# LED-plus20-SHIM.net
KiCad netlist of a schematic drawn in EAGLE
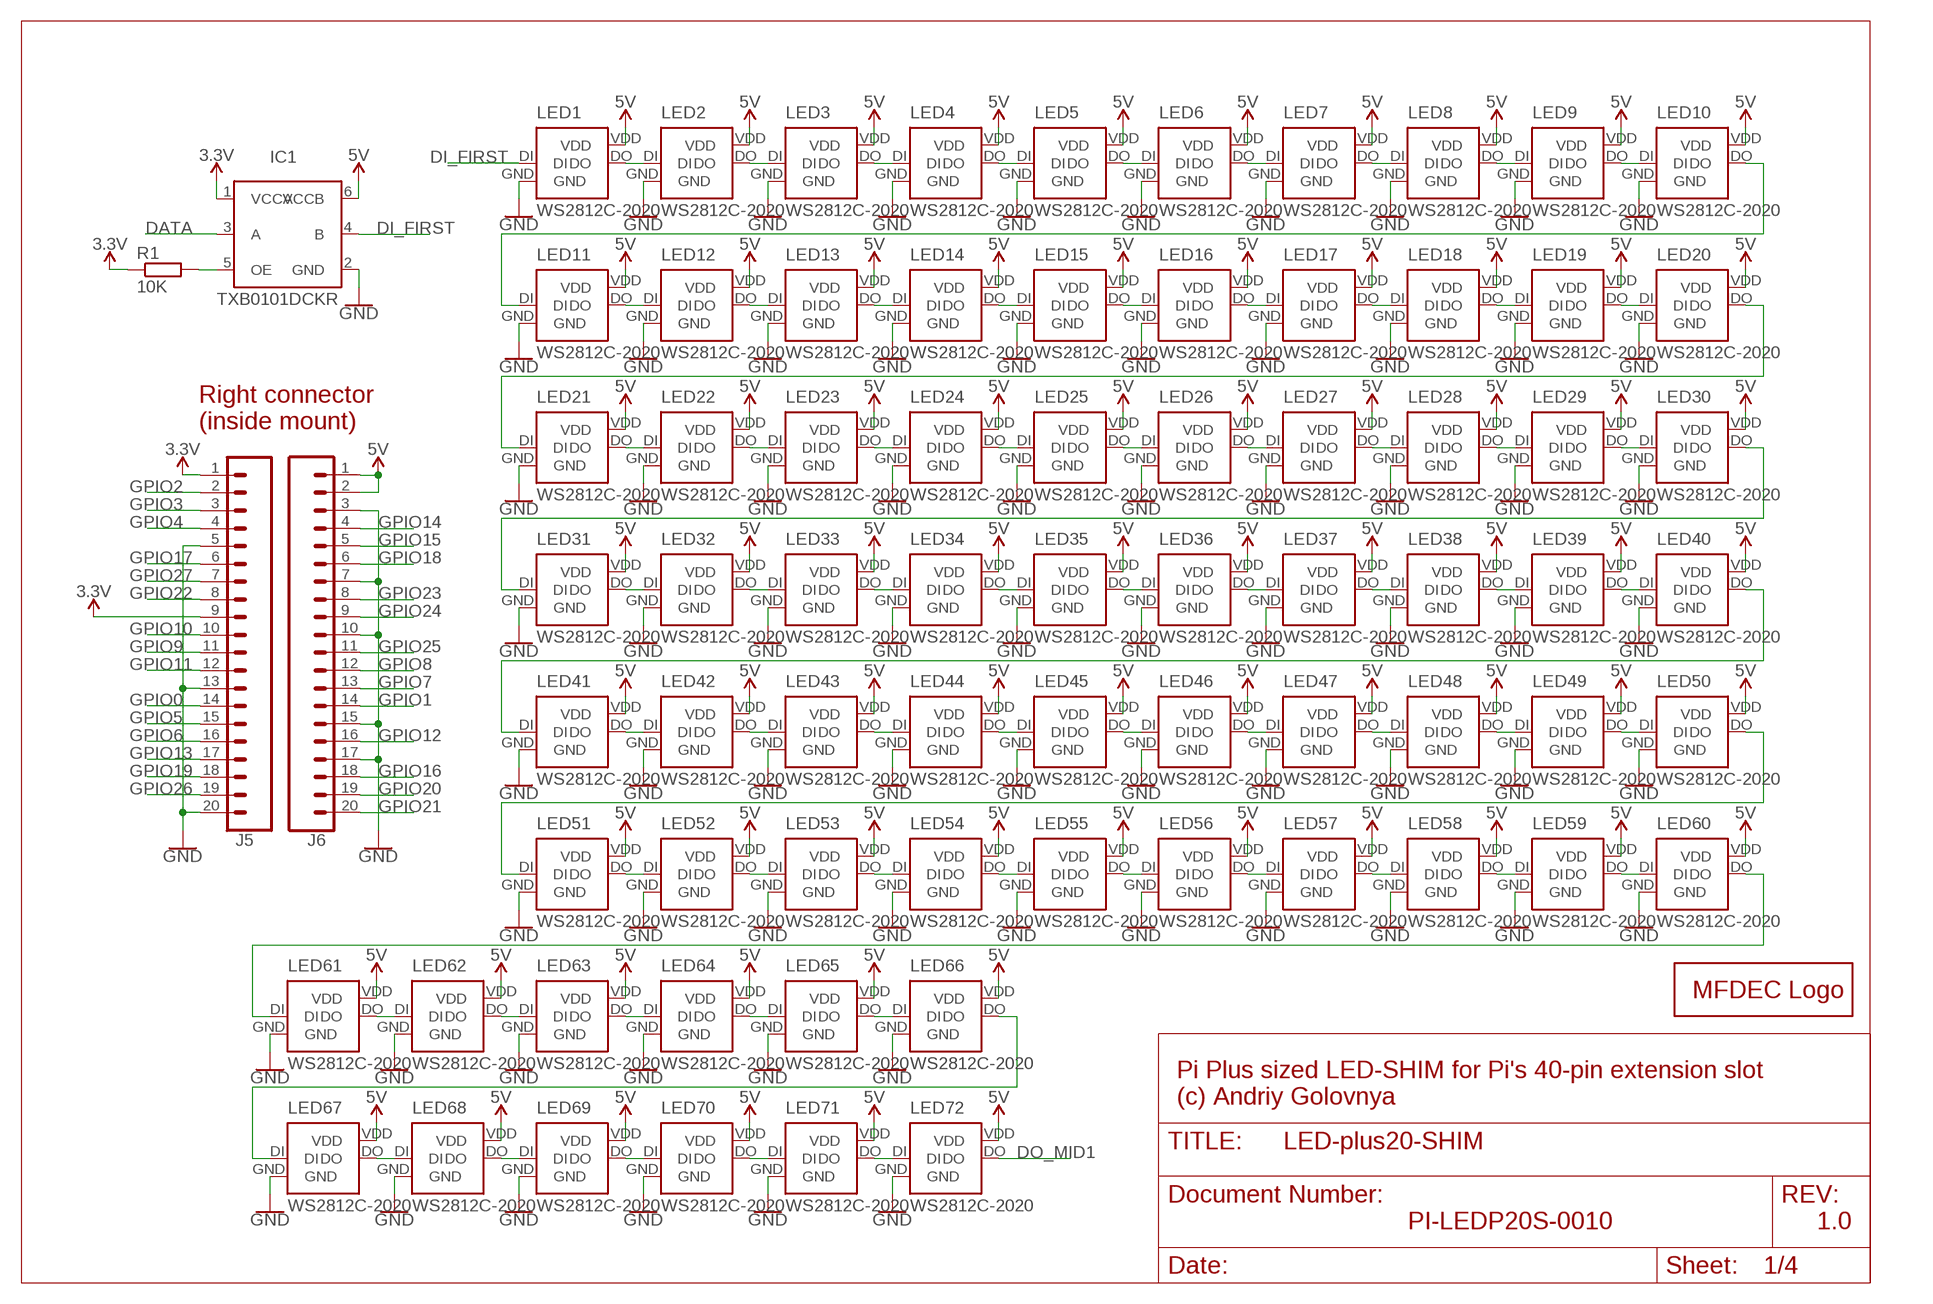
[diagram p0: schematic, sheet 1]
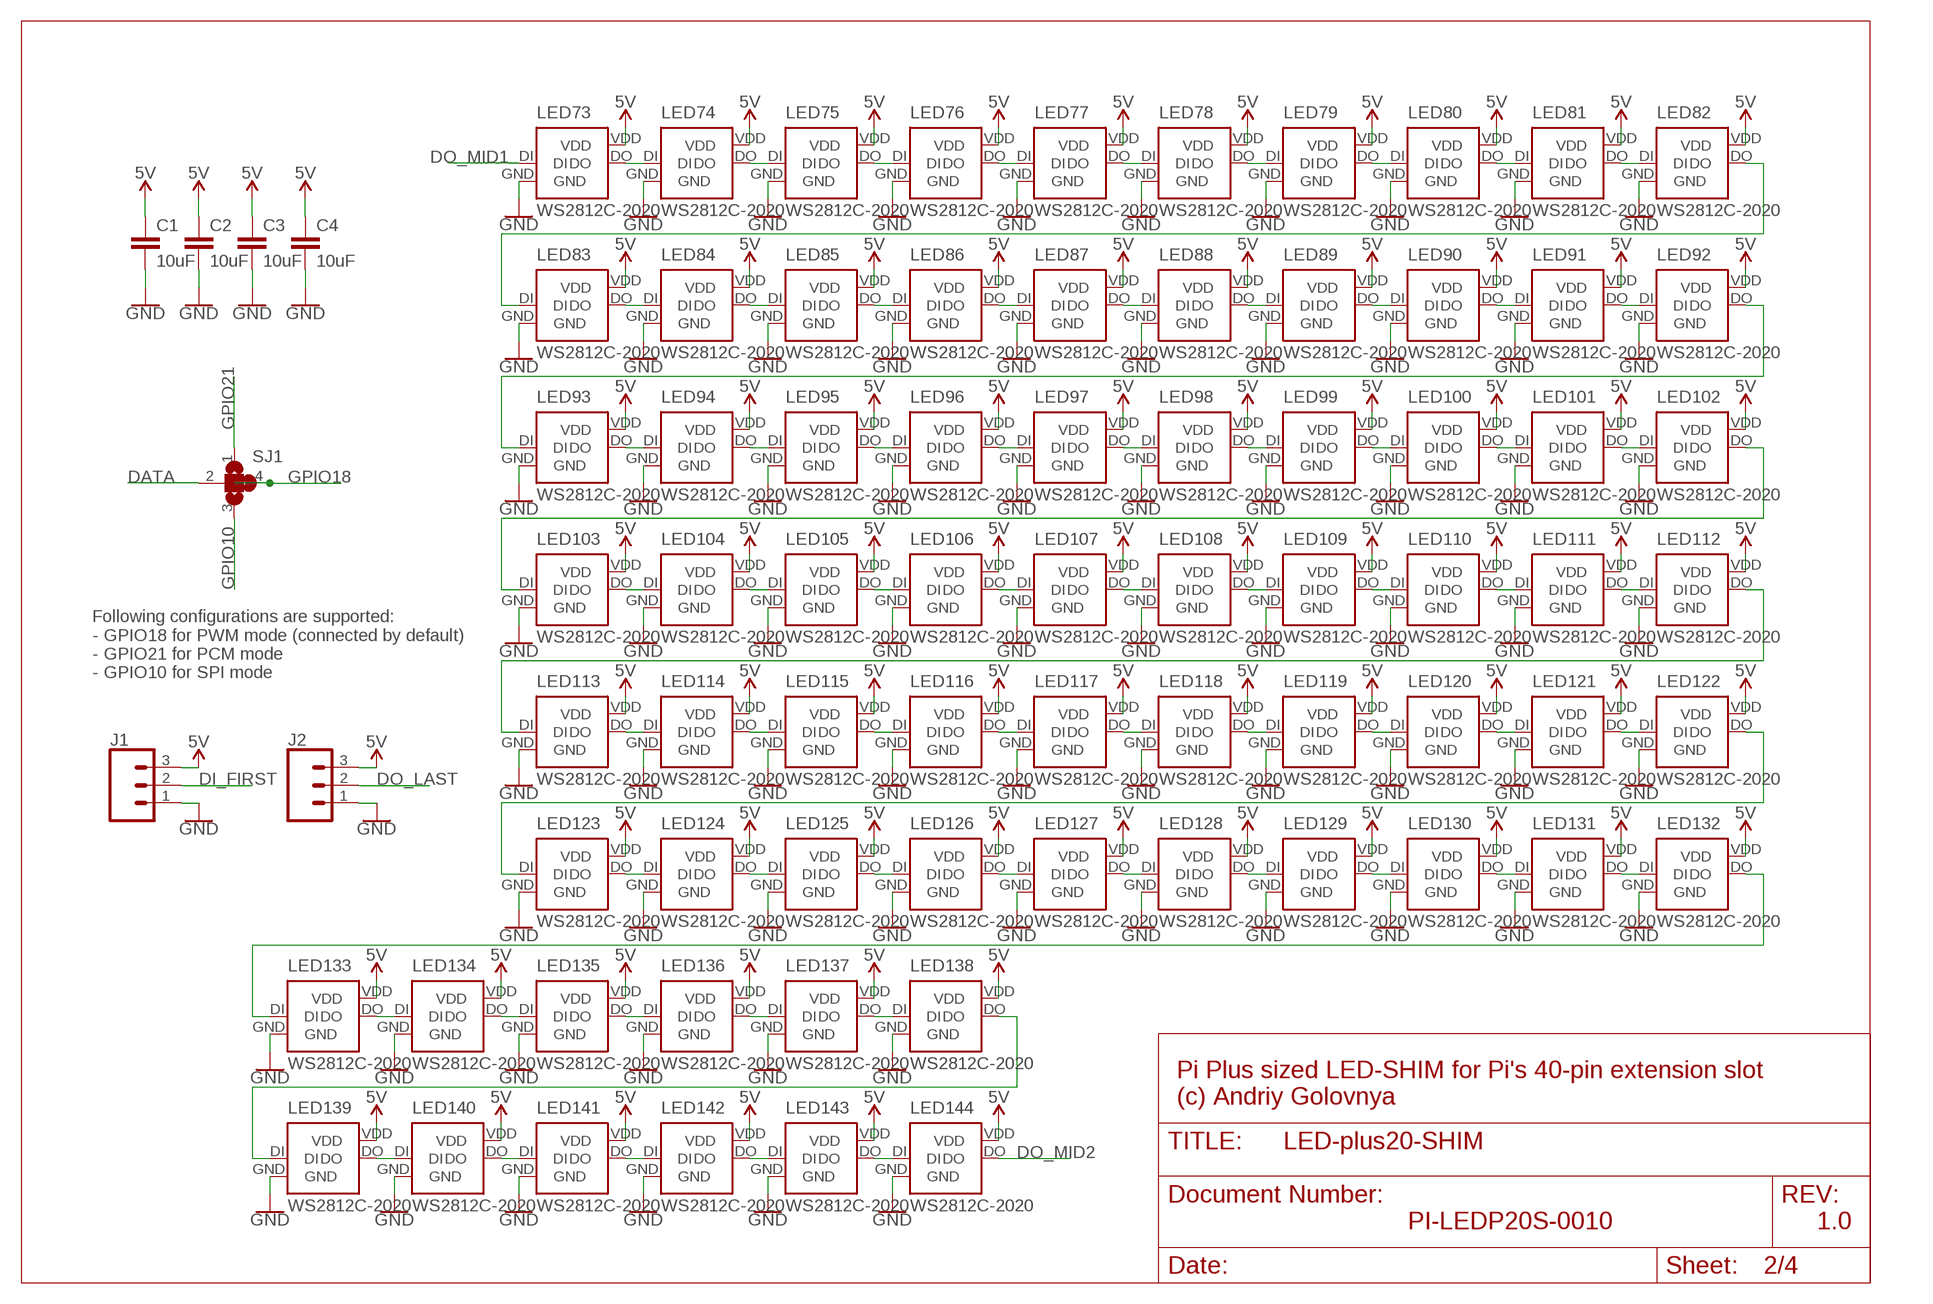
[diagram p1: schematic, sheet 2]
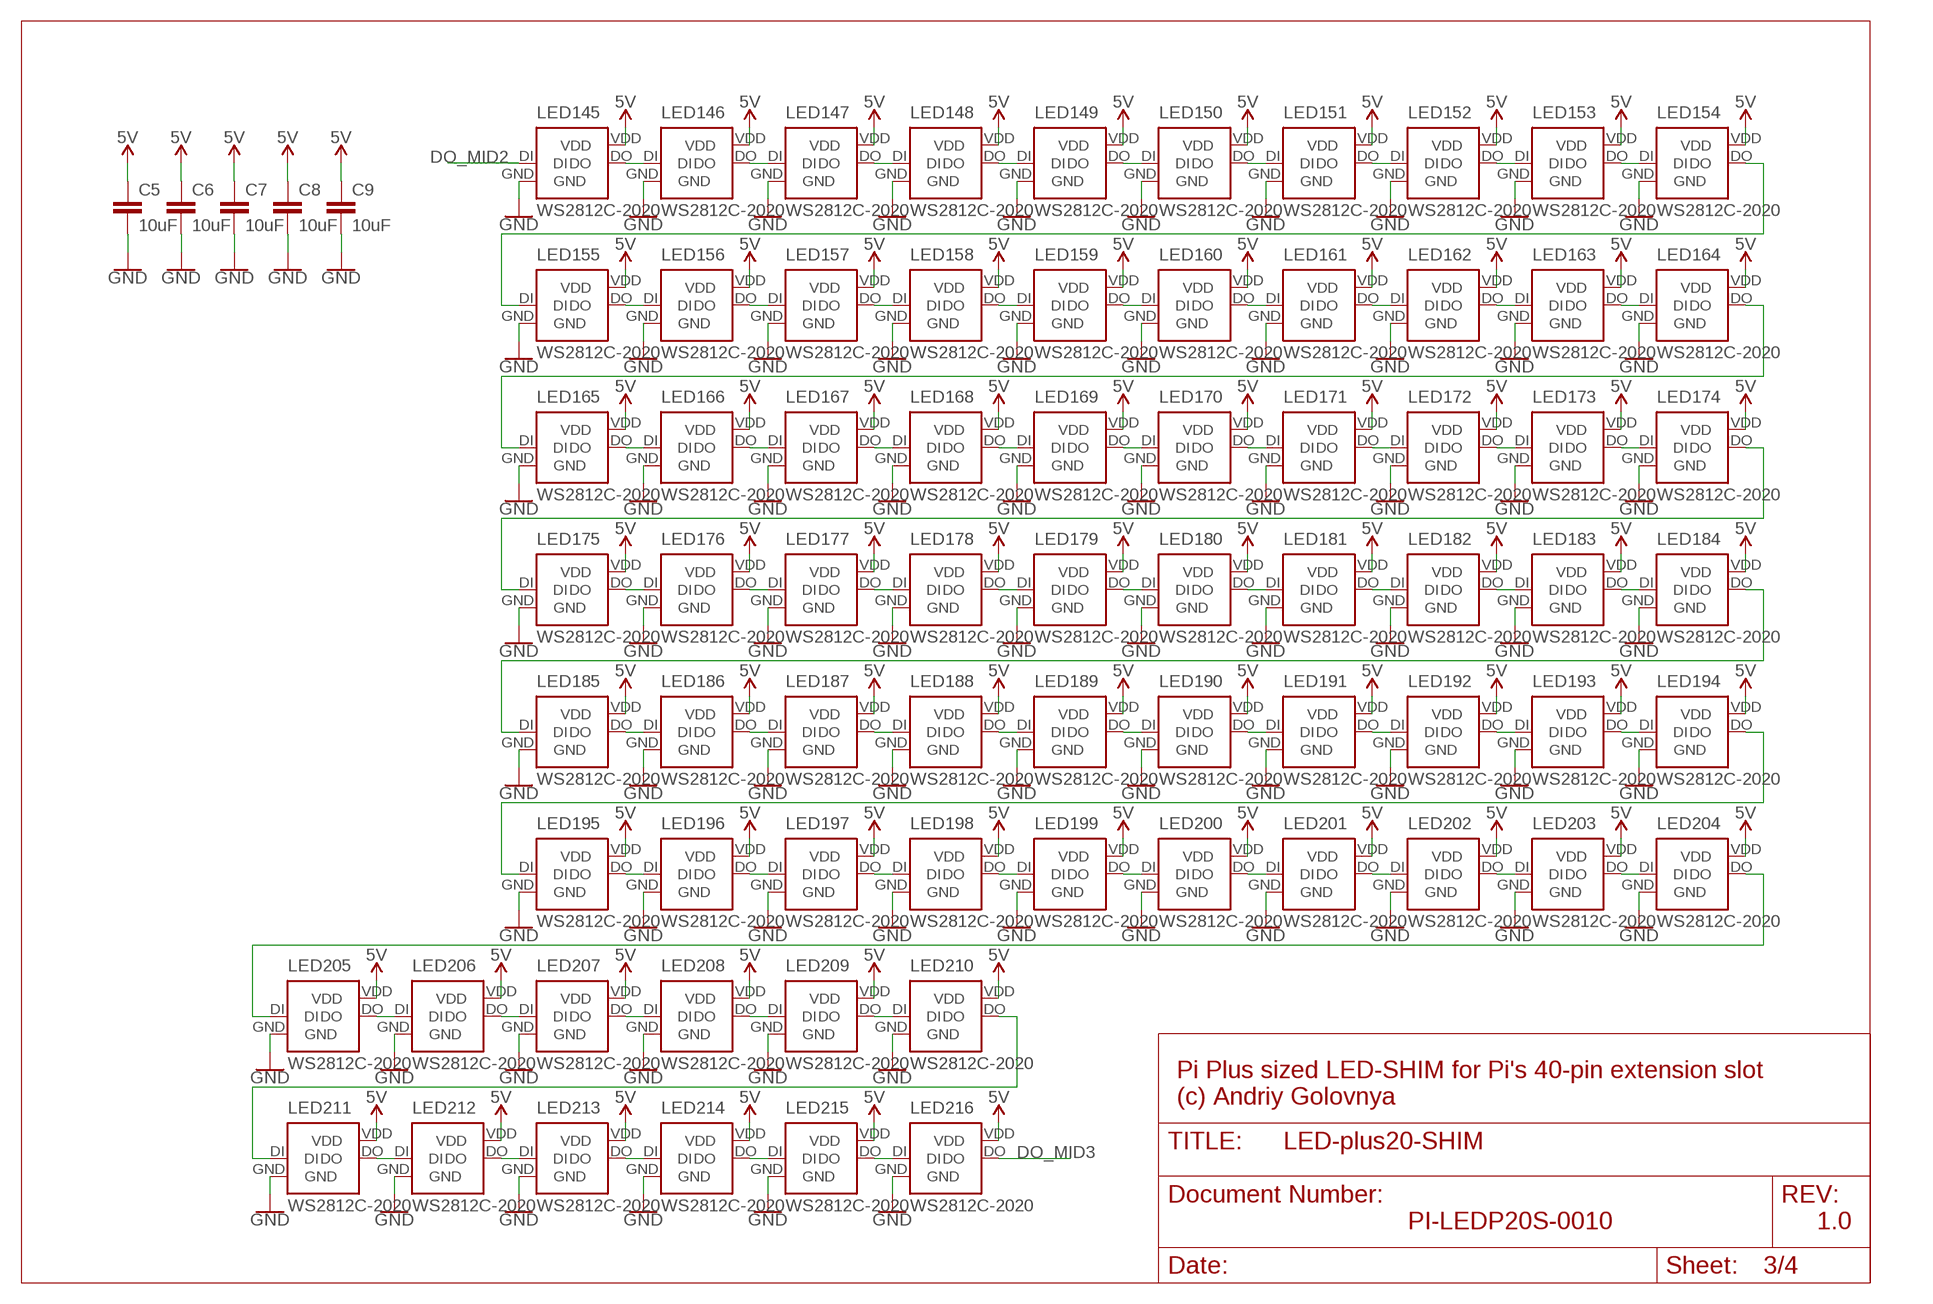
[diagram p2: schematic, sheet 3]
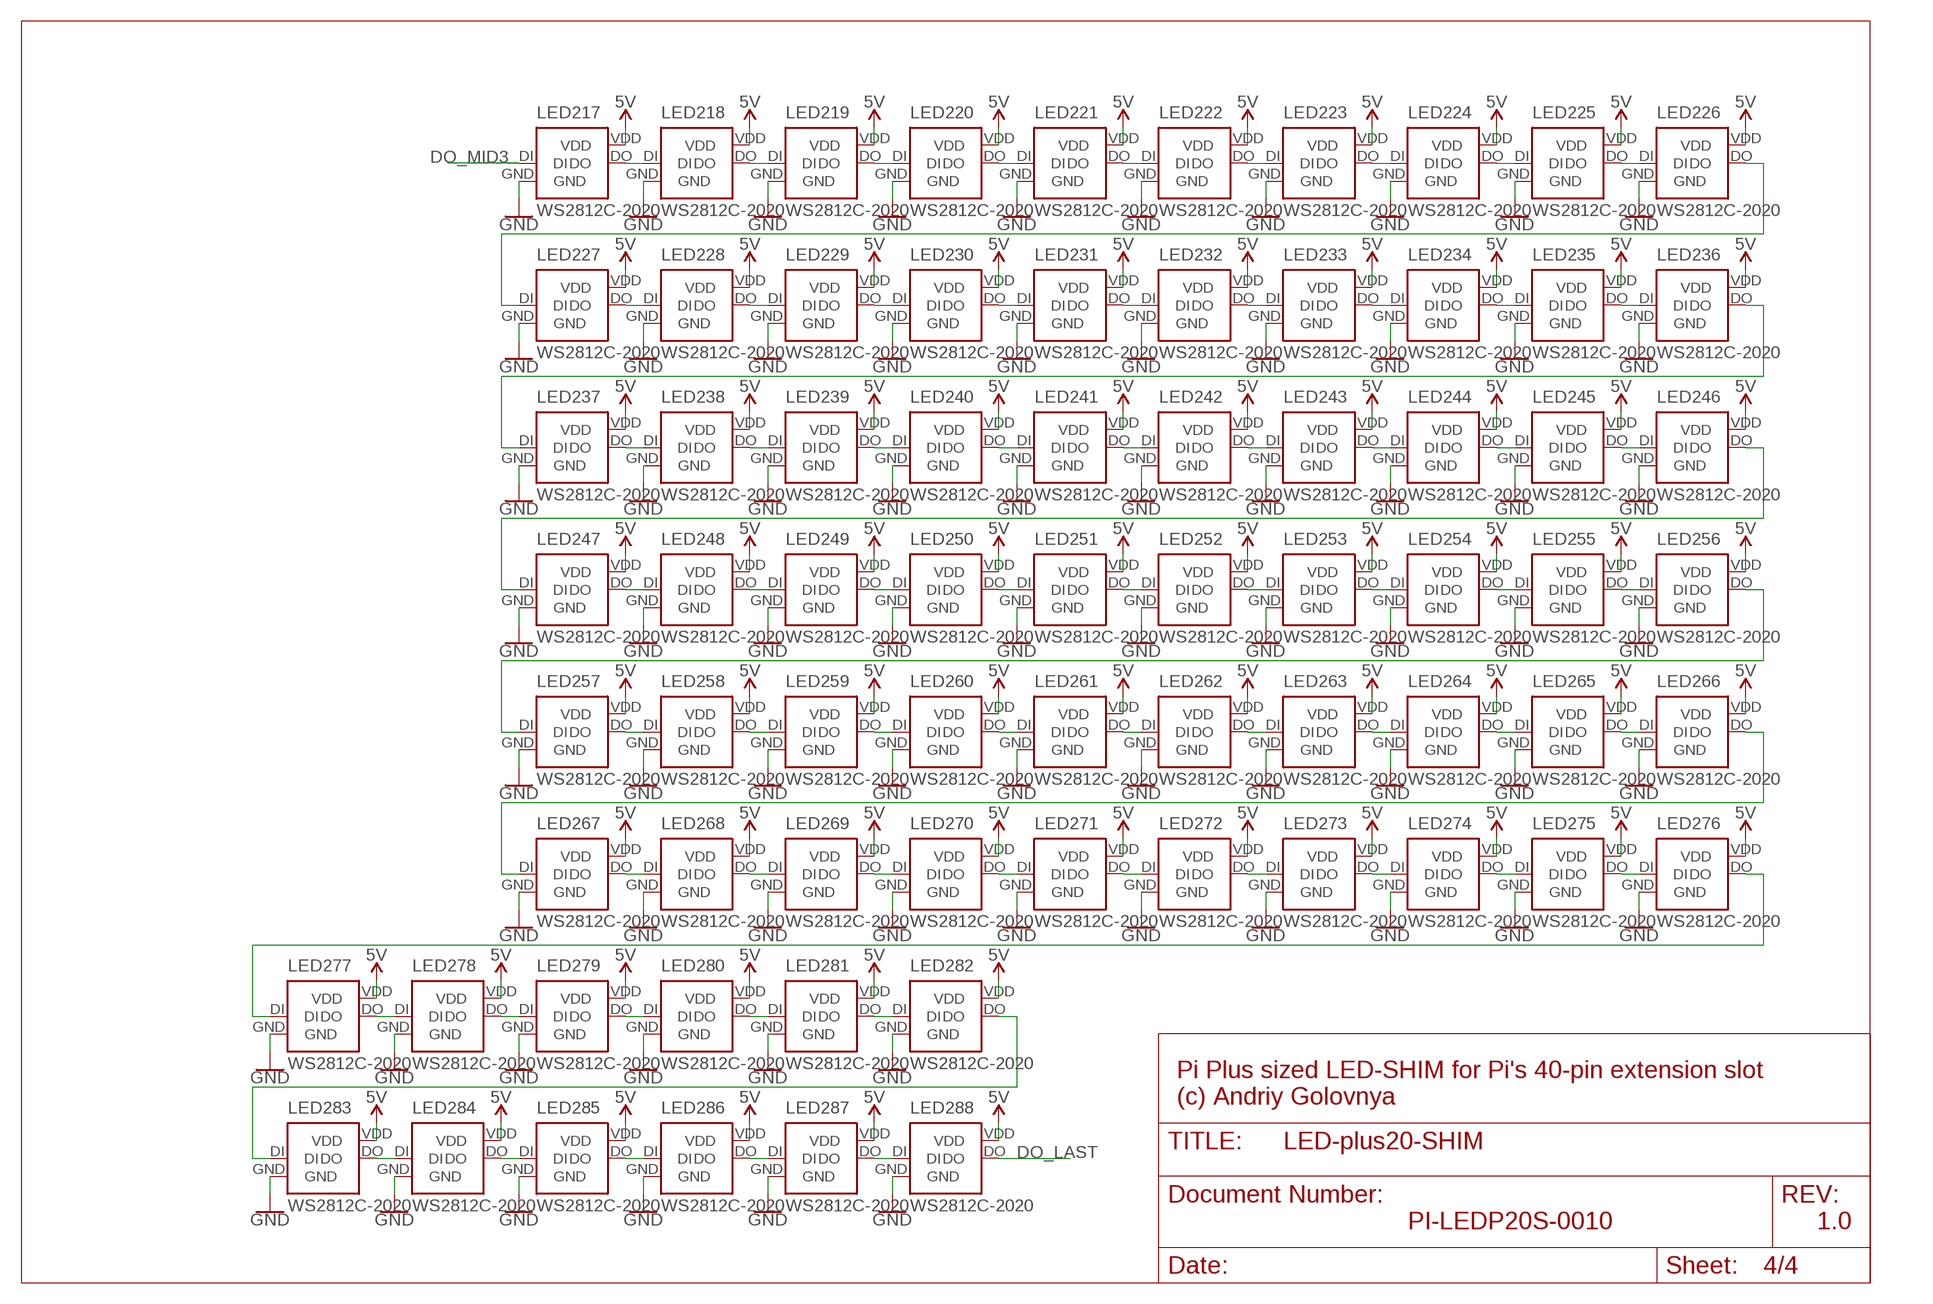
[diagram p3: schematic, sheet 4]

(export (version "E")
  (design (tool "Eeschema 10.0.6"))
  (components
    (comp (ref "C1")
      (value "10uF")
      (footprint "eagle-import:C0805")
      (libsource (lib "eagle-import") (part "C-EUC0805"))
    )
    (comp (ref "C2")
      (value "10uF")
      (footprint "eagle-import:C0805")
      (libsource (lib "eagle-import") (part "C-EUC0805"))
    )
    (comp (ref "C3")
      (value "10uF")
      (footprint "eagle-import:C0805")
      (libsource (lib "eagle-import") (part "C-EUC0805"))
    )
    (comp (ref "C4")
      (value "10uF")
      (footprint "eagle-import:C0805")
      (libsource (lib "eagle-import") (part "C-EUC0805"))
    )
    (comp (ref "J1")
      (value "CONN_03")
      (footprint "eagle-import:1X03")
      (libsource (lib "eagle-import") (part "CONN_03"))
    )
    (comp (ref "J2")
      (value "CONN_03")
      (footprint "eagle-import:1X03")
      (libsource (lib "eagle-import") (part "CONN_03"))
    )
    (comp (ref "LED73")
      (value "WS2812C-2020")
      (footprint "eagle-import:WS2812X-2020")
      (libsource (lib "eagle-import") (part "WS2812C-2020"))
    )
    (comp (ref "LED74")
      (value "WS2812C-2020")
      (footprint "eagle-import:WS2812X-2020")
      (libsource (lib "eagle-import") (part "WS2812C-2020"))
    )
    (comp (ref "LED75")
      (value "WS2812C-2020")
      (footprint "eagle-import:WS2812X-2020")
      (libsource (lib "eagle-import") (part "WS2812C-2020"))
    )
    (comp (ref "LED76")
      (value "WS2812C-2020")
      (footprint "eagle-import:WS2812X-2020")
      (libsource (lib "eagle-import") (part "WS2812C-2020"))
    )
    (comp (ref "LED77")
      (value "WS2812C-2020")
      (footprint "eagle-import:WS2812X-2020")
      (libsource (lib "eagle-import") (part "WS2812C-2020"))
    )
    (comp (ref "LED78")
      (value "WS2812C-2020")
      (footprint "eagle-import:WS2812X-2020")
      (libsource (lib "eagle-import") (part "WS2812C-2020"))
    )
    (comp (ref "LED79")
      (value "WS2812C-2020")
      (footprint "eagle-import:WS2812X-2020")
      (libsource (lib "eagle-import") (part "WS2812C-2020"))
    )
    (comp (ref "LED80")
      (value "WS2812C-2020")
      (footprint "eagle-import:WS2812X-2020")
      (libsource (lib "eagle-import") (part "WS2812C-2020"))
    )
    (comp (ref "LED81")
      (value "WS2812C-2020")
      (footprint "eagle-import:WS2812X-2020")
      (libsource (lib "eagle-import") (part "WS2812C-2020"))
    )
    (comp (ref "LED82")
      (value "WS2812C-2020")
      (footprint "eagle-import:WS2812X-2020")
      (libsource (lib "eagle-import") (part "WS2812C-2020"))
    )
    (comp (ref "LED83")
      (value "WS2812C-2020")
      (footprint "eagle-import:WS2812X-2020")
      (libsource (lib "eagle-import") (part "WS2812C-2020"))
    )
    (comp (ref "LED84")
      (value "WS2812C-2020")
      (footprint "eagle-import:WS2812X-2020")
      (libsource (lib "eagle-import") (part "WS2812C-2020"))
    )
    (comp (ref "LED85")
      (value "WS2812C-2020")
      (footprint "eagle-import:WS2812X-2020")
      (libsource (lib "eagle-import") (part "WS2812C-2020"))
    )
    (comp (ref "LED86")
      (value "WS2812C-2020")
      (footprint "eagle-import:WS2812X-2020")
      (libsource (lib "eagle-import") (part "WS2812C-2020"))
    )
    (comp (ref "LED87")
      (value "WS2812C-2020")
      (footprint "eagle-import:WS2812X-2020")
      (libsource (lib "eagle-import") (part "WS2812C-2020"))
    )
    (comp (ref "LED88")
      (value "WS2812C-2020")
      (footprint "eagle-import:WS2812X-2020")
      (libsource (lib "eagle-import") (part "WS2812C-2020"))
    )
    (comp (ref "LED89")
      (value "WS2812C-2020")
      (footprint "eagle-import:WS2812X-2020")
      (libsource (lib "eagle-import") (part "WS2812C-2020"))
    )
    (comp (ref "LED90")
      (value "WS2812C-2020")
      (footprint "eagle-import:WS2812X-2020")
      (libsource (lib "eagle-import") (part "WS2812C-2020"))
    )
    (comp (ref "LED91")
      (value "WS2812C-2020")
      (footprint "eagle-import:WS2812X-2020")
      (libsource (lib "eagle-import") (part "WS2812C-2020"))
    )
    (comp (ref "LED92")
      (value "WS2812C-2020")
      (footprint "eagle-import:WS2812X-2020")
      (libsource (lib "eagle-import") (part "WS2812C-2020"))
    )
    (comp (ref "LED93")
      (value "WS2812C-2020")
      (footprint "eagle-import:WS2812X-2020")
      (libsource (lib "eagle-import") (part "WS2812C-2020"))
    )
    (comp (ref "LED94")
      (value "WS2812C-2020")
      (footprint "eagle-import:WS2812X-2020")
      (libsource (lib "eagle-import") (part "WS2812C-2020"))
    )
    (comp (ref "LED95")
      (value "WS2812C-2020")
      (footprint "eagle-import:WS2812X-2020")
      (libsource (lib "eagle-import") (part "WS2812C-2020"))
    )
    (comp (ref "LED96")
      (value "WS2812C-2020")
      (footprint "eagle-import:WS2812X-2020")
      (libsource (lib "eagle-import") (part "WS2812C-2020"))
    )
    (comp (ref "LED97")
      (value "WS2812C-2020")
      (footprint "eagle-import:WS2812X-2020")
      (libsource (lib "eagle-import") (part "WS2812C-2020"))
    )
    (comp (ref "LED98")
      (value "WS2812C-2020")
      (footprint "eagle-import:WS2812X-2020")
      (libsource (lib "eagle-import") (part "WS2812C-2020"))
    )
    (comp (ref "LED99")
      (value "WS2812C-2020")
      (footprint "eagle-import:WS2812X-2020")
      (libsource (lib "eagle-import") (part "WS2812C-2020"))
    )
    (comp (ref "LED100")
      (value "WS2812C-2020")
      (footprint "eagle-import:WS2812X-2020")
      (libsource (lib "eagle-import") (part "WS2812C-2020"))
    )
    (comp (ref "LED101")
      (value "WS2812C-2020")
      (footprint "eagle-import:WS2812X-2020")
      (libsource (lib "eagle-import") (part "WS2812C-2020"))
    )
    (comp (ref "LED102")
      (value "WS2812C-2020")
      (footprint "eagle-import:WS2812X-2020")
      (libsource (lib "eagle-import") (part "WS2812C-2020"))
    )
    (comp (ref "LED103")
      (value "WS2812C-2020")
      (footprint "eagle-import:WS2812X-2020")
      (libsource (lib "eagle-import") (part "WS2812C-2020"))
    )
    (comp (ref "LED104")
      (value "WS2812C-2020")
      (footprint "eagle-import:WS2812X-2020")
      (libsource (lib "eagle-import") (part "WS2812C-2020"))
    )
    (comp (ref "LED105")
      (value "WS2812C-2020")
      (footprint "eagle-import:WS2812X-2020")
      (libsource (lib "eagle-import") (part "WS2812C-2020"))
    )
    (comp (ref "LED106")
      (value "WS2812C-2020")
      (footprint "eagle-import:WS2812X-2020")
      (libsource (lib "eagle-import") (part "WS2812C-2020"))
    )
    (comp (ref "LED107")
      (value "WS2812C-2020")
      (footprint "eagle-import:WS2812X-2020")
      (libsource (lib "eagle-import") (part "WS2812C-2020"))
    )
    (comp (ref "LED108")
      (value "WS2812C-2020")
      (footprint "eagle-import:WS2812X-2020")
      (libsource (lib "eagle-import") (part "WS2812C-2020"))
    )
    (comp (ref "LED109")
      (value "WS2812C-2020")
      (footprint "eagle-import:WS2812X-2020")
      (libsource (lib "eagle-import") (part "WS2812C-2020"))
    )
    (comp (ref "LED110")
      (value "WS2812C-2020")
      (footprint "eagle-import:WS2812X-2020")
      (libsource (lib "eagle-import") (part "WS2812C-2020"))
    )
    (comp (ref "LED111")
      (value "WS2812C-2020")
      (footprint "eagle-import:WS2812X-2020")
      (libsource (lib "eagle-import") (part "WS2812C-2020"))
    )
    (comp (ref "LED112")
      (value "WS2812C-2020")
      (footprint "eagle-import:WS2812X-2020")
      (libsource (lib "eagle-import") (part "WS2812C-2020"))
    )
    (comp (ref "LED113")
      (value "WS2812C-2020")
      (footprint "eagle-import:WS2812X-2020")
      (libsource (lib "eagle-import") (part "WS2812C-2020"))
    )
    (comp (ref "LED114")
      (value "WS2812C-2020")
      (footprint "eagle-import:WS2812X-2020")
      (libsource (lib "eagle-import") (part "WS2812C-2020"))
    )
    (comp (ref "LED115")
      (value "WS2812C-2020")
      (footprint "eagle-import:WS2812X-2020")
      (libsource (lib "eagle-import") (part "WS2812C-2020"))
    )
    (comp (ref "LED116")
      (value "WS2812C-2020")
      (footprint "eagle-import:WS2812X-2020")
      (libsource (lib "eagle-import") (part "WS2812C-2020"))
    )
    (comp (ref "LED117")
      (value "WS2812C-2020")
      (footprint "eagle-import:WS2812X-2020")
      (libsource (lib "eagle-import") (part "WS2812C-2020"))
    )
    (comp (ref "LED118")
      (value "WS2812C-2020")
      (footprint "eagle-import:WS2812X-2020")
      (libsource (lib "eagle-import") (part "WS2812C-2020"))
    )
    (comp (ref "LED119")
      (value "WS2812C-2020")
      (footprint "eagle-import:WS2812X-2020")
      (libsource (lib "eagle-import") (part "WS2812C-2020"))
    )
    (comp (ref "LED120")
      (value "WS2812C-2020")
      (footprint "eagle-import:WS2812X-2020")
      (libsource (lib "eagle-import") (part "WS2812C-2020"))
    )
    (comp (ref "LED121")
      (value "WS2812C-2020")
      (footprint "eagle-import:WS2812X-2020")
      (libsource (lib "eagle-import") (part "WS2812C-2020"))
    )
    (comp (ref "LED122")
      (value "WS2812C-2020")
      (footprint "eagle-import:WS2812X-2020")
      (libsource (lib "eagle-import") (part "WS2812C-2020"))
    )
    (comp (ref "LED123")
      (value "WS2812C-2020")
      (footprint "eagle-import:WS2812X-2020")
      (libsource (lib "eagle-import") (part "WS2812C-2020"))
    )
    (comp (ref "LED124")
      (value "WS2812C-2020")
      (footprint "eagle-import:WS2812X-2020")
      (libsource (lib "eagle-import") (part "WS2812C-2020"))
    )
    (comp (ref "LED125")
      (value "WS2812C-2020")
      (footprint "eagle-import:WS2812X-2020")
      (libsource (lib "eagle-import") (part "WS2812C-2020"))
    )
    (comp (ref "LED126")
      (value "WS2812C-2020")
      (footprint "eagle-import:WS2812X-2020")
      (libsource (lib "eagle-import") (part "WS2812C-2020"))
    )
    (comp (ref "LED127")
      (value "WS2812C-2020")
      (footprint "eagle-import:WS2812X-2020")
      (libsource (lib "eagle-import") (part "WS2812C-2020"))
    )
    (comp (ref "LED128")
      (value "WS2812C-2020")
      (footprint "eagle-import:WS2812X-2020")
      (libsource (lib "eagle-import") (part "WS2812C-2020"))
    )
    (comp (ref "LED129")
      (value "WS2812C-2020")
      (footprint "eagle-import:WS2812X-2020")
      (libsource (lib "eagle-import") (part "WS2812C-2020"))
    )
    (comp (ref "LED130")
      (value "WS2812C-2020")
      (footprint "eagle-import:WS2812X-2020")
      (libsource (lib "eagle-import") (part "WS2812C-2020"))
    )
    (comp (ref "LED131")
      (value "WS2812C-2020")
      (footprint "eagle-import:WS2812X-2020")
      (libsource (lib "eagle-import") (part "WS2812C-2020"))
    )
    (comp (ref "LED132")
      (value "WS2812C-2020")
      (footprint "eagle-import:WS2812X-2020")
      (libsource (lib "eagle-import") (part "WS2812C-2020"))
    )
    (comp (ref "LED133")
      (value "WS2812C-2020")
      (footprint "eagle-import:WS2812X-2020")
      (libsource (lib "eagle-import") (part "WS2812C-2020"))
    )
    (comp (ref "LED134")
      (value "WS2812C-2020")
      (footprint "eagle-import:WS2812X-2020")
      (libsource (lib "eagle-import") (part "WS2812C-2020"))
    )
    (comp (ref "LED135")
      (value "WS2812C-2020")
      (footprint "eagle-import:WS2812X-2020")
      (libsource (lib "eagle-import") (part "WS2812C-2020"))
    )
    (comp (ref "LED136")
      (value "WS2812C-2020")
      (footprint "eagle-import:WS2812X-2020")
      (libsource (lib "eagle-import") (part "WS2812C-2020"))
    )
    (comp (ref "LED137")
      (value "WS2812C-2020")
      (footprint "eagle-import:WS2812X-2020")
      (libsource (lib "eagle-import") (part "WS2812C-2020"))
    )
    (comp (ref "LED138")
      (value "WS2812C-2020")
      (footprint "eagle-import:WS2812X-2020")
      (libsource (lib "eagle-import") (part "WS2812C-2020"))
    )
    (comp (ref "LED139")
      (value "WS2812C-2020")
      (footprint "eagle-import:WS2812X-2020")
      (libsource (lib "eagle-import") (part "WS2812C-2020"))
    )
    (comp (ref "LED140")
      (value "WS2812C-2020")
      (footprint "eagle-import:WS2812X-2020")
      (libsource (lib "eagle-import") (part "WS2812C-2020"))
    )
    (comp (ref "LED141")
      (value "WS2812C-2020")
      (footprint "eagle-import:WS2812X-2020")
      (libsource (lib "eagle-import") (part "WS2812C-2020"))
    )
    (comp (ref "LED142")
      (value "WS2812C-2020")
      (footprint "eagle-import:WS2812X-2020")
      (libsource (lib "eagle-import") (part "WS2812C-2020"))
    )
    (comp (ref "LED143")
      (value "WS2812C-2020")
      (footprint "eagle-import:WS2812X-2020")
      (libsource (lib "eagle-import") (part "WS2812C-2020"))
    )
    (comp (ref "LED144")
      (value "WS2812C-2020")
      (footprint "eagle-import:WS2812X-2020")
      (libsource (lib "eagle-import") (part "WS2812C-2020"))
    )
    (comp (ref "SJ1")
      (value "SJ3")
      (footprint "eagle-import:SJ_3")
      (libsource (lib "eagle-import") (part "SJ3"))
    )
    (comp (ref "IC1")
      (value "TXB0101DCKR")
      (footprint "eagle-import:SOT65P210X110-6N")
      (libsource (lib "eagle-import") (part "TXB0101DCKR"))
    )
    (comp (ref "J5")
      (value "CONN_20LOCK")
      (footprint "eagle-import:1X20_LOCK")
      (libsource (lib "eagle-import") (part "CONN_20LOCK"))
    )
    (comp (ref "J6")
      (value "CONN_20LOCK")
      (footprint "eagle-import:1X20_LOCK")
      (libsource (lib "eagle-import") (part "CONN_20LOCK"))
    )
    (comp (ref "LED1")
      (value "WS2812C-2020")
      (footprint "eagle-import:WS2812X-2020")
      (libsource (lib "eagle-import") (part "WS2812C-2020"))
    )
    (comp (ref "LED2")
      (value "WS2812C-2020")
      (footprint "eagle-import:WS2812X-2020")
      (libsource (lib "eagle-import") (part "WS2812C-2020"))
    )
    (comp (ref "LED3")
      (value "WS2812C-2020")
      (footprint "eagle-import:WS2812X-2020")
      (libsource (lib "eagle-import") (part "WS2812C-2020"))
    )
    (comp (ref "LED4")
      (value "WS2812C-2020")
      (footprint "eagle-import:WS2812X-2020")
      (libsource (lib "eagle-import") (part "WS2812C-2020"))
    )
    (comp (ref "LED5")
      (value "WS2812C-2020")
      (footprint "eagle-import:WS2812X-2020")
      (libsource (lib "eagle-import") (part "WS2812C-2020"))
    )
    (comp (ref "LED6")
      (value "WS2812C-2020")
      (footprint "eagle-import:WS2812X-2020")
      (libsource (lib "eagle-import") (part "WS2812C-2020"))
    )
    (comp (ref "LED7")
      (value "WS2812C-2020")
      (footprint "eagle-import:WS2812X-2020")
      (libsource (lib "eagle-import") (part "WS2812C-2020"))
    )
    (comp (ref "LED8")
      (value "WS2812C-2020")
      (footprint "eagle-import:WS2812X-2020")
      (libsource (lib "eagle-import") (part "WS2812C-2020"))
    )
    (comp (ref "LED9")
      (value "WS2812C-2020")
      (footprint "eagle-import:WS2812X-2020")
      (libsource (lib "eagle-import") (part "WS2812C-2020"))
    )
    (comp (ref "LED10")
      (value "WS2812C-2020")
      (footprint "eagle-import:WS2812X-2020")
      (libsource (lib "eagle-import") (part "WS2812C-2020"))
    )
    (comp (ref "LED11")
      (value "WS2812C-2020")
      (footprint "eagle-import:WS2812X-2020")
      (libsource (lib "eagle-import") (part "WS2812C-2020"))
    )
    (comp (ref "LED12")
      (value "WS2812C-2020")
      (footprint "eagle-import:WS2812X-2020")
      (libsource (lib "eagle-import") (part "WS2812C-2020"))
    )
    (comp (ref "LED13")
      (value "WS2812C-2020")
      (footprint "eagle-import:WS2812X-2020")
      (libsource (lib "eagle-import") (part "WS2812C-2020"))
    )
    (comp (ref "LED14")
      (value "WS2812C-2020")
      (footprint "eagle-import:WS2812X-2020")
      (libsource (lib "eagle-import") (part "WS2812C-2020"))
    )
    (comp (ref "LED15")
      (value "WS2812C-2020")
      (footprint "eagle-import:WS2812X-2020")
      (libsource (lib "eagle-import") (part "WS2812C-2020"))
    )
    (comp (ref "LED16")
      (value "WS2812C-2020")
      (footprint "eagle-import:WS2812X-2020")
      (libsource (lib "eagle-import") (part "WS2812C-2020"))
    )
    (comp (ref "LED17")
      (value "WS2812C-2020")
      (footprint "eagle-import:WS2812X-2020")
      (libsource (lib "eagle-import") (part "WS2812C-2020"))
    )
    (comp (ref "LED18")
      (value "WS2812C-2020")
      (footprint "eagle-import:WS2812X-2020")
      (libsource (lib "eagle-import") (part "WS2812C-2020"))
    )
    (comp (ref "LED19")
      (value "WS2812C-2020")
      (footprint "eagle-import:WS2812X-2020")
      (libsource (lib "eagle-import") (part "WS2812C-2020"))
    )
    (comp (ref "LED20")
      (value "WS2812C-2020")
      (footprint "eagle-import:WS2812X-2020")
      (libsource (lib "eagle-import") (part "WS2812C-2020"))
    )
    (comp (ref "LED21")
      (value "WS2812C-2020")
      (footprint "eagle-import:WS2812X-2020")
      (libsource (lib "eagle-import") (part "WS2812C-2020"))
    )
    (comp (ref "LED22")
      (value "WS2812C-2020")
      (footprint "eagle-import:WS2812X-2020")
      (libsource (lib "eagle-import") (part "WS2812C-2020"))
    )
    (comp (ref "LED23")
      (value "WS2812C-2020")
      (footprint "eagle-import:WS2812X-2020")
      (libsource (lib "eagle-import") (part "WS2812C-2020"))
    )
    (comp (ref "LED24")
      (value "WS2812C-2020")
      (footprint "eagle-import:WS2812X-2020")
      (libsource (lib "eagle-import") (part "WS2812C-2020"))
    )
    (comp (ref "LED25")
      (value "WS2812C-2020")
      (footprint "eagle-import:WS2812X-2020")
      (libsource (lib "eagle-import") (part "WS2812C-2020"))
    )
    (comp (ref "LED26")
      (value "WS2812C-2020")
      (footprint "eagle-import:WS2812X-2020")
      (libsource (lib "eagle-import") (part "WS2812C-2020"))
    )
    (comp (ref "LED27")
      (value "WS2812C-2020")
      (footprint "eagle-import:WS2812X-2020")
      (libsource (lib "eagle-import") (part "WS2812C-2020"))
    )
    (comp (ref "LED28")
      (value "WS2812C-2020")
      (footprint "eagle-import:WS2812X-2020")
      (libsource (lib "eagle-import") (part "WS2812C-2020"))
    )
    (comp (ref "LED29")
      (value "WS2812C-2020")
      (footprint "eagle-import:WS2812X-2020")
      (libsource (lib "eagle-import") (part "WS2812C-2020"))
    )
    (comp (ref "LED30")
      (value "WS2812C-2020")
      (footprint "eagle-import:WS2812X-2020")
      (libsource (lib "eagle-import") (part "WS2812C-2020"))
    )
    (comp (ref "LED31")
      (value "WS2812C-2020")
      (footprint "eagle-import:WS2812X-2020")
      (libsource (lib "eagle-import") (part "WS2812C-2020"))
    )
    (comp (ref "LED32")
      (value "WS2812C-2020")
      (footprint "eagle-import:WS2812X-2020")
      (libsource (lib "eagle-import") (part "WS2812C-2020"))
    )
    (comp (ref "LED33")
      (value "WS2812C-2020")
      (footprint "eagle-import:WS2812X-2020")
      (libsource (lib "eagle-import") (part "WS2812C-2020"))
    )
    (comp (ref "LED34")
      (value "WS2812C-2020")
      (footprint "eagle-import:WS2812X-2020")
      (libsource (lib "eagle-import") (part "WS2812C-2020"))
    )
    (comp (ref "LED35")
      (value "WS2812C-2020")
      (footprint "eagle-import:WS2812X-2020")
      (libsource (lib "eagle-import") (part "WS2812C-2020"))
    )
    (comp (ref "LED36")
      (value "WS2812C-2020")
      (footprint "eagle-import:WS2812X-2020")
      (libsource (lib "eagle-import") (part "WS2812C-2020"))
    )
    (comp (ref "LED37")
      (value "WS2812C-2020")
      (footprint "eagle-import:WS2812X-2020")
      (libsource (lib "eagle-import") (part "WS2812C-2020"))
    )
    (comp (ref "LED38")
      (value "WS2812C-2020")
      (footprint "eagle-import:WS2812X-2020")
      (libsource (lib "eagle-import") (part "WS2812C-2020"))
    )
    (comp (ref "LED39")
      (value "WS2812C-2020")
      (footprint "eagle-import:WS2812X-2020")
      (libsource (lib "eagle-import") (part "WS2812C-2020"))
    )
    (comp (ref "LED40")
      (value "WS2812C-2020")
      (footprint "eagle-import:WS2812X-2020")
      (libsource (lib "eagle-import") (part "WS2812C-2020"))
    )
    (comp (ref "LED41")
      (value "WS2812C-2020")
      (footprint "eagle-import:WS2812X-2020")
      (libsource (lib "eagle-import") (part "WS2812C-2020"))
    )
    (comp (ref "LED42")
      (value "WS2812C-2020")
      (footprint "eagle-import:WS2812X-2020")
      (libsource (lib "eagle-import") (part "WS2812C-2020"))
    )
    (comp (ref "LED43")
      (value "WS2812C-2020")
      (footprint "eagle-import:WS2812X-2020")
      (libsource (lib "eagle-import") (part "WS2812C-2020"))
    )
    (comp (ref "LED44")
      (value "WS2812C-2020")
      (footprint "eagle-import:WS2812X-2020")
      (libsource (lib "eagle-import") (part "WS2812C-2020"))
    )
    (comp (ref "LED45")
      (value "WS2812C-2020")
      (footprint "eagle-import:WS2812X-2020")
      (libsource (lib "eagle-import") (part "WS2812C-2020"))
    )
    (comp (ref "LED46")
      (value "WS2812C-2020")
      (footprint "eagle-import:WS2812X-2020")
      (libsource (lib "eagle-import") (part "WS2812C-2020"))
    )
    (comp (ref "LED47")
      (value "WS2812C-2020")
      (footprint "eagle-import:WS2812X-2020")
      (libsource (lib "eagle-import") (part "WS2812C-2020"))
    )
    (comp (ref "LED48")
      (value "WS2812C-2020")
      (footprint "eagle-import:WS2812X-2020")
      (libsource (lib "eagle-import") (part "WS2812C-2020"))
    )
    (comp (ref "LED49")
      (value "WS2812C-2020")
      (footprint "eagle-import:WS2812X-2020")
      (libsource (lib "eagle-import") (part "WS2812C-2020"))
    )
    (comp (ref "LED50")
      (value "WS2812C-2020")
      (footprint "eagle-import:WS2812X-2020")
      (libsource (lib "eagle-import") (part "WS2812C-2020"))
    )
    (comp (ref "LED51")
      (value "WS2812C-2020")
      (footprint "eagle-import:WS2812X-2020")
      (libsource (lib "eagle-import") (part "WS2812C-2020"))
    )
    (comp (ref "LED52")
      (value "WS2812C-2020")
      (footprint "eagle-import:WS2812X-2020")
      (libsource (lib "eagle-import") (part "WS2812C-2020"))
    )
    (comp (ref "LED53")
      (value "WS2812C-2020")
      (footprint "eagle-import:WS2812X-2020")
      (libsource (lib "eagle-import") (part "WS2812C-2020"))
    )
    (comp (ref "LED54")
      (value "WS2812C-2020")
      (footprint "eagle-import:WS2812X-2020")
      (libsource (lib "eagle-import") (part "WS2812C-2020"))
    )
    (comp (ref "LED55")
      (value "WS2812C-2020")
      (footprint "eagle-import:WS2812X-2020")
      (libsource (lib "eagle-import") (part "WS2812C-2020"))
    )
    (comp (ref "LED56")
      (value "WS2812C-2020")
      (footprint "eagle-import:WS2812X-2020")
      (libsource (lib "eagle-import") (part "WS2812C-2020"))
    )
    (comp (ref "LED57")
      (value "WS2812C-2020")
      (footprint "eagle-import:WS2812X-2020")
      (libsource (lib "eagle-import") (part "WS2812C-2020"))
    )
    (comp (ref "LED58")
      (value "WS2812C-2020")
      (footprint "eagle-import:WS2812X-2020")
      (libsource (lib "eagle-import") (part "WS2812C-2020"))
    )
    (comp (ref "LED59")
      (value "WS2812C-2020")
      (footprint "eagle-import:WS2812X-2020")
      (libsource (lib "eagle-import") (part "WS2812C-2020"))
    )
    (comp (ref "LED60")
      (value "WS2812C-2020")
      (footprint "eagle-import:WS2812X-2020")
      (libsource (lib "eagle-import") (part "WS2812C-2020"))
    )
    (comp (ref "LED61")
      (value "WS2812C-2020")
      (footprint "eagle-import:WS2812X-2020")
      (libsource (lib "eagle-import") (part "WS2812C-2020"))
    )
    (comp (ref "LED62")
      (value "WS2812C-2020")
      (footprint "eagle-import:WS2812X-2020")
      (libsource (lib "eagle-import") (part "WS2812C-2020"))
    )
    (comp (ref "LED63")
      (value "WS2812C-2020")
      (footprint "eagle-import:WS2812X-2020")
      (libsource (lib "eagle-import") (part "WS2812C-2020"))
    )
    (comp (ref "LED64")
      (value "WS2812C-2020")
      (footprint "eagle-import:WS2812X-2020")
      (libsource (lib "eagle-import") (part "WS2812C-2020"))
    )
    (comp (ref "LED65")
      (value "WS2812C-2020")
      (footprint "eagle-import:WS2812X-2020")
      (libsource (lib "eagle-import") (part "WS2812C-2020"))
    )
    (comp (ref "LED66")
      (value "WS2812C-2020")
      (footprint "eagle-import:WS2812X-2020")
      (libsource (lib "eagle-import") (part "WS2812C-2020"))
    )
    (comp (ref "LED67")
      (value "WS2812C-2020")
      (footprint "eagle-import:WS2812X-2020")
      (libsource (lib "eagle-import") (part "WS2812C-2020"))
    )
    (comp (ref "LED68")
      (value "WS2812C-2020")
      (footprint "eagle-import:WS2812X-2020")
      (libsource (lib "eagle-import") (part "WS2812C-2020"))
    )
    (comp (ref "LED69")
      (value "WS2812C-2020")
      (footprint "eagle-import:WS2812X-2020")
      (libsource (lib "eagle-import") (part "WS2812C-2020"))
    )
    (comp (ref "LED70")
      (value "WS2812C-2020")
      (footprint "eagle-import:WS2812X-2020")
      (libsource (lib "eagle-import") (part "WS2812C-2020"))
    )
    (comp (ref "LED71")
      (value "WS2812C-2020")
      (footprint "eagle-import:WS2812X-2020")
      (libsource (lib "eagle-import") (part "WS2812C-2020"))
    )
    (comp (ref "LED72")
      (value "WS2812C-2020")
      (footprint "eagle-import:WS2812X-2020")
      (libsource (lib "eagle-import") (part "WS2812C-2020"))
    )
    (comp (ref "LOGO1")
      (value "MFDECLOGO_L_40MM")
      (footprint "eagle-import:MFDEC_L_40MM")
      (libsource (lib "eagle-import") (part "MFDECLOGO_L_40MM"))
    )
    (comp (ref "R1")
      (value "10K")
      (footprint "eagle-import:R0402")
      (libsource (lib "eagle-import") (part "R-EU_R0402"))
    )
    (comp (ref "C5")
      (value "10uF")
      (footprint "eagle-import:C0805")
      (libsource (lib "eagle-import") (part "C-EUC0805"))
    )
    (comp (ref "C6")
      (value "10uF")
      (footprint "eagle-import:C0805")
      (libsource (lib "eagle-import") (part "C-EUC0805"))
    )
    (comp (ref "C7")
      (value "10uF")
      (footprint "eagle-import:C0805")
      (libsource (lib "eagle-import") (part "C-EUC0805"))
    )
    (comp (ref "C8")
      (value "10uF")
      (footprint "eagle-import:C0805")
      (libsource (lib "eagle-import") (part "C-EUC0805"))
    )
    (comp (ref "C9")
      (value "10uF")
      (footprint "eagle-import:C0805")
      (libsource (lib "eagle-import") (part "C-EUC0805"))
    )
    (comp (ref "LED145")
      (value "WS2812C-2020")
      (footprint "eagle-import:WS2812X-2020")
      (libsource (lib "eagle-import") (part "WS2812C-2020"))
    )
    (comp (ref "LED146")
      (value "WS2812C-2020")
      (footprint "eagle-import:WS2812X-2020")
      (libsource (lib "eagle-import") (part "WS2812C-2020"))
    )
    (comp (ref "LED147")
      (value "WS2812C-2020")
      (footprint "eagle-import:WS2812X-2020")
      (libsource (lib "eagle-import") (part "WS2812C-2020"))
    )
    (comp (ref "LED148")
      (value "WS2812C-2020")
      (footprint "eagle-import:WS2812X-2020")
      (libsource (lib "eagle-import") (part "WS2812C-2020"))
    )
    (comp (ref "LED149")
      (value "WS2812C-2020")
      (footprint "eagle-import:WS2812X-2020")
      (libsource (lib "eagle-import") (part "WS2812C-2020"))
    )
    (comp (ref "LED150")
      (value "WS2812C-2020")
      (footprint "eagle-import:WS2812X-2020")
      (libsource (lib "eagle-import") (part "WS2812C-2020"))
    )
    (comp (ref "LED151")
      (value "WS2812C-2020")
      (footprint "eagle-import:WS2812X-2020")
      (libsource (lib "eagle-import") (part "WS2812C-2020"))
    )
    (comp (ref "LED152")
      (value "WS2812C-2020")
      (footprint "eagle-import:WS2812X-2020")
      (libsource (lib "eagle-import") (part "WS2812C-2020"))
    )
    (comp (ref "LED153")
      (value "WS2812C-2020")
      (footprint "eagle-import:WS2812X-2020")
      (libsource (lib "eagle-import") (part "WS2812C-2020"))
    )
    (comp (ref "LED154")
      (value "WS2812C-2020")
      (footprint "eagle-import:WS2812X-2020")
      (libsource (lib "eagle-import") (part "WS2812C-2020"))
    )
    (comp (ref "LED155")
      (value "WS2812C-2020")
      (footprint "eagle-import:WS2812X-2020")
      (libsource (lib "eagle-import") (part "WS2812C-2020"))
    )
    (comp (ref "LED156")
      (value "WS2812C-2020")
      (footprint "eagle-import:WS2812X-2020")
      (libsource (lib "eagle-import") (part "WS2812C-2020"))
    )
    (comp (ref "LED157")
      (value "WS2812C-2020")
      (footprint "eagle-import:WS2812X-2020")
      (libsource (lib "eagle-import") (part "WS2812C-2020"))
    )
    (comp (ref "LED158")
      (value "WS2812C-2020")
      (footprint "eagle-import:WS2812X-2020")
      (libsource (lib "eagle-import") (part "WS2812C-2020"))
    )
    (comp (ref "LED159")
      (value "WS2812C-2020")
      (footprint "eagle-import:WS2812X-2020")
      (libsource (lib "eagle-import") (part "WS2812C-2020"))
    )
    (comp (ref "LED160")
      (value "WS2812C-2020")
      (footprint "eagle-import:WS2812X-2020")
      (libsource (lib "eagle-import") (part "WS2812C-2020"))
    )
    (comp (ref "LED161")
      (value "WS2812C-2020")
      (footprint "eagle-import:WS2812X-2020")
      (libsource (lib "eagle-import") (part "WS2812C-2020"))
    )
    (comp (ref "LED162")
      (value "WS2812C-2020")
      (footprint "eagle-import:WS2812X-2020")
      (libsource (lib "eagle-import") (part "WS2812C-2020"))
    )
    (comp (ref "LED163")
      (value "WS2812C-2020")
      (footprint "eagle-import:WS2812X-2020")
      (libsource (lib "eagle-import") (part "WS2812C-2020"))
    )
    (comp (ref "LED164")
      (value "WS2812C-2020")
      (footprint "eagle-import:WS2812X-2020")
      (libsource (lib "eagle-import") (part "WS2812C-2020"))
    )
    (comp (ref "LED165")
      (value "WS2812C-2020")
      (footprint "eagle-import:WS2812X-2020")
      (libsource (lib "eagle-import") (part "WS2812C-2020"))
    )
    (comp (ref "LED166")
      (value "WS2812C-2020")
      (footprint "eagle-import:WS2812X-2020")
      (libsource (lib "eagle-import") (part "WS2812C-2020"))
    )
    (comp (ref "LED167")
      (value "WS2812C-2020")
      (footprint "eagle-import:WS2812X-2020")
      (libsource (lib "eagle-import") (part "WS2812C-2020"))
    )
    (comp (ref "LED168")
      (value "WS2812C-2020")
      (footprint "eagle-import:WS2812X-2020")
      (libsource (lib "eagle-import") (part "WS2812C-2020"))
    )
    (comp (ref "LED169")
      (value "WS2812C-2020")
      (footprint "eagle-import:WS2812X-2020")
      (libsource (lib "eagle-import") (part "WS2812C-2020"))
    )
    (comp (ref "LED170")
      (value "WS2812C-2020")
      (footprint "eagle-import:WS2812X-2020")
      (libsource (lib "eagle-import") (part "WS2812C-2020"))
    )
    (comp (ref "LED171")
      (value "WS2812C-2020")
      (footprint "eagle-import:WS2812X-2020")
      (libsource (lib "eagle-import") (part "WS2812C-2020"))
    )
    (comp (ref "LED172")
      (value "WS2812C-2020")
      (footprint "eagle-import:WS2812X-2020")
      (libsource (lib "eagle-import") (part "WS2812C-2020"))
    )
    (comp (ref "LED173")
      (value "WS2812C-2020")
      (footprint "eagle-import:WS2812X-2020")
      (libsource (lib "eagle-import") (part "WS2812C-2020"))
    )
    (comp (ref "LED174")
      (value "WS2812C-2020")
      (footprint "eagle-import:WS2812X-2020")
      (libsource (lib "eagle-import") (part "WS2812C-2020"))
    )
    (comp (ref "LED175")
      (value "WS2812C-2020")
      (footprint "eagle-import:WS2812X-2020")
      (libsource (lib "eagle-import") (part "WS2812C-2020"))
    )
    (comp (ref "LED176")
      (value "WS2812C-2020")
      (footprint "eagle-import:WS2812X-2020")
      (libsource (lib "eagle-import") (part "WS2812C-2020"))
    )
    (comp (ref "LED177")
      (value "WS2812C-2020")
      (footprint "eagle-import:WS2812X-2020")
      (libsource (lib "eagle-import") (part "WS2812C-2020"))
    )
    (comp (ref "LED178")
      (value "WS2812C-2020")
      (footprint "eagle-import:WS2812X-2020")
      (libsource (lib "eagle-import") (part "WS2812C-2020"))
    )
    (comp (ref "LED179")
      (value "WS2812C-2020")
      (footprint "eagle-import:WS2812X-2020")
      (libsource (lib "eagle-import") (part "WS2812C-2020"))
    )
    (comp (ref "LED180")
      (value "WS2812C-2020")
      (footprint "eagle-import:WS2812X-2020")
      (libsource (lib "eagle-import") (part "WS2812C-2020"))
    )
    (comp (ref "LED181")
      (value "WS2812C-2020")
      (footprint "eagle-import:WS2812X-2020")
      (libsource (lib "eagle-import") (part "WS2812C-2020"))
    )
    (comp (ref "LED182")
      (value "WS2812C-2020")
      (footprint "eagle-import:WS2812X-2020")
      (libsource (lib "eagle-import") (part "WS2812C-2020"))
    )
    (comp (ref "LED183")
      (value "WS2812C-2020")
      (footprint "eagle-import:WS2812X-2020")
      (libsource (lib "eagle-import") (part "WS2812C-2020"))
    )
    (comp (ref "LED184")
      (value "WS2812C-2020")
      (footprint "eagle-import:WS2812X-2020")
      (libsource (lib "eagle-import") (part "WS2812C-2020"))
    )
    (comp (ref "LED185")
      (value "WS2812C-2020")
      (footprint "eagle-import:WS2812X-2020")
      (libsource (lib "eagle-import") (part "WS2812C-2020"))
    )
    (comp (ref "LED186")
      (value "WS2812C-2020")
      (footprint "eagle-import:WS2812X-2020")
      (libsource (lib "eagle-import") (part "WS2812C-2020"))
    )
    (comp (ref "LED187")
      (value "WS2812C-2020")
      (footprint "eagle-import:WS2812X-2020")
      (libsource (lib "eagle-import") (part "WS2812C-2020"))
    )
    (comp (ref "LED188")
      (value "WS2812C-2020")
      (footprint "eagle-import:WS2812X-2020")
      (libsource (lib "eagle-import") (part "WS2812C-2020"))
    )
    (comp (ref "LED189")
      (value "WS2812C-2020")
      (footprint "eagle-import:WS2812X-2020")
      (libsource (lib "eagle-import") (part "WS2812C-2020"))
    )
    (comp (ref "LED190")
      (value "WS2812C-2020")
      (footprint "eagle-import:WS2812X-2020")
      (libsource (lib "eagle-import") (part "WS2812C-2020"))
    )
    (comp (ref "LED191")
      (value "WS2812C-2020")
      (footprint "eagle-import:WS2812X-2020")
      (libsource (lib "eagle-import") (part "WS2812C-2020"))
    )
    (comp (ref "LED192")
      (value "WS2812C-2020")
      (footprint "eagle-import:WS2812X-2020")
      (libsource (lib "eagle-import") (part "WS2812C-2020"))
    )
    (comp (ref "LED193")
      (value "WS2812C-2020")
      (footprint "eagle-import:WS2812X-2020")
      (libsource (lib "eagle-import") (part "WS2812C-2020"))
    )
    (comp (ref "LED194")
      (value "WS2812C-2020")
      (footprint "eagle-import:WS2812X-2020")
      (libsource (lib "eagle-import") (part "WS2812C-2020"))
    )
    (comp (ref "LED195")
      (value "WS2812C-2020")
      (footprint "eagle-import:WS2812X-2020")
      (libsource (lib "eagle-import") (part "WS2812C-2020"))
    )
    (comp (ref "LED196")
      (value "WS2812C-2020")
      (footprint "eagle-import:WS2812X-2020")
      (libsource (lib "eagle-import") (part "WS2812C-2020"))
    )
    (comp (ref "LED197")
      (value "WS2812C-2020")
      (footprint "eagle-import:WS2812X-2020")
      (libsource (lib "eagle-import") (part "WS2812C-2020"))
    )
    (comp (ref "LED198")
      (value "WS2812C-2020")
      (footprint "eagle-import:WS2812X-2020")
      (libsource (lib "eagle-import") (part "WS2812C-2020"))
    )
    (comp (ref "LED199")
      (value "WS2812C-2020")
      (footprint "eagle-import:WS2812X-2020")
      (libsource (lib "eagle-import") (part "WS2812C-2020"))
    )
    (comp (ref "LED200")
      (value "WS2812C-2020")
      (footprint "eagle-import:WS2812X-2020")
      (libsource (lib "eagle-import") (part "WS2812C-2020"))
    )
    (comp (ref "LED201")
      (value "WS2812C-2020")
      (footprint "eagle-import:WS2812X-2020")
      (libsource (lib "eagle-import") (part "WS2812C-2020"))
    )
    (comp (ref "LED202")
      (value "WS2812C-2020")
      (footprint "eagle-import:WS2812X-2020")
      (libsource (lib "eagle-import") (part "WS2812C-2020"))
    )
    (comp (ref "LED203")
      (value "WS2812C-2020")
      (footprint "eagle-import:WS2812X-2020")
      (libsource (lib "eagle-import") (part "WS2812C-2020"))
    )
    (comp (ref "LED204")
      (value "WS2812C-2020")
      (footprint "eagle-import:WS2812X-2020")
      (libsource (lib "eagle-import") (part "WS2812C-2020"))
    )
    (comp (ref "LED205")
      (value "WS2812C-2020")
      (footprint "eagle-import:WS2812X-2020")
      (libsource (lib "eagle-import") (part "WS2812C-2020"))
    )
    (comp (ref "LED206")
      (value "WS2812C-2020")
      (footprint "eagle-import:WS2812X-2020")
      (libsource (lib "eagle-import") (part "WS2812C-2020"))
    )
    (comp (ref "LED207")
      (value "WS2812C-2020")
      (footprint "eagle-import:WS2812X-2020")
      (libsource (lib "eagle-import") (part "WS2812C-2020"))
    )
    (comp (ref "LED208")
      (value "WS2812C-2020")
      (footprint "eagle-import:WS2812X-2020")
      (libsource (lib "eagle-import") (part "WS2812C-2020"))
    )
    (comp (ref "LED209")
      (value "WS2812C-2020")
      (footprint "eagle-import:WS2812X-2020")
      (libsource (lib "eagle-import") (part "WS2812C-2020"))
    )
    (comp (ref "LED210")
      (value "WS2812C-2020")
      (footprint "eagle-import:WS2812X-2020")
      (libsource (lib "eagle-import") (part "WS2812C-2020"))
    )
    (comp (ref "LED211")
      (value "WS2812C-2020")
      (footprint "eagle-import:WS2812X-2020")
      (libsource (lib "eagle-import") (part "WS2812C-2020"))
    )
    (comp (ref "LED212")
      (value "WS2812C-2020")
      (footprint "eagle-import:WS2812X-2020")
      (libsource (lib "eagle-import") (part "WS2812C-2020"))
    )
    (comp (ref "LED213")
      (value "WS2812C-2020")
      (footprint "eagle-import:WS2812X-2020")
      (libsource (lib "eagle-import") (part "WS2812C-2020"))
    )
    (comp (ref "LED214")
      (value "WS2812C-2020")
      (footprint "eagle-import:WS2812X-2020")
      (libsource (lib "eagle-import") (part "WS2812C-2020"))
    )
    (comp (ref "LED215")
      (value "WS2812C-2020")
      (footprint "eagle-import:WS2812X-2020")
      (libsource (lib "eagle-import") (part "WS2812C-2020"))
    )
    (comp (ref "LED216")
      (value "WS2812C-2020")
      (footprint "eagle-import:WS2812X-2020")
      (libsource (lib "eagle-import") (part "WS2812C-2020"))
    )
    (comp (ref "LED217")
      (value "WS2812C-2020")
      (footprint "eagle-import:WS2812X-2020")
      (libsource (lib "eagle-import") (part "WS2812C-2020"))
    )
    (comp (ref "LED218")
      (value "WS2812C-2020")
      (footprint "eagle-import:WS2812X-2020")
      (libsource (lib "eagle-import") (part "WS2812C-2020"))
    )
    (comp (ref "LED219")
      (value "WS2812C-2020")
      (footprint "eagle-import:WS2812X-2020")
      (libsource (lib "eagle-import") (part "WS2812C-2020"))
    )
    (comp (ref "LED220")
      (value "WS2812C-2020")
      (footprint "eagle-import:WS2812X-2020")
      (libsource (lib "eagle-import") (part "WS2812C-2020"))
    )
    (comp (ref "LED221")
      (value "WS2812C-2020")
      (footprint "eagle-import:WS2812X-2020")
      (libsource (lib "eagle-import") (part "WS2812C-2020"))
    )
    (comp (ref "LED222")
      (value "WS2812C-2020")
      (footprint "eagle-import:WS2812X-2020")
      (libsource (lib "eagle-import") (part "WS2812C-2020"))
    )
    (comp (ref "LED223")
      (value "WS2812C-2020")
      (footprint "eagle-import:WS2812X-2020")
      (libsource (lib "eagle-import") (part "WS2812C-2020"))
    )
    (comp (ref "LED224")
      (value "WS2812C-2020")
      (footprint "eagle-import:WS2812X-2020")
      (libsource (lib "eagle-import") (part "WS2812C-2020"))
    )
    (comp (ref "LED225")
      (value "WS2812C-2020")
      (footprint "eagle-import:WS2812X-2020")
      (libsource (lib "eagle-import") (part "WS2812C-2020"))
    )
    (comp (ref "LED226")
      (value "WS2812C-2020")
      (footprint "eagle-import:WS2812X-2020")
      (libsource (lib "eagle-import") (part "WS2812C-2020"))
    )
    (comp (ref "LED227")
      (value "WS2812C-2020")
      (footprint "eagle-import:WS2812X-2020")
      (libsource (lib "eagle-import") (part "WS2812C-2020"))
    )
    (comp (ref "LED228")
      (value "WS2812C-2020")
      (footprint "eagle-import:WS2812X-2020")
      (libsource (lib "eagle-import") (part "WS2812C-2020"))
    )
    (comp (ref "LED229")
      (value "WS2812C-2020")
      (footprint "eagle-import:WS2812X-2020")
      (libsource (lib "eagle-import") (part "WS2812C-2020"))
    )
    (comp (ref "LED230")
      (value "WS2812C-2020")
      (footprint "eagle-import:WS2812X-2020")
      (libsource (lib "eagle-import") (part "WS2812C-2020"))
    )
    (comp (ref "LED231")
      (value "WS2812C-2020")
      (footprint "eagle-import:WS2812X-2020")
      (libsource (lib "eagle-import") (part "WS2812C-2020"))
    )
    (comp (ref "LED232")
      (value "WS2812C-2020")
      (footprint "eagle-import:WS2812X-2020")
      (libsource (lib "eagle-import") (part "WS2812C-2020"))
    )
    (comp (ref "LED233")
      (value "WS2812C-2020")
      (footprint "eagle-import:WS2812X-2020")
      (libsource (lib "eagle-import") (part "WS2812C-2020"))
    )
    (comp (ref "LED234")
      (value "WS2812C-2020")
      (footprint "eagle-import:WS2812X-2020")
      (libsource (lib "eagle-import") (part "WS2812C-2020"))
    )
    (comp (ref "LED235")
      (value "WS2812C-2020")
      (footprint "eagle-import:WS2812X-2020")
      (libsource (lib "eagle-import") (part "WS2812C-2020"))
    )
    (comp (ref "LED236")
      (value "WS2812C-2020")
      (footprint "eagle-import:WS2812X-2020")
      (libsource (lib "eagle-import") (part "WS2812C-2020"))
    )
    (comp (ref "LED237")
      (value "WS2812C-2020")
      (footprint "eagle-import:WS2812X-2020")
      (libsource (lib "eagle-import") (part "WS2812C-2020"))
    )
    (comp (ref "LED238")
      (value "WS2812C-2020")
      (footprint "eagle-import:WS2812X-2020")
      (libsource (lib "eagle-import") (part "WS2812C-2020"))
    )
    (comp (ref "LED239")
      (value "WS2812C-2020")
      (footprint "eagle-import:WS2812X-2020")
      (libsource (lib "eagle-import") (part "WS2812C-2020"))
    )
    (comp (ref "LED240")
      (value "WS2812C-2020")
      (footprint "eagle-import:WS2812X-2020")
      (libsource (lib "eagle-import") (part "WS2812C-2020"))
    )
    (comp (ref "LED241")
      (value "WS2812C-2020")
      (footprint "eagle-import:WS2812X-2020")
      (libsource (lib "eagle-import") (part "WS2812C-2020"))
    )
    (comp (ref "LED242")
      (value "WS2812C-2020")
      (footprint "eagle-import:WS2812X-2020")
      (libsource (lib "eagle-import") (part "WS2812C-2020"))
    )
    (comp (ref "LED243")
      (value "WS2812C-2020")
      (footprint "eagle-import:WS2812X-2020")
      (libsource (lib "eagle-import") (part "WS2812C-2020"))
    )
    (comp (ref "LED244")
      (value "WS2812C-2020")
      (footprint "eagle-import:WS2812X-2020")
      (libsource (lib "eagle-import") (part "WS2812C-2020"))
    )
    (comp (ref "LED245")
      (value "WS2812C-2020")
      (footprint "eagle-import:WS2812X-2020")
      (libsource (lib "eagle-import") (part "WS2812C-2020"))
    )
    (comp (ref "LED246")
      (value "WS2812C-2020")
      (footprint "eagle-import:WS2812X-2020")
      (libsource (lib "eagle-import") (part "WS2812C-2020"))
    )
    (comp (ref "LED247")
      (value "WS2812C-2020")
      (footprint "eagle-import:WS2812X-2020")
      (libsource (lib "eagle-import") (part "WS2812C-2020"))
    )
    (comp (ref "LED248")
      (value "WS2812C-2020")
      (footprint "eagle-import:WS2812X-2020")
      (libsource (lib "eagle-import") (part "WS2812C-2020"))
    )
    (comp (ref "LED249")
      (value "WS2812C-2020")
      (footprint "eagle-import:WS2812X-2020")
      (libsource (lib "eagle-import") (part "WS2812C-2020"))
    )
    (comp (ref "LED250")
      (value "WS2812C-2020")
      (footprint "eagle-import:WS2812X-2020")
      (libsource (lib "eagle-import") (part "WS2812C-2020"))
    )
    (comp (ref "LED251")
      (value "WS2812C-2020")
      (footprint "eagle-import:WS2812X-2020")
      (libsource (lib "eagle-import") (part "WS2812C-2020"))
    )
    (comp (ref "LED252")
      (value "WS2812C-2020")
      (footprint "eagle-import:WS2812X-2020")
      (libsource (lib "eagle-import") (part "WS2812C-2020"))
    )
    (comp (ref "LED253")
      (value "WS2812C-2020")
      (footprint "eagle-import:WS2812X-2020")
      (libsource (lib "eagle-import") (part "WS2812C-2020"))
    )
    (comp (ref "LED254")
      (value "WS2812C-2020")
      (footprint "eagle-import:WS2812X-2020")
      (libsource (lib "eagle-import") (part "WS2812C-2020"))
    )
    (comp (ref "LED255")
      (value "WS2812C-2020")
      (footprint "eagle-import:WS2812X-2020")
      (libsource (lib "eagle-import") (part "WS2812C-2020"))
    )
    (comp (ref "LED256")
      (value "WS2812C-2020")
      (footprint "eagle-import:WS2812X-2020")
      (libsource (lib "eagle-import") (part "WS2812C-2020"))
    )
    (comp (ref "LED257")
      (value "WS2812C-2020")
      (footprint "eagle-import:WS2812X-2020")
      (libsource (lib "eagle-import") (part "WS2812C-2020"))
    )
    (comp (ref "LED258")
      (value "WS2812C-2020")
      (footprint "eagle-import:WS2812X-2020")
      (libsource (lib "eagle-import") (part "WS2812C-2020"))
    )
    (comp (ref "LED259")
      (value "WS2812C-2020")
      (footprint "eagle-import:WS2812X-2020")
      (libsource (lib "eagle-import") (part "WS2812C-2020"))
    )
    (comp (ref "LED260")
      (value "WS2812C-2020")
      (footprint "eagle-import:WS2812X-2020")
      (libsource (lib "eagle-import") (part "WS2812C-2020"))
    )
    (comp (ref "LED261")
      (value "WS2812C-2020")
      (footprint "eagle-import:WS2812X-2020")
      (libsource (lib "eagle-import") (part "WS2812C-2020"))
    )
    (comp (ref "LED262")
      (value "WS2812C-2020")
      (footprint "eagle-import:WS2812X-2020")
      (libsource (lib "eagle-import") (part "WS2812C-2020"))
    )
    (comp (ref "LED263")
      (value "WS2812C-2020")
      (footprint "eagle-import:WS2812X-2020")
      (libsource (lib "eagle-import") (part "WS2812C-2020"))
    )
    (comp (ref "LED264")
      (value "WS2812C-2020")
      (footprint "eagle-import:WS2812X-2020")
      (libsource (lib "eagle-import") (part "WS2812C-2020"))
    )
    (comp (ref "LED265")
      (value "WS2812C-2020")
      (footprint "eagle-import:WS2812X-2020")
      (libsource (lib "eagle-import") (part "WS2812C-2020"))
    )
    (comp (ref "LED266")
      (value "WS2812C-2020")
      (footprint "eagle-import:WS2812X-2020")
      (libsource (lib "eagle-import") (part "WS2812C-2020"))
    )
    (comp (ref "LED267")
      (value "WS2812C-2020")
      (footprint "eagle-import:WS2812X-2020")
      (libsource (lib "eagle-import") (part "WS2812C-2020"))
    )
    (comp (ref "LED268")
      (value "WS2812C-2020")
      (footprint "eagle-import:WS2812X-2020")
      (libsource (lib "eagle-import") (part "WS2812C-2020"))
    )
    (comp (ref "LED269")
      (value "WS2812C-2020")
      (footprint "eagle-import:WS2812X-2020")
      (libsource (lib "eagle-import") (part "WS2812C-2020"))
    )
    (comp (ref "LED270")
      (value "WS2812C-2020")
      (footprint "eagle-import:WS2812X-2020")
      (libsource (lib "eagle-import") (part "WS2812C-2020"))
    )
    (comp (ref "LED271")
      (value "WS2812C-2020")
      (footprint "eagle-import:WS2812X-2020")
      (libsource (lib "eagle-import") (part "WS2812C-2020"))
    )
    (comp (ref "LED272")
      (value "WS2812C-2020")
      (footprint "eagle-import:WS2812X-2020")
      (libsource (lib "eagle-import") (part "WS2812C-2020"))
    )
    (comp (ref "LED273")
      (value "WS2812C-2020")
      (footprint "eagle-import:WS2812X-2020")
      (libsource (lib "eagle-import") (part "WS2812C-2020"))
    )
    (comp (ref "LED274")
      (value "WS2812C-2020")
      (footprint "eagle-import:WS2812X-2020")
      (libsource (lib "eagle-import") (part "WS2812C-2020"))
    )
    (comp (ref "LED275")
      (value "WS2812C-2020")
      (footprint "eagle-import:WS2812X-2020")
      (libsource (lib "eagle-import") (part "WS2812C-2020"))
    )
    (comp (ref "LED276")
      (value "WS2812C-2020")
      (footprint "eagle-import:WS2812X-2020")
      (libsource (lib "eagle-import") (part "WS2812C-2020"))
    )
    (comp (ref "LED277")
      (value "WS2812C-2020")
      (footprint "eagle-import:WS2812X-2020")
      (libsource (lib "eagle-import") (part "WS2812C-2020"))
    )
    (comp (ref "LED278")
      (value "WS2812C-2020")
      (footprint "eagle-import:WS2812X-2020")
      (libsource (lib "eagle-import") (part "WS2812C-2020"))
    )
    (comp (ref "LED279")
      (value "WS2812C-2020")
      (footprint "eagle-import:WS2812X-2020")
      (libsource (lib "eagle-import") (part "WS2812C-2020"))
    )
    (comp (ref "LED280")
      (value "WS2812C-2020")
      (footprint "eagle-import:WS2812X-2020")
      (libsource (lib "eagle-import") (part "WS2812C-2020"))
    )
    (comp (ref "LED281")
      (value "WS2812C-2020")
      (footprint "eagle-import:WS2812X-2020")
      (libsource (lib "eagle-import") (part "WS2812C-2020"))
    )
    (comp (ref "LED282")
      (value "WS2812C-2020")
      (footprint "eagle-import:WS2812X-2020")
      (libsource (lib "eagle-import") (part "WS2812C-2020"))
    )
    (comp (ref "LED283")
      (value "WS2812C-2020")
      (footprint "eagle-import:WS2812X-2020")
      (libsource (lib "eagle-import") (part "WS2812C-2020"))
    )
    (comp (ref "LED284")
      (value "WS2812C-2020")
      (footprint "eagle-import:WS2812X-2020")
      (libsource (lib "eagle-import") (part "WS2812C-2020"))
    )
    (comp (ref "LED285")
      (value "WS2812C-2020")
      (footprint "eagle-import:WS2812X-2020")
      (libsource (lib "eagle-import") (part "WS2812C-2020"))
    )
    (comp (ref "LED286")
      (value "WS2812C-2020")
      (footprint "eagle-import:WS2812X-2020")
      (libsource (lib "eagle-import") (part "WS2812C-2020"))
    )
    (comp (ref "LED287")
      (value "WS2812C-2020")
      (footprint "eagle-import:WS2812X-2020")
      (libsource (lib "eagle-import") (part "WS2812C-2020"))
    )
    (comp (ref "LED288")
      (value "WS2812C-2020")
      (footprint "eagle-import:WS2812X-2020")
      (libsource (lib "eagle-import") (part "WS2812C-2020"))
    )
  )
  (nets
    (net (code "1") (name "3.3V") (class "Default")
      (node (ref "IC1") (pin "1") (pinfunction "VCCA_1") (pintype "power_in"))
      (node (ref "J5") (pin "1") (pinfunction "1_1") (pintype "passive"))
      (node (ref "J5") (pin "9") (pinfunction "9_9") (pintype "passive"))
      (node (ref "R1") (pin "1") (pinfunction "1_1") (pintype "passive"))
    )
    (net (code "2") (name "5V") (class "Default")
      (node (ref "C1") (pin "1") (pinfunction "1_1") (pintype "passive"))
      (node (ref "C2") (pin "1") (pinfunction "1_1") (pintype "passive"))
      (node (ref "C3") (pin "1") (pinfunction "1_1") (pintype "passive"))
      (node (ref "C4") (pin "1") (pinfunction "1_1") (pintype "passive"))
      (node (ref "C5") (pin "1") (pinfunction "1_1") (pintype "passive"))
      (node (ref "C6") (pin "1") (pinfunction "1_1") (pintype "passive"))
      (node (ref "C7") (pin "1") (pinfunction "1_1") (pintype "passive"))
      (node (ref "C8") (pin "1") (pinfunction "1_1") (pintype "passive"))
      (node (ref "C9") (pin "1") (pinfunction "1_1") (pintype "passive"))
      (node (ref "IC1") (pin "6") (pinfunction "VCCB_6") (pintype "power_in"))
      (node (ref "J1") (pin "3") (pinfunction "3_3") (pintype "passive"))
      (node (ref "J2") (pin "3") (pinfunction "3_3") (pintype "passive"))
      (node (ref "J6") (pin "1") (pinfunction "1_1") (pintype "passive"))
      (node (ref "J6") (pin "2") (pinfunction "2_2") (pintype "passive"))
      (node (ref "LED1") (pin "VDD") (pinfunction "VDD_VDD") (pintype "power_in"))
      (node (ref "LED10") (pin "VDD") (pinfunction "VDD_VDD") (pintype "power_in"))
      (node (ref "LED100") (pin "VDD") (pinfunction "VDD_VDD") (pintype "power_in"))
      (node (ref "LED101") (pin "VDD") (pinfunction "VDD_VDD") (pintype "power_in"))
      (node (ref "LED102") (pin "VDD") (pinfunction "VDD_VDD") (pintype "power_in"))
      (node (ref "LED103") (pin "VDD") (pinfunction "VDD_VDD") (pintype "power_in"))
      (node (ref "LED104") (pin "VDD") (pinfunction "VDD_VDD") (pintype "power_in"))
      (node (ref "LED105") (pin "VDD") (pinfunction "VDD_VDD") (pintype "power_in"))
      (node (ref "LED106") (pin "VDD") (pinfunction "VDD_VDD") (pintype "power_in"))
      (node (ref "LED107") (pin "VDD") (pinfunction "VDD_VDD") (pintype "power_in"))
      (node (ref "LED108") (pin "VDD") (pinfunction "VDD_VDD") (pintype "power_in"))
      (node (ref "LED109") (pin "VDD") (pinfunction "VDD_VDD") (pintype "power_in"))
      (node (ref "LED11") (pin "VDD") (pinfunction "VDD_VDD") (pintype "power_in"))
      (node (ref "LED110") (pin "VDD") (pinfunction "VDD_VDD") (pintype "power_in"))
      (node (ref "LED111") (pin "VDD") (pinfunction "VDD_VDD") (pintype "power_in"))
      (node (ref "LED112") (pin "VDD") (pinfunction "VDD_VDD") (pintype "power_in"))
      (node (ref "LED113") (pin "VDD") (pinfunction "VDD_VDD") (pintype "power_in"))
      (node (ref "LED114") (pin "VDD") (pinfunction "VDD_VDD") (pintype "power_in"))
      (node (ref "LED115") (pin "VDD") (pinfunction "VDD_VDD") (pintype "power_in"))
      (node (ref "LED116") (pin "VDD") (pinfunction "VDD_VDD") (pintype "power_in"))
      (node (ref "LED117") (pin "VDD") (pinfunction "VDD_VDD") (pintype "power_in"))
      (node (ref "LED118") (pin "VDD") (pinfunction "VDD_VDD") (pintype "power_in"))
      (node (ref "LED119") (pin "VDD") (pinfunction "VDD_VDD") (pintype "power_in"))
      (node (ref "LED12") (pin "VDD") (pinfunction "VDD_VDD") (pintype "power_in"))
      (node (ref "LED120") (pin "VDD") (pinfunction "VDD_VDD") (pintype "power_in"))
      (node (ref "LED121") (pin "VDD") (pinfunction "VDD_VDD") (pintype "power_in"))
      (node (ref "LED122") (pin "VDD") (pinfunction "VDD_VDD") (pintype "power_in"))
      (node (ref "LED123") (pin "VDD") (pinfunction "VDD_VDD") (pintype "power_in"))
      (node (ref "LED124") (pin "VDD") (pinfunction "VDD_VDD") (pintype "power_in"))
      (node (ref "LED125") (pin "VDD") (pinfunction "VDD_VDD") (pintype "power_in"))
      (node (ref "LED126") (pin "VDD") (pinfunction "VDD_VDD") (pintype "power_in"))
      (node (ref "LED127") (pin "VDD") (pinfunction "VDD_VDD") (pintype "power_in"))
      (node (ref "LED128") (pin "VDD") (pinfunction "VDD_VDD") (pintype "power_in"))
      (node (ref "LED129") (pin "VDD") (pinfunction "VDD_VDD") (pintype "power_in"))
      (node (ref "LED13") (pin "VDD") (pinfunction "VDD_VDD") (pintype "power_in"))
      (node (ref "LED130") (pin "VDD") (pinfunction "VDD_VDD") (pintype "power_in"))
      (node (ref "LED131") (pin "VDD") (pinfunction "VDD_VDD") (pintype "power_in"))
      (node (ref "LED132") (pin "VDD") (pinfunction "VDD_VDD") (pintype "power_in"))
      (node (ref "LED133") (pin "VDD") (pinfunction "VDD_VDD") (pintype "power_in"))
      (node (ref "LED134") (pin "VDD") (pinfunction "VDD_VDD") (pintype "power_in"))
      (node (ref "LED135") (pin "VDD") (pinfunction "VDD_VDD") (pintype "power_in"))
      (node (ref "LED136") (pin "VDD") (pinfunction "VDD_VDD") (pintype "power_in"))
      (node (ref "LED137") (pin "VDD") (pinfunction "VDD_VDD") (pintype "power_in"))
      (node (ref "LED138") (pin "VDD") (pinfunction "VDD_VDD") (pintype "power_in"))
      (node (ref "LED139") (pin "VDD") (pinfunction "VDD_VDD") (pintype "power_in"))
      (node (ref "LED14") (pin "VDD") (pinfunction "VDD_VDD") (pintype "power_in"))
      (node (ref "LED140") (pin "VDD") (pinfunction "VDD_VDD") (pintype "power_in"))
      (node (ref "LED141") (pin "VDD") (pinfunction "VDD_VDD") (pintype "power_in"))
      (node (ref "LED142") (pin "VDD") (pinfunction "VDD_VDD") (pintype "power_in"))
      (node (ref "LED143") (pin "VDD") (pinfunction "VDD_VDD") (pintype "power_in"))
      (node (ref "LED144") (pin "VDD") (pinfunction "VDD_VDD") (pintype "power_in"))
      (node (ref "LED145") (pin "VDD") (pinfunction "VDD_VDD") (pintype "power_in"))
      (node (ref "LED146") (pin "VDD") (pinfunction "VDD_VDD") (pintype "power_in"))
      (node (ref "LED147") (pin "VDD") (pinfunction "VDD_VDD") (pintype "power_in"))
      (node (ref "LED148") (pin "VDD") (pinfunction "VDD_VDD") (pintype "power_in"))
      (node (ref "LED149") (pin "VDD") (pinfunction "VDD_VDD") (pintype "power_in"))
      (node (ref "LED15") (pin "VDD") (pinfunction "VDD_VDD") (pintype "power_in"))
      (node (ref "LED150") (pin "VDD") (pinfunction "VDD_VDD") (pintype "power_in"))
      (node (ref "LED151") (pin "VDD") (pinfunction "VDD_VDD") (pintype "power_in"))
      (node (ref "LED152") (pin "VDD") (pinfunction "VDD_VDD") (pintype "power_in"))
      (node (ref "LED153") (pin "VDD") (pinfunction "VDD_VDD") (pintype "power_in"))
      (node (ref "LED154") (pin "VDD") (pinfunction "VDD_VDD") (pintype "power_in"))
      (node (ref "LED155") (pin "VDD") (pinfunction "VDD_VDD") (pintype "power_in"))
      (node (ref "LED156") (pin "VDD") (pinfunction "VDD_VDD") (pintype "power_in"))
      (node (ref "LED157") (pin "VDD") (pinfunction "VDD_VDD") (pintype "power_in"))
      (node (ref "LED158") (pin "VDD") (pinfunction "VDD_VDD") (pintype "power_in"))
      (node (ref "LED159") (pin "VDD") (pinfunction "VDD_VDD") (pintype "power_in"))
      (node (ref "LED16") (pin "VDD") (pinfunction "VDD_VDD") (pintype "power_in"))
      (node (ref "LED160") (pin "VDD") (pinfunction "VDD_VDD") (pintype "power_in"))
      (node (ref "LED161") (pin "VDD") (pinfunction "VDD_VDD") (pintype "power_in"))
      (node (ref "LED162") (pin "VDD") (pinfunction "VDD_VDD") (pintype "power_in"))
      (node (ref "LED163") (pin "VDD") (pinfunction "VDD_VDD") (pintype "power_in"))
      (node (ref "LED164") (pin "VDD") (pinfunction "VDD_VDD") (pintype "power_in"))
      (node (ref "LED165") (pin "VDD") (pinfunction "VDD_VDD") (pintype "power_in"))
      (node (ref "LED166") (pin "VDD") (pinfunction "VDD_VDD") (pintype "power_in"))
      (node (ref "LED167") (pin "VDD") (pinfunction "VDD_VDD") (pintype "power_in"))
      (node (ref "LED168") (pin "VDD") (pinfunction "VDD_VDD") (pintype "power_in"))
      (node (ref "LED169") (pin "VDD") (pinfunction "VDD_VDD") (pintype "power_in"))
      (node (ref "LED17") (pin "VDD") (pinfunction "VDD_VDD") (pintype "power_in"))
      (node (ref "LED170") (pin "VDD") (pinfunction "VDD_VDD") (pintype "power_in"))
      (node (ref "LED171") (pin "VDD") (pinfunction "VDD_VDD") (pintype "power_in"))
      (node (ref "LED172") (pin "VDD") (pinfunction "VDD_VDD") (pintype "power_in"))
      (node (ref "LED173") (pin "VDD") (pinfunction "VDD_VDD") (pintype "power_in"))
      (node (ref "LED174") (pin "VDD") (pinfunction "VDD_VDD") (pintype "power_in"))
      (node (ref "LED175") (pin "VDD") (pinfunction "VDD_VDD") (pintype "power_in"))
      (node (ref "LED176") (pin "VDD") (pinfunction "VDD_VDD") (pintype "power_in"))
      (node (ref "LED177") (pin "VDD") (pinfunction "VDD_VDD") (pintype "power_in"))
      (node (ref "LED178") (pin "VDD") (pinfunction "VDD_VDD") (pintype "power_in"))
      (node (ref "LED179") (pin "VDD") (pinfunction "VDD_VDD") (pintype "power_in"))
      (node (ref "LED18") (pin "VDD") (pinfunction "VDD_VDD") (pintype "power_in"))
      (node (ref "LED180") (pin "VDD") (pinfunction "VDD_VDD") (pintype "power_in"))
      (node (ref "LED181") (pin "VDD") (pinfunction "VDD_VDD") (pintype "power_in"))
      (node (ref "LED182") (pin "VDD") (pinfunction "VDD_VDD") (pintype "power_in"))
      (node (ref "LED183") (pin "VDD") (pinfunction "VDD_VDD") (pintype "power_in"))
      (node (ref "LED184") (pin "VDD") (pinfunction "VDD_VDD") (pintype "power_in"))
      (node (ref "LED185") (pin "VDD") (pinfunction "VDD_VDD") (pintype "power_in"))
      (node (ref "LED186") (pin "VDD") (pinfunction "VDD_VDD") (pintype "power_in"))
      (node (ref "LED187") (pin "VDD") (pinfunction "VDD_VDD") (pintype "power_in"))
      (node (ref "LED188") (pin "VDD") (pinfunction "VDD_VDD") (pintype "power_in"))
      (node (ref "LED189") (pin "VDD") (pinfunction "VDD_VDD") (pintype "power_in"))
      (node (ref "LED19") (pin "VDD") (pinfunction "VDD_VDD") (pintype "power_in"))
      (node (ref "LED190") (pin "VDD") (pinfunction "VDD_VDD") (pintype "power_in"))
      (node (ref "LED191") (pin "VDD") (pinfunction "VDD_VDD") (pintype "power_in"))
      (node (ref "LED192") (pin "VDD") (pinfunction "VDD_VDD") (pintype "power_in"))
      (node (ref "LED193") (pin "VDD") (pinfunction "VDD_VDD") (pintype "power_in"))
      (node (ref "LED194") (pin "VDD") (pinfunction "VDD_VDD") (pintype "power_in"))
      (node (ref "LED195") (pin "VDD") (pinfunction "VDD_VDD") (pintype "power_in"))
      (node (ref "LED196") (pin "VDD") (pinfunction "VDD_VDD") (pintype "power_in"))
      (node (ref "LED197") (pin "VDD") (pinfunction "VDD_VDD") (pintype "power_in"))
      (node (ref "LED198") (pin "VDD") (pinfunction "VDD_VDD") (pintype "power_in"))
      (node (ref "LED199") (pin "VDD") (pinfunction "VDD_VDD") (pintype "power_in"))
      (node (ref "LED2") (pin "VDD") (pinfunction "VDD_VDD") (pintype "power_in"))
      (node (ref "LED20") (pin "VDD") (pinfunction "VDD_VDD") (pintype "power_in"))
      (node (ref "LED200") (pin "VDD") (pinfunction "VDD_VDD") (pintype "power_in"))
      (node (ref "LED201") (pin "VDD") (pinfunction "VDD_VDD") (pintype "power_in"))
      (node (ref "LED202") (pin "VDD") (pinfunction "VDD_VDD") (pintype "power_in"))
      (node (ref "LED203") (pin "VDD") (pinfunction "VDD_VDD") (pintype "power_in"))
      (node (ref "LED204") (pin "VDD") (pinfunction "VDD_VDD") (pintype "power_in"))
      (node (ref "LED205") (pin "VDD") (pinfunction "VDD_VDD") (pintype "power_in"))
      (node (ref "LED206") (pin "VDD") (pinfunction "VDD_VDD") (pintype "power_in"))
      (node (ref "LED207") (pin "VDD") (pinfunction "VDD_VDD") (pintype "power_in"))
      (node (ref "LED208") (pin "VDD") (pinfunction "VDD_VDD") (pintype "power_in"))
      (node (ref "LED209") (pin "VDD") (pinfunction "VDD_VDD") (pintype "power_in"))
      (node (ref "LED21") (pin "VDD") (pinfunction "VDD_VDD") (pintype "power_in"))
      (node (ref "LED210") (pin "VDD") (pinfunction "VDD_VDD") (pintype "power_in"))
      (node (ref "LED211") (pin "VDD") (pinfunction "VDD_VDD") (pintype "power_in"))
      (node (ref "LED212") (pin "VDD") (pinfunction "VDD_VDD") (pintype "power_in"))
      (node (ref "LED213") (pin "VDD") (pinfunction "VDD_VDD") (pintype "power_in"))
      (node (ref "LED214") (pin "VDD") (pinfunction "VDD_VDD") (pintype "power_in"))
      (node (ref "LED215") (pin "VDD") (pinfunction "VDD_VDD") (pintype "power_in"))
      (node (ref "LED216") (pin "VDD") (pinfunction "VDD_VDD") (pintype "power_in"))
      (node (ref "LED217") (pin "VDD") (pinfunction "VDD_VDD") (pintype "power_in"))
      (node (ref "LED218") (pin "VDD") (pinfunction "VDD_VDD") (pintype "power_in"))
      (node (ref "LED219") (pin "VDD") (pinfunction "VDD_VDD") (pintype "power_in"))
      (node (ref "LED22") (pin "VDD") (pinfunction "VDD_VDD") (pintype "power_in"))
      (node (ref "LED220") (pin "VDD") (pinfunction "VDD_VDD") (pintype "power_in"))
      (node (ref "LED221") (pin "VDD") (pinfunction "VDD_VDD") (pintype "power_in"))
      (node (ref "LED222") (pin "VDD") (pinfunction "VDD_VDD") (pintype "power_in"))
      (node (ref "LED223") (pin "VDD") (pinfunction "VDD_VDD") (pintype "power_in"))
      (node (ref "LED224") (pin "VDD") (pinfunction "VDD_VDD") (pintype "power_in"))
      (node (ref "LED225") (pin "VDD") (pinfunction "VDD_VDD") (pintype "power_in"))
      (node (ref "LED226") (pin "VDD") (pinfunction "VDD_VDD") (pintype "power_in"))
      (node (ref "LED227") (pin "VDD") (pinfunction "VDD_VDD") (pintype "power_in"))
      (node (ref "LED228") (pin "VDD") (pinfunction "VDD_VDD") (pintype "power_in"))
      (node (ref "LED229") (pin "VDD") (pinfunction "VDD_VDD") (pintype "power_in"))
      (node (ref "LED23") (pin "VDD") (pinfunction "VDD_VDD") (pintype "power_in"))
      (node (ref "LED230") (pin "VDD") (pinfunction "VDD_VDD") (pintype "power_in"))
      (node (ref "LED231") (pin "VDD") (pinfunction "VDD_VDD") (pintype "power_in"))
      (node (ref "LED232") (pin "VDD") (pinfunction "VDD_VDD") (pintype "power_in"))
      (node (ref "LED233") (pin "VDD") (pinfunction "VDD_VDD") (pintype "power_in"))
      (node (ref "LED234") (pin "VDD") (pinfunction "VDD_VDD") (pintype "power_in"))
      (node (ref "LED235") (pin "VDD") (pinfunction "VDD_VDD") (pintype "power_in"))
      (node (ref "LED236") (pin "VDD") (pinfunction "VDD_VDD") (pintype "power_in"))
      (node (ref "LED237") (pin "VDD") (pinfunction "VDD_VDD") (pintype "power_in"))
      (node (ref "LED238") (pin "VDD") (pinfunction "VDD_VDD") (pintype "power_in"))
      (node (ref "LED239") (pin "VDD") (pinfunction "VDD_VDD") (pintype "power_in"))
      (node (ref "LED24") (pin "VDD") (pinfunction "VDD_VDD") (pintype "power_in"))
      (node (ref "LED240") (pin "VDD") (pinfunction "VDD_VDD") (pintype "power_in"))
      (node (ref "LED241") (pin "VDD") (pinfunction "VDD_VDD") (pintype "power_in"))
      (node (ref "LED242") (pin "VDD") (pinfunction "VDD_VDD") (pintype "power_in"))
      (node (ref "LED243") (pin "VDD") (pinfunction "VDD_VDD") (pintype "power_in"))
      (node (ref "LED244") (pin "VDD") (pinfunction "VDD_VDD") (pintype "power_in"))
      (node (ref "LED245") (pin "VDD") (pinfunction "VDD_VDD") (pintype "power_in"))
      (node (ref "LED246") (pin "VDD") (pinfunction "VDD_VDD") (pintype "power_in"))
      (node (ref "LED247") (pin "VDD") (pinfunction "VDD_VDD") (pintype "power_in"))
      (node (ref "LED248") (pin "VDD") (pinfunction "VDD_VDD") (pintype "power_in"))
      (node (ref "LED249") (pin "VDD") (pinfunction "VDD_VDD") (pintype "power_in"))
      (node (ref "LED25") (pin "VDD") (pinfunction "VDD_VDD") (pintype "power_in"))
      (node (ref "LED250") (pin "VDD") (pinfunction "VDD_VDD") (pintype "power_in"))
      (node (ref "LED251") (pin "VDD") (pinfunction "VDD_VDD") (pintype "power_in"))
      (node (ref "LED252") (pin "VDD") (pinfunction "VDD_VDD") (pintype "power_in"))
      (node (ref "LED253") (pin "VDD") (pinfunction "VDD_VDD") (pintype "power_in"))
      (node (ref "LED254") (pin "VDD") (pinfunction "VDD_VDD") (pintype "power_in"))
      (node (ref "LED255") (pin "VDD") (pinfunction "VDD_VDD") (pintype "power_in"))
      (node (ref "LED256") (pin "VDD") (pinfunction "VDD_VDD") (pintype "power_in"))
      (node (ref "LED257") (pin "VDD") (pinfunction "VDD_VDD") (pintype "power_in"))
      (node (ref "LED258") (pin "VDD") (pinfunction "VDD_VDD") (pintype "power_in"))
      (node (ref "LED259") (pin "VDD") (pinfunction "VDD_VDD") (pintype "power_in"))
      (node (ref "LED26") (pin "VDD") (pinfunction "VDD_VDD") (pintype "power_in"))
      (node (ref "LED260") (pin "VDD") (pinfunction "VDD_VDD") (pintype "power_in"))
      (node (ref "LED261") (pin "VDD") (pinfunction "VDD_VDD") (pintype "power_in"))
      (node (ref "LED262") (pin "VDD") (pinfunction "VDD_VDD") (pintype "power_in"))
      (node (ref "LED263") (pin "VDD") (pinfunction "VDD_VDD") (pintype "power_in"))
      (node (ref "LED264") (pin "VDD") (pinfunction "VDD_VDD") (pintype "power_in"))
      (node (ref "LED265") (pin "VDD") (pinfunction "VDD_VDD") (pintype "power_in"))
      (node (ref "LED266") (pin "VDD") (pinfunction "VDD_VDD") (pintype "power_in"))
      (node (ref "LED267") (pin "VDD") (pinfunction "VDD_VDD") (pintype "power_in"))
      (node (ref "LED268") (pin "VDD") (pinfunction "VDD_VDD") (pintype "power_in"))
      (node (ref "LED269") (pin "VDD") (pinfunction "VDD_VDD") (pintype "power_in"))
      (node (ref "LED27") (pin "VDD") (pinfunction "VDD_VDD") (pintype "power_in"))
      (node (ref "LED270") (pin "VDD") (pinfunction "VDD_VDD") (pintype "power_in"))
      (node (ref "LED271") (pin "VDD") (pinfunction "VDD_VDD") (pintype "power_in"))
      (node (ref "LED272") (pin "VDD") (pinfunction "VDD_VDD") (pintype "power_in"))
      (node (ref "LED273") (pin "VDD") (pinfunction "VDD_VDD") (pintype "power_in"))
      (node (ref "LED274") (pin "VDD") (pinfunction "VDD_VDD") (pintype "power_in"))
      (node (ref "LED275") (pin "VDD") (pinfunction "VDD_VDD") (pintype "power_in"))
      (node (ref "LED276") (pin "VDD") (pinfunction "VDD_VDD") (pintype "power_in"))
      (node (ref "LED277") (pin "VDD") (pinfunction "VDD_VDD") (pintype "power_in"))
      (node (ref "LED278") (pin "VDD") (pinfunction "VDD_VDD") (pintype "power_in"))
      (node (ref "LED279") (pin "VDD") (pinfunction "VDD_VDD") (pintype "power_in"))
      (node (ref "LED28") (pin "VDD") (pinfunction "VDD_VDD") (pintype "power_in"))
      (node (ref "LED280") (pin "VDD") (pinfunction "VDD_VDD") (pintype "power_in"))
      (node (ref "LED281") (pin "VDD") (pinfunction "VDD_VDD") (pintype "power_in"))
      (node (ref "LED282") (pin "VDD") (pinfunction "VDD_VDD") (pintype "power_in"))
      (node (ref "LED283") (pin "VDD") (pinfunction "VDD_VDD") (pintype "power_in"))
      (node (ref "LED284") (pin "VDD") (pinfunction "VDD_VDD") (pintype "power_in"))
      (node (ref "LED285") (pin "VDD") (pinfunction "VDD_VDD") (pintype "power_in"))
      (node (ref "LED286") (pin "VDD") (pinfunction "VDD_VDD") (pintype "power_in"))
      (node (ref "LED287") (pin "VDD") (pinfunction "VDD_VDD") (pintype "power_in"))
      (node (ref "LED288") (pin "VDD") (pinfunction "VDD_VDD") (pintype "power_in"))
      (node (ref "LED29") (pin "VDD") (pinfunction "VDD_VDD") (pintype "power_in"))
      (node (ref "LED3") (pin "VDD") (pinfunction "VDD_VDD") (pintype "power_in"))
      (node (ref "LED30") (pin "VDD") (pinfunction "VDD_VDD") (pintype "power_in"))
      (node (ref "LED31") (pin "VDD") (pinfunction "VDD_VDD") (pintype "power_in"))
      (node (ref "LED32") (pin "VDD") (pinfunction "VDD_VDD") (pintype "power_in"))
      (node (ref "LED33") (pin "VDD") (pinfunction "VDD_VDD") (pintype "power_in"))
      (node (ref "LED34") (pin "VDD") (pinfunction "VDD_VDD") (pintype "power_in"))
      (node (ref "LED35") (pin "VDD") (pinfunction "VDD_VDD") (pintype "power_in"))
      (node (ref "LED36") (pin "VDD") (pinfunction "VDD_VDD") (pintype "power_in"))
      (node (ref "LED37") (pin "VDD") (pinfunction "VDD_VDD") (pintype "power_in"))
      (node (ref "LED38") (pin "VDD") (pinfunction "VDD_VDD") (pintype "power_in"))
      (node (ref "LED39") (pin "VDD") (pinfunction "VDD_VDD") (pintype "power_in"))
      (node (ref "LED4") (pin "VDD") (pinfunction "VDD_VDD") (pintype "power_in"))
      (node (ref "LED40") (pin "VDD") (pinfunction "VDD_VDD") (pintype "power_in"))
      (node (ref "LED41") (pin "VDD") (pinfunction "VDD_VDD") (pintype "power_in"))
      (node (ref "LED42") (pin "VDD") (pinfunction "VDD_VDD") (pintype "power_in"))
      (node (ref "LED43") (pin "VDD") (pinfunction "VDD_VDD") (pintype "power_in"))
      (node (ref "LED44") (pin "VDD") (pinfunction "VDD_VDD") (pintype "power_in"))
      (node (ref "LED45") (pin "VDD") (pinfunction "VDD_VDD") (pintype "power_in"))
      (node (ref "LED46") (pin "VDD") (pinfunction "VDD_VDD") (pintype "power_in"))
      (node (ref "LED47") (pin "VDD") (pinfunction "VDD_VDD") (pintype "power_in"))
      (node (ref "LED48") (pin "VDD") (pinfunction "VDD_VDD") (pintype "power_in"))
      (node (ref "LED49") (pin "VDD") (pinfunction "VDD_VDD") (pintype "power_in"))
      (node (ref "LED5") (pin "VDD") (pinfunction "VDD_VDD") (pintype "power_in"))
      (node (ref "LED50") (pin "VDD") (pinfunction "VDD_VDD") (pintype "power_in"))
      (node (ref "LED51") (pin "VDD") (pinfunction "VDD_VDD") (pintype "power_in"))
      (node (ref "LED52") (pin "VDD") (pinfunction "VDD_VDD") (pintype "power_in"))
      (node (ref "LED53") (pin "VDD") (pinfunction "VDD_VDD") (pintype "power_in"))
      (node (ref "LED54") (pin "VDD") (pinfunction "VDD_VDD") (pintype "power_in"))
      (node (ref "LED55") (pin "VDD") (pinfunction "VDD_VDD") (pintype "power_in"))
      (node (ref "LED56") (pin "VDD") (pinfunction "VDD_VDD") (pintype "power_in"))
      (node (ref "LED57") (pin "VDD") (pinfunction "VDD_VDD") (pintype "power_in"))
      (node (ref "LED58") (pin "VDD") (pinfunction "VDD_VDD") (pintype "power_in"))
      (node (ref "LED59") (pin "VDD") (pinfunction "VDD_VDD") (pintype "power_in"))
      (node (ref "LED6") (pin "VDD") (pinfunction "VDD_VDD") (pintype "power_in"))
      (node (ref "LED60") (pin "VDD") (pinfunction "VDD_VDD") (pintype "power_in"))
      (node (ref "LED61") (pin "VDD") (pinfunction "VDD_VDD") (pintype "power_in"))
      (node (ref "LED62") (pin "VDD") (pinfunction "VDD_VDD") (pintype "power_in"))
      (node (ref "LED63") (pin "VDD") (pinfunction "VDD_VDD") (pintype "power_in"))
      (node (ref "LED64") (pin "VDD") (pinfunction "VDD_VDD") (pintype "power_in"))
      (node (ref "LED65") (pin "VDD") (pinfunction "VDD_VDD") (pintype "power_in"))
      (node (ref "LED66") (pin "VDD") (pinfunction "VDD_VDD") (pintype "power_in"))
      (node (ref "LED67") (pin "VDD") (pinfunction "VDD_VDD") (pintype "power_in"))
      (node (ref "LED68") (pin "VDD") (pinfunction "VDD_VDD") (pintype "power_in"))
      (node (ref "LED69") (pin "VDD") (pinfunction "VDD_VDD") (pintype "power_in"))
      (node (ref "LED7") (pin "VDD") (pinfunction "VDD_VDD") (pintype "power_in"))
      (node (ref "LED70") (pin "VDD") (pinfunction "VDD_VDD") (pintype "power_in"))
      (node (ref "LED71") (pin "VDD") (pinfunction "VDD_VDD") (pintype "power_in"))
      (node (ref "LED72") (pin "VDD") (pinfunction "VDD_VDD") (pintype "power_in"))
      (node (ref "LED73") (pin "VDD") (pinfunction "VDD_VDD") (pintype "power_in"))
      (node (ref "LED74") (pin "VDD") (pinfunction "VDD_VDD") (pintype "power_in"))
      (node (ref "LED75") (pin "VDD") (pinfunction "VDD_VDD") (pintype "power_in"))
      (node (ref "LED76") (pin "VDD") (pinfunction "VDD_VDD") (pintype "power_in"))
      (node (ref "LED77") (pin "VDD") (pinfunction "VDD_VDD") (pintype "power_in"))
      (node (ref "LED78") (pin "VDD") (pinfunction "VDD_VDD") (pintype "power_in"))
      (node (ref "LED79") (pin "VDD") (pinfunction "VDD_VDD") (pintype "power_in"))
      (node (ref "LED8") (pin "VDD") (pinfunction "VDD_VDD") (pintype "power_in"))
      (node (ref "LED80") (pin "VDD") (pinfunction "VDD_VDD") (pintype "power_in"))
      (node (ref "LED81") (pin "VDD") (pinfunction "VDD_VDD") (pintype "power_in"))
      (node (ref "LED82") (pin "VDD") (pinfunction "VDD_VDD") (pintype "power_in"))
      (node (ref "LED83") (pin "VDD") (pinfunction "VDD_VDD") (pintype "power_in"))
      (node (ref "LED84") (pin "VDD") (pinfunction "VDD_VDD") (pintype "power_in"))
      (node (ref "LED85") (pin "VDD") (pinfunction "VDD_VDD") (pintype "power_in"))
      (node (ref "LED86") (pin "VDD") (pinfunction "VDD_VDD") (pintype "power_in"))
      (node (ref "LED87") (pin "VDD") (pinfunction "VDD_VDD") (pintype "power_in"))
      (node (ref "LED88") (pin "VDD") (pinfunction "VDD_VDD") (pintype "power_in"))
      (node (ref "LED89") (pin "VDD") (pinfunction "VDD_VDD") (pintype "power_in"))
      (node (ref "LED9") (pin "VDD") (pinfunction "VDD_VDD") (pintype "power_in"))
      (node (ref "LED90") (pin "VDD") (pinfunction "VDD_VDD") (pintype "power_in"))
      (node (ref "LED91") (pin "VDD") (pinfunction "VDD_VDD") (pintype "power_in"))
      (node (ref "LED92") (pin "VDD") (pinfunction "VDD_VDD") (pintype "power_in"))
      (node (ref "LED93") (pin "VDD") (pinfunction "VDD_VDD") (pintype "power_in"))
      (node (ref "LED94") (pin "VDD") (pinfunction "VDD_VDD") (pintype "power_in"))
      (node (ref "LED95") (pin "VDD") (pinfunction "VDD_VDD") (pintype "power_in"))
      (node (ref "LED96") (pin "VDD") (pinfunction "VDD_VDD") (pintype "power_in"))
      (node (ref "LED97") (pin "VDD") (pinfunction "VDD_VDD") (pintype "power_in"))
      (node (ref "LED98") (pin "VDD") (pinfunction "VDD_VDD") (pintype "power_in"))
      (node (ref "LED99") (pin "VDD") (pinfunction "VDD_VDD") (pintype "power_in"))
    )
    (net (code "3") (name "DATA") (class "Default")
      (node (ref "IC1") (pin "3") (pinfunction "A_3") (pintype "bidirectional"))
      (node (ref "SJ1") (pin "2") (pinfunction "2_2") (pintype "passive"))
    )
    (net (code "4") (name "DI_FIRST") (class "Default")
      (node (ref "IC1") (pin "4") (pinfunction "B_4") (pintype "bidirectional"))
      (node (ref "J1") (pin "2") (pinfunction "2_2") (pintype "passive"))
      (node (ref "LED1") (pin "DI") (pinfunction "DI_DI") (pintype "input"))
    )
    (net (code "5") (name "DO_LAST") (class "Default")
      (node (ref "J2") (pin "2") (pinfunction "2_2") (pintype "passive"))
      (node (ref "LED288") (pin "DO") (pinfunction "DO_DO") (pintype "output"))
    )
    (net (code "6") (name "DO_MID1") (class "Default")
      (node (ref "LED72") (pin "DO") (pinfunction "DO_DO") (pintype "output"))
      (node (ref "LED73") (pin "DI") (pinfunction "DI_DI") (pintype "input"))
    )
    (net (code "7") (name "DO_MID2") (class "Default")
      (node (ref "LED144") (pin "DO") (pinfunction "DO_DO") (pintype "output"))
      (node (ref "LED145") (pin "DI") (pinfunction "DI_DI") (pintype "input"))
    )
    (net (code "8") (name "DO_MID3") (class "Default")
      (node (ref "LED216") (pin "DO") (pinfunction "DO_DO") (pintype "output"))
      (node (ref "LED217") (pin "DI") (pinfunction "DI_DI") (pintype "input"))
    )
    (net (code "9") (name "GND") (class "Default")
      (node (ref "C1") (pin "2") (pinfunction "2_2") (pintype "passive"))
      (node (ref "C2") (pin "2") (pinfunction "2_2") (pintype "passive"))
      (node (ref "C3") (pin "2") (pinfunction "2_2") (pintype "passive"))
      (node (ref "C4") (pin "2") (pinfunction "2_2") (pintype "passive"))
      (node (ref "C5") (pin "2") (pinfunction "2_2") (pintype "passive"))
      (node (ref "C6") (pin "2") (pinfunction "2_2") (pintype "passive"))
      (node (ref "C7") (pin "2") (pinfunction "2_2") (pintype "passive"))
      (node (ref "C8") (pin "2") (pinfunction "2_2") (pintype "passive"))
      (node (ref "C9") (pin "2") (pinfunction "2_2") (pintype "passive"))
      (node (ref "IC1") (pin "2") (pinfunction "GND_2") (pintype "power_in"))
      (node (ref "J1") (pin "1") (pinfunction "1_1") (pintype "passive"))
      (node (ref "J2") (pin "1") (pinfunction "1_1") (pintype "passive"))
      (node (ref "J5") (pin "13") (pinfunction "13_13") (pintype "passive"))
      (node (ref "J5") (pin "20") (pinfunction "20_20") (pintype "passive"))
      (node (ref "J5") (pin "5") (pinfunction "5_5") (pintype "passive"))
      (node (ref "J6") (pin "10") (pinfunction "10_10") (pintype "passive"))
      (node (ref "J6") (pin "15") (pinfunction "15_15") (pintype "passive"))
      (node (ref "J6") (pin "17") (pinfunction "17_17") (pintype "passive"))
      (node (ref "J6") (pin "3") (pinfunction "3_3") (pintype "passive"))
      (node (ref "J6") (pin "7") (pinfunction "7_7") (pintype "passive"))
      (node (ref "LED1") (pin "GND") (pinfunction "GND_GND") (pintype "power_in"))
      (node (ref "LED10") (pin "GND") (pinfunction "GND_GND") (pintype "power_in"))
      (node (ref "LED100") (pin "GND") (pinfunction "GND_GND") (pintype "power_in"))
      (node (ref "LED101") (pin "GND") (pinfunction "GND_GND") (pintype "power_in"))
      (node (ref "LED102") (pin "GND") (pinfunction "GND_GND") (pintype "power_in"))
      (node (ref "LED103") (pin "GND") (pinfunction "GND_GND") (pintype "power_in"))
      (node (ref "LED104") (pin "GND") (pinfunction "GND_GND") (pintype "power_in"))
      (node (ref "LED105") (pin "GND") (pinfunction "GND_GND") (pintype "power_in"))
      (node (ref "LED106") (pin "GND") (pinfunction "GND_GND") (pintype "power_in"))
      (node (ref "LED107") (pin "GND") (pinfunction "GND_GND") (pintype "power_in"))
      (node (ref "LED108") (pin "GND") (pinfunction "GND_GND") (pintype "power_in"))
      (node (ref "LED109") (pin "GND") (pinfunction "GND_GND") (pintype "power_in"))
      (node (ref "LED11") (pin "GND") (pinfunction "GND_GND") (pintype "power_in"))
      (node (ref "LED110") (pin "GND") (pinfunction "GND_GND") (pintype "power_in"))
      (node (ref "LED111") (pin "GND") (pinfunction "GND_GND") (pintype "power_in"))
      (node (ref "LED112") (pin "GND") (pinfunction "GND_GND") (pintype "power_in"))
      (node (ref "LED113") (pin "GND") (pinfunction "GND_GND") (pintype "power_in"))
      (node (ref "LED114") (pin "GND") (pinfunction "GND_GND") (pintype "power_in"))
      (node (ref "LED115") (pin "GND") (pinfunction "GND_GND") (pintype "power_in"))
      (node (ref "LED116") (pin "GND") (pinfunction "GND_GND") (pintype "power_in"))
      (node (ref "LED117") (pin "GND") (pinfunction "GND_GND") (pintype "power_in"))
      (node (ref "LED118") (pin "GND") (pinfunction "GND_GND") (pintype "power_in"))
      (node (ref "LED119") (pin "GND") (pinfunction "GND_GND") (pintype "power_in"))
      (node (ref "LED12") (pin "GND") (pinfunction "GND_GND") (pintype "power_in"))
      (node (ref "LED120") (pin "GND") (pinfunction "GND_GND") (pintype "power_in"))
      (node (ref "LED121") (pin "GND") (pinfunction "GND_GND") (pintype "power_in"))
      (node (ref "LED122") (pin "GND") (pinfunction "GND_GND") (pintype "power_in"))
      (node (ref "LED123") (pin "GND") (pinfunction "GND_GND") (pintype "power_in"))
      (node (ref "LED124") (pin "GND") (pinfunction "GND_GND") (pintype "power_in"))
      (node (ref "LED125") (pin "GND") (pinfunction "GND_GND") (pintype "power_in"))
      (node (ref "LED126") (pin "GND") (pinfunction "GND_GND") (pintype "power_in"))
      (node (ref "LED127") (pin "GND") (pinfunction "GND_GND") (pintype "power_in"))
      (node (ref "LED128") (pin "GND") (pinfunction "GND_GND") (pintype "power_in"))
      (node (ref "LED129") (pin "GND") (pinfunction "GND_GND") (pintype "power_in"))
      (node (ref "LED13") (pin "GND") (pinfunction "GND_GND") (pintype "power_in"))
      (node (ref "LED130") (pin "GND") (pinfunction "GND_GND") (pintype "power_in"))
      (node (ref "LED131") (pin "GND") (pinfunction "GND_GND") (pintype "power_in"))
      (node (ref "LED132") (pin "GND") (pinfunction "GND_GND") (pintype "power_in"))
      (node (ref "LED133") (pin "GND") (pinfunction "GND_GND") (pintype "power_in"))
      (node (ref "LED134") (pin "GND") (pinfunction "GND_GND") (pintype "power_in"))
      (node (ref "LED135") (pin "GND") (pinfunction "GND_GND") (pintype "power_in"))
      (node (ref "LED136") (pin "GND") (pinfunction "GND_GND") (pintype "power_in"))
      (node (ref "LED137") (pin "GND") (pinfunction "GND_GND") (pintype "power_in"))
      (node (ref "LED138") (pin "GND") (pinfunction "GND_GND") (pintype "power_in"))
      (node (ref "LED139") (pin "GND") (pinfunction "GND_GND") (pintype "power_in"))
      (node (ref "LED14") (pin "GND") (pinfunction "GND_GND") (pintype "power_in"))
      (node (ref "LED140") (pin "GND") (pinfunction "GND_GND") (pintype "power_in"))
      (node (ref "LED141") (pin "GND") (pinfunction "GND_GND") (pintype "power_in"))
      (node (ref "LED142") (pin "GND") (pinfunction "GND_GND") (pintype "power_in"))
      (node (ref "LED143") (pin "GND") (pinfunction "GND_GND") (pintype "power_in"))
      (node (ref "LED144") (pin "GND") (pinfunction "GND_GND") (pintype "power_in"))
      (node (ref "LED145") (pin "GND") (pinfunction "GND_GND") (pintype "power_in"))
      (node (ref "LED146") (pin "GND") (pinfunction "GND_GND") (pintype "power_in"))
      (node (ref "LED147") (pin "GND") (pinfunction "GND_GND") (pintype "power_in"))
      (node (ref "LED148") (pin "GND") (pinfunction "GND_GND") (pintype "power_in"))
      (node (ref "LED149") (pin "GND") (pinfunction "GND_GND") (pintype "power_in"))
      (node (ref "LED15") (pin "GND") (pinfunction "GND_GND") (pintype "power_in"))
      (node (ref "LED150") (pin "GND") (pinfunction "GND_GND") (pintype "power_in"))
      (node (ref "LED151") (pin "GND") (pinfunction "GND_GND") (pintype "power_in"))
      (node (ref "LED152") (pin "GND") (pinfunction "GND_GND") (pintype "power_in"))
      (node (ref "LED153") (pin "GND") (pinfunction "GND_GND") (pintype "power_in"))
      (node (ref "LED154") (pin "GND") (pinfunction "GND_GND") (pintype "power_in"))
      (node (ref "LED155") (pin "GND") (pinfunction "GND_GND") (pintype "power_in"))
      (node (ref "LED156") (pin "GND") (pinfunction "GND_GND") (pintype "power_in"))
      (node (ref "LED157") (pin "GND") (pinfunction "GND_GND") (pintype "power_in"))
      (node (ref "LED158") (pin "GND") (pinfunction "GND_GND") (pintype "power_in"))
      (node (ref "LED159") (pin "GND") (pinfunction "GND_GND") (pintype "power_in"))
      (node (ref "LED16") (pin "GND") (pinfunction "GND_GND") (pintype "power_in"))
      (node (ref "LED160") (pin "GND") (pinfunction "GND_GND") (pintype "power_in"))
      (node (ref "LED161") (pin "GND") (pinfunction "GND_GND") (pintype "power_in"))
      (node (ref "LED162") (pin "GND") (pinfunction "GND_GND") (pintype "power_in"))
      (node (ref "LED163") (pin "GND") (pinfunction "GND_GND") (pintype "power_in"))
      (node (ref "LED164") (pin "GND") (pinfunction "GND_GND") (pintype "power_in"))
      (node (ref "LED165") (pin "GND") (pinfunction "GND_GND") (pintype "power_in"))
      (node (ref "LED166") (pin "GND") (pinfunction "GND_GND") (pintype "power_in"))
      (node (ref "LED167") (pin "GND") (pinfunction "GND_GND") (pintype "power_in"))
      (node (ref "LED168") (pin "GND") (pinfunction "GND_GND") (pintype "power_in"))
      (node (ref "LED169") (pin "GND") (pinfunction "GND_GND") (pintype "power_in"))
      (node (ref "LED17") (pin "GND") (pinfunction "GND_GND") (pintype "power_in"))
      (node (ref "LED170") (pin "GND") (pinfunction "GND_GND") (pintype "power_in"))
      (node (ref "LED171") (pin "GND") (pinfunction "GND_GND") (pintype "power_in"))
      (node (ref "LED172") (pin "GND") (pinfunction "GND_GND") (pintype "power_in"))
      (node (ref "LED173") (pin "GND") (pinfunction "GND_GND") (pintype "power_in"))
      (node (ref "LED174") (pin "GND") (pinfunction "GND_GND") (pintype "power_in"))
      (node (ref "LED175") (pin "GND") (pinfunction "GND_GND") (pintype "power_in"))
      (node (ref "LED176") (pin "GND") (pinfunction "GND_GND") (pintype "power_in"))
      (node (ref "LED177") (pin "GND") (pinfunction "GND_GND") (pintype "power_in"))
      (node (ref "LED178") (pin "GND") (pinfunction "GND_GND") (pintype "power_in"))
      (node (ref "LED179") (pin "GND") (pinfunction "GND_GND") (pintype "power_in"))
      (node (ref "LED18") (pin "GND") (pinfunction "GND_GND") (pintype "power_in"))
      (node (ref "LED180") (pin "GND") (pinfunction "GND_GND") (pintype "power_in"))
      (node (ref "LED181") (pin "GND") (pinfunction "GND_GND") (pintype "power_in"))
      (node (ref "LED182") (pin "GND") (pinfunction "GND_GND") (pintype "power_in"))
      (node (ref "LED183") (pin "GND") (pinfunction "GND_GND") (pintype "power_in"))
      (node (ref "LED184") (pin "GND") (pinfunction "GND_GND") (pintype "power_in"))
      (node (ref "LED185") (pin "GND") (pinfunction "GND_GND") (pintype "power_in"))
      (node (ref "LED186") (pin "GND") (pinfunction "GND_GND") (pintype "power_in"))
      (node (ref "LED187") (pin "GND") (pinfunction "GND_GND") (pintype "power_in"))
      (node (ref "LED188") (pin "GND") (pinfunction "GND_GND") (pintype "power_in"))
      (node (ref "LED189") (pin "GND") (pinfunction "GND_GND") (pintype "power_in"))
      (node (ref "LED19") (pin "GND") (pinfunction "GND_GND") (pintype "power_in"))
      (node (ref "LED190") (pin "GND") (pinfunction "GND_GND") (pintype "power_in"))
      (node (ref "LED191") (pin "GND") (pinfunction "GND_GND") (pintype "power_in"))
      (node (ref "LED192") (pin "GND") (pinfunction "GND_GND") (pintype "power_in"))
      (node (ref "LED193") (pin "GND") (pinfunction "GND_GND") (pintype "power_in"))
      (node (ref "LED194") (pin "GND") (pinfunction "GND_GND") (pintype "power_in"))
      (node (ref "LED195") (pin "GND") (pinfunction "GND_GND") (pintype "power_in"))
      (node (ref "LED196") (pin "GND") (pinfunction "GND_GND") (pintype "power_in"))
      (node (ref "LED197") (pin "GND") (pinfunction "GND_GND") (pintype "power_in"))
      (node (ref "LED198") (pin "GND") (pinfunction "GND_GND") (pintype "power_in"))
      (node (ref "LED199") (pin "GND") (pinfunction "GND_GND") (pintype "power_in"))
      (node (ref "LED2") (pin "GND") (pinfunction "GND_GND") (pintype "power_in"))
      (node (ref "LED20") (pin "GND") (pinfunction "GND_GND") (pintype "power_in"))
      (node (ref "LED200") (pin "GND") (pinfunction "GND_GND") (pintype "power_in"))
      (node (ref "LED201") (pin "GND") (pinfunction "GND_GND") (pintype "power_in"))
      (node (ref "LED202") (pin "GND") (pinfunction "GND_GND") (pintype "power_in"))
      (node (ref "LED203") (pin "GND") (pinfunction "GND_GND") (pintype "power_in"))
      (node (ref "LED204") (pin "GND") (pinfunction "GND_GND") (pintype "power_in"))
      (node (ref "LED205") (pin "GND") (pinfunction "GND_GND") (pintype "power_in"))
      (node (ref "LED206") (pin "GND") (pinfunction "GND_GND") (pintype "power_in"))
      (node (ref "LED207") (pin "GND") (pinfunction "GND_GND") (pintype "power_in"))
      (node (ref "LED208") (pin "GND") (pinfunction "GND_GND") (pintype "power_in"))
      (node (ref "LED209") (pin "GND") (pinfunction "GND_GND") (pintype "power_in"))
      (node (ref "LED21") (pin "GND") (pinfunction "GND_GND") (pintype "power_in"))
      (node (ref "LED210") (pin "GND") (pinfunction "GND_GND") (pintype "power_in"))
      (node (ref "LED211") (pin "GND") (pinfunction "GND_GND") (pintype "power_in"))
      (node (ref "LED212") (pin "GND") (pinfunction "GND_GND") (pintype "power_in"))
      (node (ref "LED213") (pin "GND") (pinfunction "GND_GND") (pintype "power_in"))
      (node (ref "LED214") (pin "GND") (pinfunction "GND_GND") (pintype "power_in"))
      (node (ref "LED215") (pin "GND") (pinfunction "GND_GND") (pintype "power_in"))
      (node (ref "LED216") (pin "GND") (pinfunction "GND_GND") (pintype "power_in"))
      (node (ref "LED217") (pin "GND") (pinfunction "GND_GND") (pintype "power_in"))
      (node (ref "LED218") (pin "GND") (pinfunction "GND_GND") (pintype "power_in"))
      (node (ref "LED219") (pin "GND") (pinfunction "GND_GND") (pintype "power_in"))
      (node (ref "LED22") (pin "GND") (pinfunction "GND_GND") (pintype "power_in"))
      (node (ref "LED220") (pin "GND") (pinfunction "GND_GND") (pintype "power_in"))
      (node (ref "LED221") (pin "GND") (pinfunction "GND_GND") (pintype "power_in"))
      (node (ref "LED222") (pin "GND") (pinfunction "GND_GND") (pintype "power_in"))
      (node (ref "LED223") (pin "GND") (pinfunction "GND_GND") (pintype "power_in"))
      (node (ref "LED224") (pin "GND") (pinfunction "GND_GND") (pintype "power_in"))
      (node (ref "LED225") (pin "GND") (pinfunction "GND_GND") (pintype "power_in"))
      (node (ref "LED226") (pin "GND") (pinfunction "GND_GND") (pintype "power_in"))
      (node (ref "LED227") (pin "GND") (pinfunction "GND_GND") (pintype "power_in"))
      (node (ref "LED228") (pin "GND") (pinfunction "GND_GND") (pintype "power_in"))
      (node (ref "LED229") (pin "GND") (pinfunction "GND_GND") (pintype "power_in"))
      (node (ref "LED23") (pin "GND") (pinfunction "GND_GND") (pintype "power_in"))
      (node (ref "LED230") (pin "GND") (pinfunction "GND_GND") (pintype "power_in"))
      (node (ref "LED231") (pin "GND") (pinfunction "GND_GND") (pintype "power_in"))
      (node (ref "LED232") (pin "GND") (pinfunction "GND_GND") (pintype "power_in"))
      (node (ref "LED233") (pin "GND") (pinfunction "GND_GND") (pintype "power_in"))
      (node (ref "LED234") (pin "GND") (pinfunction "GND_GND") (pintype "power_in"))
      (node (ref "LED235") (pin "GND") (pinfunction "GND_GND") (pintype "power_in"))
      (node (ref "LED236") (pin "GND") (pinfunction "GND_GND") (pintype "power_in"))
      (node (ref "LED237") (pin "GND") (pinfunction "GND_GND") (pintype "power_in"))
      (node (ref "LED238") (pin "GND") (pinfunction "GND_GND") (pintype "power_in"))
      (node (ref "LED239") (pin "GND") (pinfunction "GND_GND") (pintype "power_in"))
      (node (ref "LED24") (pin "GND") (pinfunction "GND_GND") (pintype "power_in"))
      (node (ref "LED240") (pin "GND") (pinfunction "GND_GND") (pintype "power_in"))
      (node (ref "LED241") (pin "GND") (pinfunction "GND_GND") (pintype "power_in"))
      (node (ref "LED242") (pin "GND") (pinfunction "GND_GND") (pintype "power_in"))
      (node (ref "LED243") (pin "GND") (pinfunction "GND_GND") (pintype "power_in"))
      (node (ref "LED244") (pin "GND") (pinfunction "GND_GND") (pintype "power_in"))
      (node (ref "LED245") (pin "GND") (pinfunction "GND_GND") (pintype "power_in"))
      (node (ref "LED246") (pin "GND") (pinfunction "GND_GND") (pintype "power_in"))
      (node (ref "LED247") (pin "GND") (pinfunction "GND_GND") (pintype "power_in"))
      (node (ref "LED248") (pin "GND") (pinfunction "GND_GND") (pintype "power_in"))
      (node (ref "LED249") (pin "GND") (pinfunction "GND_GND") (pintype "power_in"))
      (node (ref "LED25") (pin "GND") (pinfunction "GND_GND") (pintype "power_in"))
      (node (ref "LED250") (pin "GND") (pinfunction "GND_GND") (pintype "power_in"))
      (node (ref "LED251") (pin "GND") (pinfunction "GND_GND") (pintype "power_in"))
      (node (ref "LED252") (pin "GND") (pinfunction "GND_GND") (pintype "power_in"))
      (node (ref "LED253") (pin "GND") (pinfunction "GND_GND") (pintype "power_in"))
      (node (ref "LED254") (pin "GND") (pinfunction "GND_GND") (pintype "power_in"))
      (node (ref "LED255") (pin "GND") (pinfunction "GND_GND") (pintype "power_in"))
      (node (ref "LED256") (pin "GND") (pinfunction "GND_GND") (pintype "power_in"))
      (node (ref "LED257") (pin "GND") (pinfunction "GND_GND") (pintype "power_in"))
      (node (ref "LED258") (pin "GND") (pinfunction "GND_GND") (pintype "power_in"))
      (node (ref "LED259") (pin "GND") (pinfunction "GND_GND") (pintype "power_in"))
      (node (ref "LED26") (pin "GND") (pinfunction "GND_GND") (pintype "power_in"))
      (node (ref "LED260") (pin "GND") (pinfunction "GND_GND") (pintype "power_in"))
      (node (ref "LED261") (pin "GND") (pinfunction "GND_GND") (pintype "power_in"))
      (node (ref "LED262") (pin "GND") (pinfunction "GND_GND") (pintype "power_in"))
      (node (ref "LED263") (pin "GND") (pinfunction "GND_GND") (pintype "power_in"))
      (node (ref "LED264") (pin "GND") (pinfunction "GND_GND") (pintype "power_in"))
      (node (ref "LED265") (pin "GND") (pinfunction "GND_GND") (pintype "power_in"))
      (node (ref "LED266") (pin "GND") (pinfunction "GND_GND") (pintype "power_in"))
      (node (ref "LED267") (pin "GND") (pinfunction "GND_GND") (pintype "power_in"))
      (node (ref "LED268") (pin "GND") (pinfunction "GND_GND") (pintype "power_in"))
      (node (ref "LED269") (pin "GND") (pinfunction "GND_GND") (pintype "power_in"))
      (node (ref "LED27") (pin "GND") (pinfunction "GND_GND") (pintype "power_in"))
      (node (ref "LED270") (pin "GND") (pinfunction "GND_GND") (pintype "power_in"))
      (node (ref "LED271") (pin "GND") (pinfunction "GND_GND") (pintype "power_in"))
      (node (ref "LED272") (pin "GND") (pinfunction "GND_GND") (pintype "power_in"))
      (node (ref "LED273") (pin "GND") (pinfunction "GND_GND") (pintype "power_in"))
      (node (ref "LED274") (pin "GND") (pinfunction "GND_GND") (pintype "power_in"))
      (node (ref "LED275") (pin "GND") (pinfunction "GND_GND") (pintype "power_in"))
      (node (ref "LED276") (pin "GND") (pinfunction "GND_GND") (pintype "power_in"))
      (node (ref "LED277") (pin "GND") (pinfunction "GND_GND") (pintype "power_in"))
      (node (ref "LED278") (pin "GND") (pinfunction "GND_GND") (pintype "power_in"))
      (node (ref "LED279") (pin "GND") (pinfunction "GND_GND") (pintype "power_in"))
      (node (ref "LED28") (pin "GND") (pinfunction "GND_GND") (pintype "power_in"))
      (node (ref "LED280") (pin "GND") (pinfunction "GND_GND") (pintype "power_in"))
      (node (ref "LED281") (pin "GND") (pinfunction "GND_GND") (pintype "power_in"))
      (node (ref "LED282") (pin "GND") (pinfunction "GND_GND") (pintype "power_in"))
      (node (ref "LED283") (pin "GND") (pinfunction "GND_GND") (pintype "power_in"))
      (node (ref "LED284") (pin "GND") (pinfunction "GND_GND") (pintype "power_in"))
      (node (ref "LED285") (pin "GND") (pinfunction "GND_GND") (pintype "power_in"))
      (node (ref "LED286") (pin "GND") (pinfunction "GND_GND") (pintype "power_in"))
      (node (ref "LED287") (pin "GND") (pinfunction "GND_GND") (pintype "power_in"))
      (node (ref "LED288") (pin "GND") (pinfunction "GND_GND") (pintype "power_in"))
      (node (ref "LED29") (pin "GND") (pinfunction "GND_GND") (pintype "power_in"))
      (node (ref "LED3") (pin "GND") (pinfunction "GND_GND") (pintype "power_in"))
      (node (ref "LED30") (pin "GND") (pinfunction "GND_GND") (pintype "power_in"))
      (node (ref "LED31") (pin "GND") (pinfunction "GND_GND") (pintype "power_in"))
      (node (ref "LED32") (pin "GND") (pinfunction "GND_GND") (pintype "power_in"))
      (node (ref "LED33") (pin "GND") (pinfunction "GND_GND") (pintype "power_in"))
      (node (ref "LED34") (pin "GND") (pinfunction "GND_GND") (pintype "power_in"))
      (node (ref "LED35") (pin "GND") (pinfunction "GND_GND") (pintype "power_in"))
      (node (ref "LED36") (pin "GND") (pinfunction "GND_GND") (pintype "power_in"))
      (node (ref "LED37") (pin "GND") (pinfunction "GND_GND") (pintype "power_in"))
      (node (ref "LED38") (pin "GND") (pinfunction "GND_GND") (pintype "power_in"))
      (node (ref "LED39") (pin "GND") (pinfunction "GND_GND") (pintype "power_in"))
      (node (ref "LED4") (pin "GND") (pinfunction "GND_GND") (pintype "power_in"))
      (node (ref "LED40") (pin "GND") (pinfunction "GND_GND") (pintype "power_in"))
      (node (ref "LED41") (pin "GND") (pinfunction "GND_GND") (pintype "power_in"))
      (node (ref "LED42") (pin "GND") (pinfunction "GND_GND") (pintype "power_in"))
      (node (ref "LED43") (pin "GND") (pinfunction "GND_GND") (pintype "power_in"))
      (node (ref "LED44") (pin "GND") (pinfunction "GND_GND") (pintype "power_in"))
      (node (ref "LED45") (pin "GND") (pinfunction "GND_GND") (pintype "power_in"))
      (node (ref "LED46") (pin "GND") (pinfunction "GND_GND") (pintype "power_in"))
      (node (ref "LED47") (pin "GND") (pinfunction "GND_GND") (pintype "power_in"))
      (node (ref "LED48") (pin "GND") (pinfunction "GND_GND") (pintype "power_in"))
      (node (ref "LED49") (pin "GND") (pinfunction "GND_GND") (pintype "power_in"))
      (node (ref "LED5") (pin "GND") (pinfunction "GND_GND") (pintype "power_in"))
      (node (ref "LED50") (pin "GND") (pinfunction "GND_GND") (pintype "power_in"))
      (node (ref "LED51") (pin "GND") (pinfunction "GND_GND") (pintype "power_in"))
      (node (ref "LED52") (pin "GND") (pinfunction "GND_GND") (pintype "power_in"))
      (node (ref "LED53") (pin "GND") (pinfunction "GND_GND") (pintype "power_in"))
      (node (ref "LED54") (pin "GND") (pinfunction "GND_GND") (pintype "power_in"))
      (node (ref "LED55") (pin "GND") (pinfunction "GND_GND") (pintype "power_in"))
      (node (ref "LED56") (pin "GND") (pinfunction "GND_GND") (pintype "power_in"))
      (node (ref "LED57") (pin "GND") (pinfunction "GND_GND") (pintype "power_in"))
      (node (ref "LED58") (pin "GND") (pinfunction "GND_GND") (pintype "power_in"))
      (node (ref "LED59") (pin "GND") (pinfunction "GND_GND") (pintype "power_in"))
      (node (ref "LED6") (pin "GND") (pinfunction "GND_GND") (pintype "power_in"))
      (node (ref "LED60") (pin "GND") (pinfunction "GND_GND") (pintype "power_in"))
      (node (ref "LED61") (pin "GND") (pinfunction "GND_GND") (pintype "power_in"))
      (node (ref "LED62") (pin "GND") (pinfunction "GND_GND") (pintype "power_in"))
      (node (ref "LED63") (pin "GND") (pinfunction "GND_GND") (pintype "power_in"))
      (node (ref "LED64") (pin "GND") (pinfunction "GND_GND") (pintype "power_in"))
      (node (ref "LED65") (pin "GND") (pinfunction "GND_GND") (pintype "power_in"))
      (node (ref "LED66") (pin "GND") (pinfunction "GND_GND") (pintype "power_in"))
      (node (ref "LED67") (pin "GND") (pinfunction "GND_GND") (pintype "power_in"))
      (node (ref "LED68") (pin "GND") (pinfunction "GND_GND") (pintype "power_in"))
      (node (ref "LED69") (pin "GND") (pinfunction "GND_GND") (pintype "power_in"))
      (node (ref "LED7") (pin "GND") (pinfunction "GND_GND") (pintype "power_in"))
      (node (ref "LED70") (pin "GND") (pinfunction "GND_GND") (pintype "power_in"))
      (node (ref "LED71") (pin "GND") (pinfunction "GND_GND") (pintype "power_in"))
      (node (ref "LED72") (pin "GND") (pinfunction "GND_GND") (pintype "power_in"))
      (node (ref "LED73") (pin "GND") (pinfunction "GND_GND") (pintype "power_in"))
      (node (ref "LED74") (pin "GND") (pinfunction "GND_GND") (pintype "power_in"))
      (node (ref "LED75") (pin "GND") (pinfunction "GND_GND") (pintype "power_in"))
      (node (ref "LED76") (pin "GND") (pinfunction "GND_GND") (pintype "power_in"))
      (node (ref "LED77") (pin "GND") (pinfunction "GND_GND") (pintype "power_in"))
      (node (ref "LED78") (pin "GND") (pinfunction "GND_GND") (pintype "power_in"))
      (node (ref "LED79") (pin "GND") (pinfunction "GND_GND") (pintype "power_in"))
      (node (ref "LED8") (pin "GND") (pinfunction "GND_GND") (pintype "power_in"))
      (node (ref "LED80") (pin "GND") (pinfunction "GND_GND") (pintype "power_in"))
      (node (ref "LED81") (pin "GND") (pinfunction "GND_GND") (pintype "power_in"))
      (node (ref "LED82") (pin "GND") (pinfunction "GND_GND") (pintype "power_in"))
      (node (ref "LED83") (pin "GND") (pinfunction "GND_GND") (pintype "power_in"))
      (node (ref "LED84") (pin "GND") (pinfunction "GND_GND") (pintype "power_in"))
      (node (ref "LED85") (pin "GND") (pinfunction "GND_GND") (pintype "power_in"))
      (node (ref "LED86") (pin "GND") (pinfunction "GND_GND") (pintype "power_in"))
      (node (ref "LED87") (pin "GND") (pinfunction "GND_GND") (pintype "power_in"))
      (node (ref "LED88") (pin "GND") (pinfunction "GND_GND") (pintype "power_in"))
      (node (ref "LED89") (pin "GND") (pinfunction "GND_GND") (pintype "power_in"))
      (node (ref "LED9") (pin "GND") (pinfunction "GND_GND") (pintype "power_in"))
      (node (ref "LED90") (pin "GND") (pinfunction "GND_GND") (pintype "power_in"))
      (node (ref "LED91") (pin "GND") (pinfunction "GND_GND") (pintype "power_in"))
      (node (ref "LED92") (pin "GND") (pinfunction "GND_GND") (pintype "power_in"))
      (node (ref "LED93") (pin "GND") (pinfunction "GND_GND") (pintype "power_in"))
      (node (ref "LED94") (pin "GND") (pinfunction "GND_GND") (pintype "power_in"))
      (node (ref "LED95") (pin "GND") (pinfunction "GND_GND") (pintype "power_in"))
      (node (ref "LED96") (pin "GND") (pinfunction "GND_GND") (pintype "power_in"))
      (node (ref "LED97") (pin "GND") (pinfunction "GND_GND") (pintype "power_in"))
      (node (ref "LED98") (pin "GND") (pinfunction "GND_GND") (pintype "power_in"))
      (node (ref "LED99") (pin "GND") (pinfunction "GND_GND") (pintype "power_in"))
    )
    (net (code "10") (name "GPIO0") (class "Default")
      (node (ref "J5") (pin "14") (pinfunction "14_14") (pintype "passive"))
    )
    (net (code "11") (name "GPIO1") (class "Default")
      (node (ref "J6") (pin "14") (pinfunction "14_14") (pintype "passive"))
    )
    (net (code "12") (name "GPIO2") (class "Default")
      (node (ref "J5") (pin "2") (pinfunction "2_2") (pintype "passive"))
    )
    (net (code "13") (name "GPIO3") (class "Default")
      (node (ref "J5") (pin "3") (pinfunction "3_3") (pintype "passive"))
    )
    (net (code "14") (name "GPIO4") (class "Default")
      (node (ref "J5") (pin "4") (pinfunction "4_4") (pintype "passive"))
    )
    (net (code "15") (name "GPIO5") (class "Default")
      (node (ref "J5") (pin "15") (pinfunction "15_15") (pintype "passive"))
    )
    (net (code "16") (name "GPIO6") (class "Default")
      (node (ref "J5") (pin "16") (pinfunction "16_16") (pintype "passive"))
    )
    (net (code "17") (name "GPIO7") (class "Default")
      (node (ref "J6") (pin "13") (pinfunction "13_13") (pintype "passive"))
    )
    (net (code "18") (name "GPIO8") (class "Default")
      (node (ref "J6") (pin "12") (pinfunction "12_12") (pintype "passive"))
    )
    (net (code "19") (name "GPIO9") (class "Default")
      (node (ref "J5") (pin "11") (pinfunction "11_11") (pintype "passive"))
    )
    (net (code "20") (name "GPIO10") (class "Default")
      (node (ref "J5") (pin "10") (pinfunction "10_10") (pintype "passive"))
      (node (ref "SJ1") (pin "3") (pinfunction "3_3") (pintype "passive"))
    )
    (net (code "21") (name "GPIO11") (class "Default")
      (node (ref "J5") (pin "12") (pinfunction "12_12") (pintype "passive"))
    )
    (net (code "22") (name "GPIO12") (class "Default")
      (node (ref "J6") (pin "16") (pinfunction "16_16") (pintype "passive"))
    )
    (net (code "23") (name "GPIO13") (class "Default")
      (node (ref "J5") (pin "17") (pinfunction "17_17") (pintype "passive"))
    )
    (net (code "24") (name "GPIO14") (class "Default")
      (node (ref "J6") (pin "4") (pinfunction "4_4") (pintype "passive"))
    )
    (net (code "25") (name "GPIO15") (class "Default")
      (node (ref "J6") (pin "5") (pinfunction "5_5") (pintype "passive"))
    )
    (net (code "26") (name "GPIO16") (class "Default")
      (node (ref "J6") (pin "18") (pinfunction "18_18") (pintype "passive"))
    )
    (net (code "27") (name "GPIO17") (class "Default")
      (node (ref "J5") (pin "6") (pinfunction "6_6") (pintype "passive"))
    )
    (net (code "28") (name "GPIO18") (class "Default")
      (node (ref "J6") (pin "6") (pinfunction "6_6") (pintype "passive"))
      (node (ref "SJ1") (pin "4") (pinfunction "4_4") (pintype "passive"))
    )
    (net (code "29") (name "GPIO19") (class "Default")
      (node (ref "J5") (pin "18") (pinfunction "18_18") (pintype "passive"))
    )
    (net (code "30") (name "GPIO20") (class "Default")
      (node (ref "J6") (pin "19") (pinfunction "19_19") (pintype "passive"))
    )
    (net (code "31") (name "GPIO21") (class "Default")
      (node (ref "J6") (pin "20") (pinfunction "20_20") (pintype "passive"))
      (node (ref "SJ1") (pin "1") (pinfunction "1_1") (pintype "passive"))
    )
    (net (code "32") (name "GPIO22") (class "Default")
      (node (ref "J5") (pin "8") (pinfunction "8_8") (pintype "passive"))
    )
    (net (code "33") (name "GPIO23") (class "Default")
      (node (ref "J6") (pin "8") (pinfunction "8_8") (pintype "passive"))
    )
    (net (code "34") (name "GPIO24") (class "Default")
      (node (ref "J6") (pin "9") (pinfunction "9_9") (pintype "passive"))
    )
    (net (code "35") (name "GPIO25") (class "Default")
      (node (ref "J6") (pin "11") (pinfunction "11_11") (pintype "passive"))
    )
    (net (code "36") (name "GPIO26") (class "Default")
      (node (ref "J5") (pin "19") (pinfunction "19_19") (pintype "passive"))
    )
    (net (code "37") (name "GPIO27") (class "Default")
      (node (ref "J5") (pin "7") (pinfunction "7_7") (pintype "passive"))
    )
    (net (code "38") (name "Net-(IC1-OE)") (class "Default")
      (node (ref "IC1") (pin "5") (pinfunction "OE_5") (pintype "input"))
      (node (ref "R1") (pin "2") (pinfunction "2_2") (pintype "passive"))
    )
    (net (code "39") (name "Net-(LED1-PadDO)") (class "Default")
      (node (ref "LED1") (pin "DO") (pinfunction "DO_DO") (pintype "output"))
      (node (ref "LED2") (pin "DI") (pinfunction "DI_DI") (pintype "input"))
    )
    (net (code "40") (name "Net-(LED2-PadDO)") (class "Default")
      (node (ref "LED2") (pin "DO") (pinfunction "DO_DO") (pintype "output"))
      (node (ref "LED3") (pin "DI") (pinfunction "DI_DI") (pintype "input"))
    )
    (net (code "41") (name "Net-(LED3-PadDO)") (class "Default")
      (node (ref "LED3") (pin "DO") (pinfunction "DO_DO") (pintype "output"))
      (node (ref "LED4") (pin "DI") (pinfunction "DI_DI") (pintype "input"))
    )
    (net (code "42") (name "Net-(LED4-PadDO)") (class "Default")
      (node (ref "LED4") (pin "DO") (pinfunction "DO_DO") (pintype "output"))
      (node (ref "LED5") (pin "DI") (pinfunction "DI_DI") (pintype "input"))
    )
    (net (code "43") (name "Net-(LED5-PadDO)") (class "Default")
      (node (ref "LED5") (pin "DO") (pinfunction "DO_DO") (pintype "output"))
      (node (ref "LED6") (pin "DI") (pinfunction "DI_DI") (pintype "input"))
    )
    (net (code "44") (name "Net-(LED6-PadDO)") (class "Default")
      (node (ref "LED6") (pin "DO") (pinfunction "DO_DO") (pintype "output"))
      (node (ref "LED7") (pin "DI") (pinfunction "DI_DI") (pintype "input"))
    )
    (net (code "45") (name "Net-(LED7-PadDO)") (class "Default")
      (node (ref "LED7") (pin "DO") (pinfunction "DO_DO") (pintype "output"))
      (node (ref "LED8") (pin "DI") (pinfunction "DI_DI") (pintype "input"))
    )
    (net (code "46") (name "Net-(LED8-PadDO)") (class "Default")
      (node (ref "LED8") (pin "DO") (pinfunction "DO_DO") (pintype "output"))
      (node (ref "LED9") (pin "DI") (pinfunction "DI_DI") (pintype "input"))
    )
    (net (code "47") (name "Net-(LED10-PadDI)") (class "Default")
      (node (ref "LED10") (pin "DI") (pinfunction "DI_DI") (pintype "input"))
      (node (ref "LED9") (pin "DO") (pinfunction "DO_DO") (pintype "output"))
    )
    (net (code "48") (name "Net-(LED10-PadDO)") (class "Default")
      (node (ref "LED10") (pin "DO") (pinfunction "DO_DO") (pintype "output"))
      (node (ref "LED11") (pin "DI") (pinfunction "DI_DI") (pintype "input"))
    )
    (net (code "49") (name "Net-(LED11-PadDO)") (class "Default")
      (node (ref "LED11") (pin "DO") (pinfunction "DO_DO") (pintype "output"))
      (node (ref "LED12") (pin "DI") (pinfunction "DI_DI") (pintype "input"))
    )
    (net (code "50") (name "Net-(LED12-PadDO)") (class "Default")
      (node (ref "LED12") (pin "DO") (pinfunction "DO_DO") (pintype "output"))
      (node (ref "LED13") (pin "DI") (pinfunction "DI_DI") (pintype "input"))
    )
    (net (code "51") (name "Net-(LED13-PadDO)") (class "Default")
      (node (ref "LED13") (pin "DO") (pinfunction "DO_DO") (pintype "output"))
      (node (ref "LED14") (pin "DI") (pinfunction "DI_DI") (pintype "input"))
    )
    (net (code "52") (name "Net-(LED14-PadDO)") (class "Default")
      (node (ref "LED14") (pin "DO") (pinfunction "DO_DO") (pintype "output"))
      (node (ref "LED15") (pin "DI") (pinfunction "DI_DI") (pintype "input"))
    )
    (net (code "53") (name "Net-(LED15-PadDO)") (class "Default")
      (node (ref "LED15") (pin "DO") (pinfunction "DO_DO") (pintype "output"))
      (node (ref "LED16") (pin "DI") (pinfunction "DI_DI") (pintype "input"))
    )
    (net (code "54") (name "Net-(LED16-PadDO)") (class "Default")
      (node (ref "LED16") (pin "DO") (pinfunction "DO_DO") (pintype "output"))
      (node (ref "LED17") (pin "DI") (pinfunction "DI_DI") (pintype "input"))
    )
    (net (code "55") (name "Net-(LED17-PadDO)") (class "Default")
      (node (ref "LED17") (pin "DO") (pinfunction "DO_DO") (pintype "output"))
      (node (ref "LED18") (pin "DI") (pinfunction "DI_DI") (pintype "input"))
    )
    (net (code "56") (name "Net-(LED18-PadDO)") (class "Default")
      (node (ref "LED18") (pin "DO") (pinfunction "DO_DO") (pintype "output"))
      (node (ref "LED19") (pin "DI") (pinfunction "DI_DI") (pintype "input"))
    )
    (net (code "57") (name "Net-(LED19-PadDO)") (class "Default")
      (node (ref "LED19") (pin "DO") (pinfunction "DO_DO") (pintype "output"))
      (node (ref "LED20") (pin "DI") (pinfunction "DI_DI") (pintype "input"))
    )
    (net (code "58") (name "Net-(LED20-PadDO)") (class "Default")
      (node (ref "LED20") (pin "DO") (pinfunction "DO_DO") (pintype "output"))
      (node (ref "LED21") (pin "DI") (pinfunction "DI_DI") (pintype "input"))
    )
    (net (code "59") (name "Net-(LED21-PadDO)") (class "Default")
      (node (ref "LED21") (pin "DO") (pinfunction "DO_DO") (pintype "output"))
      (node (ref "LED22") (pin "DI") (pinfunction "DI_DI") (pintype "input"))
    )
    (net (code "60") (name "Net-(LED22-PadDO)") (class "Default")
      (node (ref "LED22") (pin "DO") (pinfunction "DO_DO") (pintype "output"))
      (node (ref "LED23") (pin "DI") (pinfunction "DI_DI") (pintype "input"))
    )
    (net (code "61") (name "Net-(LED23-PadDO)") (class "Default")
      (node (ref "LED23") (pin "DO") (pinfunction "DO_DO") (pintype "output"))
      (node (ref "LED24") (pin "DI") (pinfunction "DI_DI") (pintype "input"))
    )
    (net (code "62") (name "Net-(LED24-PadDO)") (class "Default")
      (node (ref "LED24") (pin "DO") (pinfunction "DO_DO") (pintype "output"))
      (node (ref "LED25") (pin "DI") (pinfunction "DI_DI") (pintype "input"))
    )
    (net (code "63") (name "Net-(LED25-PadDO)") (class "Default")
      (node (ref "LED25") (pin "DO") (pinfunction "DO_DO") (pintype "output"))
      (node (ref "LED26") (pin "DI") (pinfunction "DI_DI") (pintype "input"))
    )
    (net (code "64") (name "Net-(LED26-PadDO)") (class "Default")
      (node (ref "LED26") (pin "DO") (pinfunction "DO_DO") (pintype "output"))
      (node (ref "LED27") (pin "DI") (pinfunction "DI_DI") (pintype "input"))
    )
    (net (code "65") (name "Net-(LED27-PadDO)") (class "Default")
      (node (ref "LED27") (pin "DO") (pinfunction "DO_DO") (pintype "output"))
      (node (ref "LED28") (pin "DI") (pinfunction "DI_DI") (pintype "input"))
    )
    (net (code "66") (name "Net-(LED28-PadDO)") (class "Default")
      (node (ref "LED28") (pin "DO") (pinfunction "DO_DO") (pintype "output"))
      (node (ref "LED29") (pin "DI") (pinfunction "DI_DI") (pintype "input"))
    )
    (net (code "67") (name "Net-(LED29-PadDO)") (class "Default")
      (node (ref "LED29") (pin "DO") (pinfunction "DO_DO") (pintype "output"))
      (node (ref "LED30") (pin "DI") (pinfunction "DI_DI") (pintype "input"))
    )
    (net (code "68") (name "Net-(LED30-PadDO)") (class "Default")
      (node (ref "LED30") (pin "DO") (pinfunction "DO_DO") (pintype "output"))
      (node (ref "LED31") (pin "DI") (pinfunction "DI_DI") (pintype "input"))
    )
    (net (code "69") (name "Net-(LED31-PadDO)") (class "Default")
      (node (ref "LED31") (pin "DO") (pinfunction "DO_DO") (pintype "output"))
      (node (ref "LED32") (pin "DI") (pinfunction "DI_DI") (pintype "input"))
    )
    (net (code "70") (name "Net-(LED32-PadDO)") (class "Default")
      (node (ref "LED32") (pin "DO") (pinfunction "DO_DO") (pintype "output"))
      (node (ref "LED33") (pin "DI") (pinfunction "DI_DI") (pintype "input"))
    )
    (net (code "71") (name "Net-(LED33-PadDO)") (class "Default")
      (node (ref "LED33") (pin "DO") (pinfunction "DO_DO") (pintype "output"))
      (node (ref "LED34") (pin "DI") (pinfunction "DI_DI") (pintype "input"))
    )
    (net (code "72") (name "Net-(LED34-PadDO)") (class "Default")
      (node (ref "LED34") (pin "DO") (pinfunction "DO_DO") (pintype "output"))
      (node (ref "LED35") (pin "DI") (pinfunction "DI_DI") (pintype "input"))
    )
    (net (code "73") (name "Net-(LED35-PadDO)") (class "Default")
      (node (ref "LED35") (pin "DO") (pinfunction "DO_DO") (pintype "output"))
      (node (ref "LED36") (pin "DI") (pinfunction "DI_DI") (pintype "input"))
    )
    (net (code "74") (name "Net-(LED36-PadDO)") (class "Default")
      (node (ref "LED36") (pin "DO") (pinfunction "DO_DO") (pintype "output"))
      (node (ref "LED37") (pin "DI") (pinfunction "DI_DI") (pintype "input"))
    )
    (net (code "75") (name "Net-(LED37-PadDO)") (class "Default")
      (node (ref "LED37") (pin "DO") (pinfunction "DO_DO") (pintype "output"))
      (node (ref "LED38") (pin "DI") (pinfunction "DI_DI") (pintype "input"))
    )
    (net (code "76") (name "Net-(LED38-PadDO)") (class "Default")
      (node (ref "LED38") (pin "DO") (pinfunction "DO_DO") (pintype "output"))
      (node (ref "LED39") (pin "DI") (pinfunction "DI_DI") (pintype "input"))
    )
    (net (code "77") (name "Net-(LED39-PadDO)") (class "Default")
      (node (ref "LED39") (pin "DO") (pinfunction "DO_DO") (pintype "output"))
      (node (ref "LED40") (pin "DI") (pinfunction "DI_DI") (pintype "input"))
    )
    (net (code "78") (name "Net-(LED40-PadDO)") (class "Default")
      (node (ref "LED40") (pin "DO") (pinfunction "DO_DO") (pintype "output"))
      (node (ref "LED41") (pin "DI") (pinfunction "DI_DI") (pintype "input"))
    )
    (net (code "79") (name "Net-(LED41-PadDO)") (class "Default")
      (node (ref "LED41") (pin "DO") (pinfunction "DO_DO") (pintype "output"))
      (node (ref "LED42") (pin "DI") (pinfunction "DI_DI") (pintype "input"))
    )
    (net (code "80") (name "Net-(LED42-PadDO)") (class "Default")
      (node (ref "LED42") (pin "DO") (pinfunction "DO_DO") (pintype "output"))
      (node (ref "LED43") (pin "DI") (pinfunction "DI_DI") (pintype "input"))
    )
    (net (code "81") (name "Net-(LED43-PadDO)") (class "Default")
      (node (ref "LED43") (pin "DO") (pinfunction "DO_DO") (pintype "output"))
      (node (ref "LED44") (pin "DI") (pinfunction "DI_DI") (pintype "input"))
    )
    (net (code "82") (name "Net-(LED44-PadDO)") (class "Default")
      (node (ref "LED44") (pin "DO") (pinfunction "DO_DO") (pintype "output"))
      (node (ref "LED45") (pin "DI") (pinfunction "DI_DI") (pintype "input"))
    )
    (net (code "83") (name "Net-(LED45-PadDO)") (class "Default")
      (node (ref "LED45") (pin "DO") (pinfunction "DO_DO") (pintype "output"))
      (node (ref "LED46") (pin "DI") (pinfunction "DI_DI") (pintype "input"))
    )
    (net (code "84") (name "Net-(LED46-PadDO)") (class "Default")
      (node (ref "LED46") (pin "DO") (pinfunction "DO_DO") (pintype "output"))
      (node (ref "LED47") (pin "DI") (pinfunction "DI_DI") (pintype "input"))
    )
    (net (code "85") (name "Net-(LED47-PadDO)") (class "Default")
      (node (ref "LED47") (pin "DO") (pinfunction "DO_DO") (pintype "output"))
      (node (ref "LED48") (pin "DI") (pinfunction "DI_DI") (pintype "input"))
    )
    (net (code "86") (name "Net-(LED48-PadDO)") (class "Default")
      (node (ref "LED48") (pin "DO") (pinfunction "DO_DO") (pintype "output"))
      (node (ref "LED49") (pin "DI") (pinfunction "DI_DI") (pintype "input"))
    )
    (net (code "87") (name "Net-(LED49-PadDO)") (class "Default")
      (node (ref "LED49") (pin "DO") (pinfunction "DO_DO") (pintype "output"))
      (node (ref "LED50") (pin "DI") (pinfunction "DI_DI") (pintype "input"))
    )
    (net (code "88") (name "Net-(LED50-PadDO)") (class "Default")
      (node (ref "LED50") (pin "DO") (pinfunction "DO_DO") (pintype "output"))
      (node (ref "LED51") (pin "DI") (pinfunction "DI_DI") (pintype "input"))
    )
    (net (code "89") (name "Net-(LED51-PadDO)") (class "Default")
      (node (ref "LED51") (pin "DO") (pinfunction "DO_DO") (pintype "output"))
      (node (ref "LED52") (pin "DI") (pinfunction "DI_DI") (pintype "input"))
    )
    (net (code "90") (name "Net-(LED52-PadDO)") (class "Default")
      (node (ref "LED52") (pin "DO") (pinfunction "DO_DO") (pintype "output"))
      (node (ref "LED53") (pin "DI") (pinfunction "DI_DI") (pintype "input"))
    )
    (net (code "91") (name "Net-(LED53-PadDO)") (class "Default")
      (node (ref "LED53") (pin "DO") (pinfunction "DO_DO") (pintype "output"))
      (node (ref "LED54") (pin "DI") (pinfunction "DI_DI") (pintype "input"))
    )
    (net (code "92") (name "Net-(LED54-PadDO)") (class "Default")
      (node (ref "LED54") (pin "DO") (pinfunction "DO_DO") (pintype "output"))
      (node (ref "LED55") (pin "DI") (pinfunction "DI_DI") (pintype "input"))
    )
    (net (code "93") (name "Net-(LED55-PadDO)") (class "Default")
      (node (ref "LED55") (pin "DO") (pinfunction "DO_DO") (pintype "output"))
      (node (ref "LED56") (pin "DI") (pinfunction "DI_DI") (pintype "input"))
    )
    (net (code "94") (name "Net-(LED56-PadDO)") (class "Default")
      (node (ref "LED56") (pin "DO") (pinfunction "DO_DO") (pintype "output"))
      (node (ref "LED57") (pin "DI") (pinfunction "DI_DI") (pintype "input"))
    )
    (net (code "95") (name "Net-(LED57-PadDO)") (class "Default")
      (node (ref "LED57") (pin "DO") (pinfunction "DO_DO") (pintype "output"))
      (node (ref "LED58") (pin "DI") (pinfunction "DI_DI") (pintype "input"))
    )
    (net (code "96") (name "Net-(LED58-PadDO)") (class "Default")
      (node (ref "LED58") (pin "DO") (pinfunction "DO_DO") (pintype "output"))
      (node (ref "LED59") (pin "DI") (pinfunction "DI_DI") (pintype "input"))
    )
    (net (code "97") (name "Net-(LED59-PadDO)") (class "Default")
      (node (ref "LED59") (pin "DO") (pinfunction "DO_DO") (pintype "output"))
      (node (ref "LED60") (pin "DI") (pinfunction "DI_DI") (pintype "input"))
    )
    (net (code "98") (name "Net-(LED60-PadDO)") (class "Default")
      (node (ref "LED60") (pin "DO") (pinfunction "DO_DO") (pintype "output"))
      (node (ref "LED61") (pin "DI") (pinfunction "DI_DI") (pintype "input"))
    )
    (net (code "99") (name "Net-(LED61-PadDO)") (class "Default")
      (node (ref "LED61") (pin "DO") (pinfunction "DO_DO") (pintype "output"))
      (node (ref "LED62") (pin "DI") (pinfunction "DI_DI") (pintype "input"))
    )
    (net (code "100") (name "Net-(LED62-PadDO)") (class "Default")
      (node (ref "LED62") (pin "DO") (pinfunction "DO_DO") (pintype "output"))
      (node (ref "LED63") (pin "DI") (pinfunction "DI_DI") (pintype "input"))
    )
    (net (code "101") (name "Net-(LED63-PadDO)") (class "Default")
      (node (ref "LED63") (pin "DO") (pinfunction "DO_DO") (pintype "output"))
      (node (ref "LED64") (pin "DI") (pinfunction "DI_DI") (pintype "input"))
    )
    (net (code "102") (name "Net-(LED64-PadDO)") (class "Default")
      (node (ref "LED64") (pin "DO") (pinfunction "DO_DO") (pintype "output"))
      (node (ref "LED65") (pin "DI") (pinfunction "DI_DI") (pintype "input"))
    )
    (net (code "103") (name "Net-(LED65-PadDO)") (class "Default")
      (node (ref "LED65") (pin "DO") (pinfunction "DO_DO") (pintype "output"))
      (node (ref "LED66") (pin "DI") (pinfunction "DI_DI") (pintype "input"))
    )
    (net (code "104") (name "Net-(LED66-PadDO)") (class "Default")
      (node (ref "LED66") (pin "DO") (pinfunction "DO_DO") (pintype "output"))
      (node (ref "LED67") (pin "DI") (pinfunction "DI_DI") (pintype "input"))
    )
    (net (code "105") (name "Net-(LED67-PadDO)") (class "Default")
      (node (ref "LED67") (pin "DO") (pinfunction "DO_DO") (pintype "output"))
      (node (ref "LED68") (pin "DI") (pinfunction "DI_DI") (pintype "input"))
    )
    (net (code "106") (name "Net-(LED68-PadDO)") (class "Default")
      (node (ref "LED68") (pin "DO") (pinfunction "DO_DO") (pintype "output"))
      (node (ref "LED69") (pin "DI") (pinfunction "DI_DI") (pintype "input"))
    )
    (net (code "107") (name "Net-(LED69-PadDO)") (class "Default")
      (node (ref "LED69") (pin "DO") (pinfunction "DO_DO") (pintype "output"))
      (node (ref "LED70") (pin "DI") (pinfunction "DI_DI") (pintype "input"))
    )
    (net (code "108") (name "Net-(LED70-PadDO)") (class "Default")
      (node (ref "LED70") (pin "DO") (pinfunction "DO_DO") (pintype "output"))
      (node (ref "LED71") (pin "DI") (pinfunction "DI_DI") (pintype "input"))
    )
    (net (code "109") (name "Net-(LED71-PadDO)") (class "Default")
      (node (ref "LED71") (pin "DO") (pinfunction "DO_DO") (pintype "output"))
      (node (ref "LED72") (pin "DI") (pinfunction "DI_DI") (pintype "input"))
    )
    (net (code "110") (name "Net-(LED73-PadDO)") (class "Default")
      (node (ref "LED73") (pin "DO") (pinfunction "DO_DO") (pintype "output"))
      (node (ref "LED74") (pin "DI") (pinfunction "DI_DI") (pintype "input"))
    )
    (net (code "111") (name "Net-(LED74-PadDO)") (class "Default")
      (node (ref "LED74") (pin "DO") (pinfunction "DO_DO") (pintype "output"))
      (node (ref "LED75") (pin "DI") (pinfunction "DI_DI") (pintype "input"))
    )
    (net (code "112") (name "Net-(LED75-PadDO)") (class "Default")
      (node (ref "LED75") (pin "DO") (pinfunction "DO_DO") (pintype "output"))
      (node (ref "LED76") (pin "DI") (pinfunction "DI_DI") (pintype "input"))
    )
    (net (code "113") (name "Net-(LED76-PadDO)") (class "Default")
      (node (ref "LED76") (pin "DO") (pinfunction "DO_DO") (pintype "output"))
      (node (ref "LED77") (pin "DI") (pinfunction "DI_DI") (pintype "input"))
    )
    (net (code "114") (name "Net-(LED77-PadDO)") (class "Default")
      (node (ref "LED77") (pin "DO") (pinfunction "DO_DO") (pintype "output"))
      (node (ref "LED78") (pin "DI") (pinfunction "DI_DI") (pintype "input"))
    )
    (net (code "115") (name "Net-(LED78-PadDO)") (class "Default")
      (node (ref "LED78") (pin "DO") (pinfunction "DO_DO") (pintype "output"))
      (node (ref "LED79") (pin "DI") (pinfunction "DI_DI") (pintype "input"))
    )
    (net (code "116") (name "Net-(LED79-PadDO)") (class "Default")
      (node (ref "LED79") (pin "DO") (pinfunction "DO_DO") (pintype "output"))
      (node (ref "LED80") (pin "DI") (pinfunction "DI_DI") (pintype "input"))
    )
    (net (code "117") (name "Net-(LED80-PadDO)") (class "Default")
      (node (ref "LED80") (pin "DO") (pinfunction "DO_DO") (pintype "output"))
      (node (ref "LED81") (pin "DI") (pinfunction "DI_DI") (pintype "input"))
    )
    (net (code "118") (name "Net-(LED81-PadDO)") (class "Default")
      (node (ref "LED81") (pin "DO") (pinfunction "DO_DO") (pintype "output"))
      (node (ref "LED82") (pin "DI") (pinfunction "DI_DI") (pintype "input"))
    )
    (net (code "119") (name "Net-(LED82-PadDO)") (class "Default")
      (node (ref "LED82") (pin "DO") (pinfunction "DO_DO") (pintype "output"))
      (node (ref "LED83") (pin "DI") (pinfunction "DI_DI") (pintype "input"))
    )
    (net (code "120") (name "Net-(LED83-PadDO)") (class "Default")
      (node (ref "LED83") (pin "DO") (pinfunction "DO_DO") (pintype "output"))
      (node (ref "LED84") (pin "DI") (pinfunction "DI_DI") (pintype "input"))
    )
    (net (code "121") (name "Net-(LED84-PadDO)") (class "Default")
      (node (ref "LED84") (pin "DO") (pinfunction "DO_DO") (pintype "output"))
      (node (ref "LED85") (pin "DI") (pinfunction "DI_DI") (pintype "input"))
    )
    (net (code "122") (name "Net-(LED85-PadDO)") (class "Default")
      (node (ref "LED85") (pin "DO") (pinfunction "DO_DO") (pintype "output"))
      (node (ref "LED86") (pin "DI") (pinfunction "DI_DI") (pintype "input"))
    )
    (net (code "123") (name "Net-(LED86-PadDO)") (class "Default")
      (node (ref "LED86") (pin "DO") (pinfunction "DO_DO") (pintype "output"))
      (node (ref "LED87") (pin "DI") (pinfunction "DI_DI") (pintype "input"))
    )
    (net (code "124") (name "Net-(LED87-PadDO)") (class "Default")
      (node (ref "LED87") (pin "DO") (pinfunction "DO_DO") (pintype "output"))
      (node (ref "LED88") (pin "DI") (pinfunction "DI_DI") (pintype "input"))
    )
    (net (code "125") (name "Net-(LED88-PadDO)") (class "Default")
      (node (ref "LED88") (pin "DO") (pinfunction "DO_DO") (pintype "output"))
      (node (ref "LED89") (pin "DI") (pinfunction "DI_DI") (pintype "input"))
    )
    (net (code "126") (name "Net-(LED89-PadDO)") (class "Default")
      (node (ref "LED89") (pin "DO") (pinfunction "DO_DO") (pintype "output"))
      (node (ref "LED90") (pin "DI") (pinfunction "DI_DI") (pintype "input"))
    )
    (net (code "127") (name "Net-(LED90-PadDO)") (class "Default")
      (node (ref "LED90") (pin "DO") (pinfunction "DO_DO") (pintype "output"))
      (node (ref "LED91") (pin "DI") (pinfunction "DI_DI") (pintype "input"))
    )
    (net (code "128") (name "Net-(LED91-PadDO)") (class "Default")
      (node (ref "LED91") (pin "DO") (pinfunction "DO_DO") (pintype "output"))
      (node (ref "LED92") (pin "DI") (pinfunction "DI_DI") (pintype "input"))
    )
    (net (code "129") (name "Net-(LED92-PadDO)") (class "Default")
      (node (ref "LED92") (pin "DO") (pinfunction "DO_DO") (pintype "output"))
      (node (ref "LED93") (pin "DI") (pinfunction "DI_DI") (pintype "input"))
    )
    (net (code "130") (name "Net-(LED93-PadDO)") (class "Default")
      (node (ref "LED93") (pin "DO") (pinfunction "DO_DO") (pintype "output"))
      (node (ref "LED94") (pin "DI") (pinfunction "DI_DI") (pintype "input"))
    )
    (net (code "131") (name "Net-(LED94-PadDO)") (class "Default")
      (node (ref "LED94") (pin "DO") (pinfunction "DO_DO") (pintype "output"))
      (node (ref "LED95") (pin "DI") (pinfunction "DI_DI") (pintype "input"))
    )
    (net (code "132") (name "Net-(LED95-PadDO)") (class "Default")
      (node (ref "LED95") (pin "DO") (pinfunction "DO_DO") (pintype "output"))
      (node (ref "LED96") (pin "DI") (pinfunction "DI_DI") (pintype "input"))
    )
    (net (code "133") (name "Net-(LED96-PadDO)") (class "Default")
      (node (ref "LED96") (pin "DO") (pinfunction "DO_DO") (pintype "output"))
      (node (ref "LED97") (pin "DI") (pinfunction "DI_DI") (pintype "input"))
    )
    (net (code "134") (name "Net-(LED97-PadDO)") (class "Default")
      (node (ref "LED97") (pin "DO") (pinfunction "DO_DO") (pintype "output"))
      (node (ref "LED98") (pin "DI") (pinfunction "DI_DI") (pintype "input"))
    )
    (net (code "135") (name "Net-(LED98-PadDO)") (class "Default")
      (node (ref "LED98") (pin "DO") (pinfunction "DO_DO") (pintype "output"))
      (node (ref "LED99") (pin "DI") (pinfunction "DI_DI") (pintype "input"))
    )
    (net (code "136") (name "Net-(LED100-PadDI)") (class "Default")
      (node (ref "LED100") (pin "DI") (pinfunction "DI_DI") (pintype "input"))
      (node (ref "LED99") (pin "DO") (pinfunction "DO_DO") (pintype "output"))
    )
    (net (code "137") (name "Net-(LED100-PadDO)") (class "Default")
      (node (ref "LED100") (pin "DO") (pinfunction "DO_DO") (pintype "output"))
      (node (ref "LED101") (pin "DI") (pinfunction "DI_DI") (pintype "input"))
    )
    (net (code "138") (name "Net-(LED101-PadDO)") (class "Default")
      (node (ref "LED101") (pin "DO") (pinfunction "DO_DO") (pintype "output"))
      (node (ref "LED102") (pin "DI") (pinfunction "DI_DI") (pintype "input"))
    )
    (net (code "139") (name "Net-(LED102-PadDO)") (class "Default")
      (node (ref "LED102") (pin "DO") (pinfunction "DO_DO") (pintype "output"))
      (node (ref "LED103") (pin "DI") (pinfunction "DI_DI") (pintype "input"))
    )
    (net (code "140") (name "Net-(LED103-PadDO)") (class "Default")
      (node (ref "LED103") (pin "DO") (pinfunction "DO_DO") (pintype "output"))
      (node (ref "LED104") (pin "DI") (pinfunction "DI_DI") (pintype "input"))
    )
    (net (code "141") (name "Net-(LED104-PadDO)") (class "Default")
      (node (ref "LED104") (pin "DO") (pinfunction "DO_DO") (pintype "output"))
      (node (ref "LED105") (pin "DI") (pinfunction "DI_DI") (pintype "input"))
    )
    (net (code "142") (name "Net-(LED105-PadDO)") (class "Default")
      (node (ref "LED105") (pin "DO") (pinfunction "DO_DO") (pintype "output"))
      (node (ref "LED106") (pin "DI") (pinfunction "DI_DI") (pintype "input"))
    )
    (net (code "143") (name "Net-(LED106-PadDO)") (class "Default")
      (node (ref "LED106") (pin "DO") (pinfunction "DO_DO") (pintype "output"))
      (node (ref "LED107") (pin "DI") (pinfunction "DI_DI") (pintype "input"))
    )
    (net (code "144") (name "Net-(LED107-PadDO)") (class "Default")
      (node (ref "LED107") (pin "DO") (pinfunction "DO_DO") (pintype "output"))
      (node (ref "LED108") (pin "DI") (pinfunction "DI_DI") (pintype "input"))
    )
    (net (code "145") (name "Net-(LED108-PadDO)") (class "Default")
      (node (ref "LED108") (pin "DO") (pinfunction "DO_DO") (pintype "output"))
      (node (ref "LED109") (pin "DI") (pinfunction "DI_DI") (pintype "input"))
    )
    (net (code "146") (name "Net-(LED109-PadDO)") (class "Default")
      (node (ref "LED109") (pin "DO") (pinfunction "DO_DO") (pintype "output"))
      (node (ref "LED110") (pin "DI") (pinfunction "DI_DI") (pintype "input"))
    )
    (net (code "147") (name "Net-(LED110-PadDO)") (class "Default")
      (node (ref "LED110") (pin "DO") (pinfunction "DO_DO") (pintype "output"))
      (node (ref "LED111") (pin "DI") (pinfunction "DI_DI") (pintype "input"))
    )
    (net (code "148") (name "Net-(LED111-PadDO)") (class "Default")
      (node (ref "LED111") (pin "DO") (pinfunction "DO_DO") (pintype "output"))
      (node (ref "LED112") (pin "DI") (pinfunction "DI_DI") (pintype "input"))
    )
    (net (code "149") (name "Net-(LED112-PadDO)") (class "Default")
      (node (ref "LED112") (pin "DO") (pinfunction "DO_DO") (pintype "output"))
      (node (ref "LED113") (pin "DI") (pinfunction "DI_DI") (pintype "input"))
    )
    (net (code "150") (name "Net-(LED113-PadDO)") (class "Default")
      (node (ref "LED113") (pin "DO") (pinfunction "DO_DO") (pintype "output"))
      (node (ref "LED114") (pin "DI") (pinfunction "DI_DI") (pintype "input"))
    )
    (net (code "151") (name "Net-(LED114-PadDO)") (class "Default")
      (node (ref "LED114") (pin "DO") (pinfunction "DO_DO") (pintype "output"))
      (node (ref "LED115") (pin "DI") (pinfunction "DI_DI") (pintype "input"))
    )
    (net (code "152") (name "Net-(LED115-PadDO)") (class "Default")
      (node (ref "LED115") (pin "DO") (pinfunction "DO_DO") (pintype "output"))
      (node (ref "LED116") (pin "DI") (pinfunction "DI_DI") (pintype "input"))
    )
    (net (code "153") (name "Net-(LED116-PadDO)") (class "Default")
      (node (ref "LED116") (pin "DO") (pinfunction "DO_DO") (pintype "output"))
      (node (ref "LED117") (pin "DI") (pinfunction "DI_DI") (pintype "input"))
    )
    (net (code "154") (name "Net-(LED117-PadDO)") (class "Default")
      (node (ref "LED117") (pin "DO") (pinfunction "DO_DO") (pintype "output"))
      (node (ref "LED118") (pin "DI") (pinfunction "DI_DI") (pintype "input"))
    )
    (net (code "155") (name "Net-(LED118-PadDO)") (class "Default")
      (node (ref "LED118") (pin "DO") (pinfunction "DO_DO") (pintype "output"))
      (node (ref "LED119") (pin "DI") (pinfunction "DI_DI") (pintype "input"))
    )
    (net (code "156") (name "Net-(LED119-PadDO)") (class "Default")
      (node (ref "LED119") (pin "DO") (pinfunction "DO_DO") (pintype "output"))
      (node (ref "LED120") (pin "DI") (pinfunction "DI_DI") (pintype "input"))
    )
    (net (code "157") (name "Net-(LED120-PadDO)") (class "Default")
      (node (ref "LED120") (pin "DO") (pinfunction "DO_DO") (pintype "output"))
      (node (ref "LED121") (pin "DI") (pinfunction "DI_DI") (pintype "input"))
    )
    (net (code "158") (name "Net-(LED121-PadDO)") (class "Default")
      (node (ref "LED121") (pin "DO") (pinfunction "DO_DO") (pintype "output"))
      (node (ref "LED122") (pin "DI") (pinfunction "DI_DI") (pintype "input"))
    )
    (net (code "159") (name "Net-(LED122-PadDO)") (class "Default")
      (node (ref "LED122") (pin "DO") (pinfunction "DO_DO") (pintype "output"))
      (node (ref "LED123") (pin "DI") (pinfunction "DI_DI") (pintype "input"))
    )
    (net (code "160") (name "Net-(LED123-PadDO)") (class "Default")
      (node (ref "LED123") (pin "DO") (pinfunction "DO_DO") (pintype "output"))
      (node (ref "LED124") (pin "DI") (pinfunction "DI_DI") (pintype "input"))
    )
    (net (code "161") (name "Net-(LED124-PadDO)") (class "Default")
      (node (ref "LED124") (pin "DO") (pinfunction "DO_DO") (pintype "output"))
      (node (ref "LED125") (pin "DI") (pinfunction "DI_DI") (pintype "input"))
    )
    (net (code "162") (name "Net-(LED125-PadDO)") (class "Default")
      (node (ref "LED125") (pin "DO") (pinfunction "DO_DO") (pintype "output"))
      (node (ref "LED126") (pin "DI") (pinfunction "DI_DI") (pintype "input"))
    )
    (net (code "163") (name "Net-(LED126-PadDO)") (class "Default")
      (node (ref "LED126") (pin "DO") (pinfunction "DO_DO") (pintype "output"))
      (node (ref "LED127") (pin "DI") (pinfunction "DI_DI") (pintype "input"))
    )
    (net (code "164") (name "Net-(LED127-PadDO)") (class "Default")
      (node (ref "LED127") (pin "DO") (pinfunction "DO_DO") (pintype "output"))
      (node (ref "LED128") (pin "DI") (pinfunction "DI_DI") (pintype "input"))
    )
    (net (code "165") (name "Net-(LED128-PadDO)") (class "Default")
      (node (ref "LED128") (pin "DO") (pinfunction "DO_DO") (pintype "output"))
      (node (ref "LED129") (pin "DI") (pinfunction "DI_DI") (pintype "input"))
    )
    (net (code "166") (name "Net-(LED129-PadDO)") (class "Default")
      (node (ref "LED129") (pin "DO") (pinfunction "DO_DO") (pintype "output"))
      (node (ref "LED130") (pin "DI") (pinfunction "DI_DI") (pintype "input"))
    )
    (net (code "167") (name "Net-(LED130-PadDO)") (class "Default")
      (node (ref "LED130") (pin "DO") (pinfunction "DO_DO") (pintype "output"))
      (node (ref "LED131") (pin "DI") (pinfunction "DI_DI") (pintype "input"))
    )
    (net (code "168") (name "Net-(LED131-PadDO)") (class "Default")
      (node (ref "LED131") (pin "DO") (pinfunction "DO_DO") (pintype "output"))
      (node (ref "LED132") (pin "DI") (pinfunction "DI_DI") (pintype "input"))
    )
    (net (code "169") (name "Net-(LED132-PadDO)") (class "Default")
      (node (ref "LED132") (pin "DO") (pinfunction "DO_DO") (pintype "output"))
      (node (ref "LED133") (pin "DI") (pinfunction "DI_DI") (pintype "input"))
    )
    (net (code "170") (name "Net-(LED133-PadDO)") (class "Default")
      (node (ref "LED133") (pin "DO") (pinfunction "DO_DO") (pintype "output"))
      (node (ref "LED134") (pin "DI") (pinfunction "DI_DI") (pintype "input"))
    )
    (net (code "171") (name "Net-(LED134-PadDO)") (class "Default")
      (node (ref "LED134") (pin "DO") (pinfunction "DO_DO") (pintype "output"))
      (node (ref "LED135") (pin "DI") (pinfunction "DI_DI") (pintype "input"))
    )
    (net (code "172") (name "Net-(LED135-PadDO)") (class "Default")
      (node (ref "LED135") (pin "DO") (pinfunction "DO_DO") (pintype "output"))
      (node (ref "LED136") (pin "DI") (pinfunction "DI_DI") (pintype "input"))
    )
    (net (code "173") (name "Net-(LED136-PadDO)") (class "Default")
      (node (ref "LED136") (pin "DO") (pinfunction "DO_DO") (pintype "output"))
      (node (ref "LED137") (pin "DI") (pinfunction "DI_DI") (pintype "input"))
    )
    (net (code "174") (name "Net-(LED137-PadDO)") (class "Default")
      (node (ref "LED137") (pin "DO") (pinfunction "DO_DO") (pintype "output"))
      (node (ref "LED138") (pin "DI") (pinfunction "DI_DI") (pintype "input"))
    )
    (net (code "175") (name "Net-(LED138-PadDO)") (class "Default")
      (node (ref "LED138") (pin "DO") (pinfunction "DO_DO") (pintype "output"))
      (node (ref "LED139") (pin "DI") (pinfunction "DI_DI") (pintype "input"))
    )
    (net (code "176") (name "Net-(LED139-PadDO)") (class "Default")
      (node (ref "LED139") (pin "DO") (pinfunction "DO_DO") (pintype "output"))
      (node (ref "LED140") (pin "DI") (pinfunction "DI_DI") (pintype "input"))
    )
    (net (code "177") (name "Net-(LED140-PadDO)") (class "Default")
      (node (ref "LED140") (pin "DO") (pinfunction "DO_DO") (pintype "output"))
      (node (ref "LED141") (pin "DI") (pinfunction "DI_DI") (pintype "input"))
    )
    (net (code "178") (name "Net-(LED141-PadDO)") (class "Default")
      (node (ref "LED141") (pin "DO") (pinfunction "DO_DO") (pintype "output"))
      (node (ref "LED142") (pin "DI") (pinfunction "DI_DI") (pintype "input"))
    )
    (net (code "179") (name "Net-(LED142-PadDO)") (class "Default")
      (node (ref "LED142") (pin "DO") (pinfunction "DO_DO") (pintype "output"))
      (node (ref "LED143") (pin "DI") (pinfunction "DI_DI") (pintype "input"))
    )
    (net (code "180") (name "Net-(LED143-PadDO)") (class "Default")
      (node (ref "LED143") (pin "DO") (pinfunction "DO_DO") (pintype "output"))
      (node (ref "LED144") (pin "DI") (pinfunction "DI_DI") (pintype "input"))
    )
    (net (code "181") (name "Net-(LED145-PadDO)") (class "Default")
      (node (ref "LED145") (pin "DO") (pinfunction "DO_DO") (pintype "output"))
      (node (ref "LED146") (pin "DI") (pinfunction "DI_DI") (pintype "input"))
    )
    (net (code "182") (name "Net-(LED146-PadDO)") (class "Default")
      (node (ref "LED146") (pin "DO") (pinfunction "DO_DO") (pintype "output"))
      (node (ref "LED147") (pin "DI") (pinfunction "DI_DI") (pintype "input"))
    )
    (net (code "183") (name "Net-(LED147-PadDO)") (class "Default")
      (node (ref "LED147") (pin "DO") (pinfunction "DO_DO") (pintype "output"))
      (node (ref "LED148") (pin "DI") (pinfunction "DI_DI") (pintype "input"))
    )
    (net (code "184") (name "Net-(LED148-PadDO)") (class "Default")
      (node (ref "LED148") (pin "DO") (pinfunction "DO_DO") (pintype "output"))
      (node (ref "LED149") (pin "DI") (pinfunction "DI_DI") (pintype "input"))
    )
    (net (code "185") (name "Net-(LED149-PadDO)") (class "Default")
      (node (ref "LED149") (pin "DO") (pinfunction "DO_DO") (pintype "output"))
      (node (ref "LED150") (pin "DI") (pinfunction "DI_DI") (pintype "input"))
    )
    (net (code "186") (name "Net-(LED150-PadDO)") (class "Default")
      (node (ref "LED150") (pin "DO") (pinfunction "DO_DO") (pintype "output"))
      (node (ref "LED151") (pin "DI") (pinfunction "DI_DI") (pintype "input"))
    )
    (net (code "187") (name "Net-(LED151-PadDO)") (class "Default")
      (node (ref "LED151") (pin "DO") (pinfunction "DO_DO") (pintype "output"))
      (node (ref "LED152") (pin "DI") (pinfunction "DI_DI") (pintype "input"))
    )
    (net (code "188") (name "Net-(LED152-PadDO)") (class "Default")
      (node (ref "LED152") (pin "DO") (pinfunction "DO_DO") (pintype "output"))
      (node (ref "LED153") (pin "DI") (pinfunction "DI_DI") (pintype "input"))
    )
    (net (code "189") (name "Net-(LED153-PadDO)") (class "Default")
      (node (ref "LED153") (pin "DO") (pinfunction "DO_DO") (pintype "output"))
      (node (ref "LED154") (pin "DI") (pinfunction "DI_DI") (pintype "input"))
    )
    (net (code "190") (name "Net-(LED154-PadDO)") (class "Default")
      (node (ref "LED154") (pin "DO") (pinfunction "DO_DO") (pintype "output"))
      (node (ref "LED155") (pin "DI") (pinfunction "DI_DI") (pintype "input"))
    )
    (net (code "191") (name "Net-(LED155-PadDO)") (class "Default")
      (node (ref "LED155") (pin "DO") (pinfunction "DO_DO") (pintype "output"))
      (node (ref "LED156") (pin "DI") (pinfunction "DI_DI") (pintype "input"))
    )
    (net (code "192") (name "Net-(LED156-PadDO)") (class "Default")
      (node (ref "LED156") (pin "DO") (pinfunction "DO_DO") (pintype "output"))
      (node (ref "LED157") (pin "DI") (pinfunction "DI_DI") (pintype "input"))
    )
    (net (code "193") (name "Net-(LED157-PadDO)") (class "Default")
      (node (ref "LED157") (pin "DO") (pinfunction "DO_DO") (pintype "output"))
      (node (ref "LED158") (pin "DI") (pinfunction "DI_DI") (pintype "input"))
    )
    (net (code "194") (name "Net-(LED158-PadDO)") (class "Default")
      (node (ref "LED158") (pin "DO") (pinfunction "DO_DO") (pintype "output"))
      (node (ref "LED159") (pin "DI") (pinfunction "DI_DI") (pintype "input"))
    )
    (net (code "195") (name "Net-(LED159-PadDO)") (class "Default")
      (node (ref "LED159") (pin "DO") (pinfunction "DO_DO") (pintype "output"))
      (node (ref "LED160") (pin "DI") (pinfunction "DI_DI") (pintype "input"))
    )
    (net (code "196") (name "Net-(LED160-PadDO)") (class "Default")
      (node (ref "LED160") (pin "DO") (pinfunction "DO_DO") (pintype "output"))
      (node (ref "LED161") (pin "DI") (pinfunction "DI_DI") (pintype "input"))
    )
    (net (code "197") (name "Net-(LED161-PadDO)") (class "Default")
      (node (ref "LED161") (pin "DO") (pinfunction "DO_DO") (pintype "output"))
      (node (ref "LED162") (pin "DI") (pinfunction "DI_DI") (pintype "input"))
    )
    (net (code "198") (name "Net-(LED162-PadDO)") (class "Default")
      (node (ref "LED162") (pin "DO") (pinfunction "DO_DO") (pintype "output"))
      (node (ref "LED163") (pin "DI") (pinfunction "DI_DI") (pintype "input"))
    )
    (net (code "199") (name "Net-(LED163-PadDO)") (class "Default")
      (node (ref "LED163") (pin "DO") (pinfunction "DO_DO") (pintype "output"))
      (node (ref "LED164") (pin "DI") (pinfunction "DI_DI") (pintype "input"))
    )
    (net (code "200") (name "Net-(LED164-PadDO)") (class "Default")
      (node (ref "LED164") (pin "DO") (pinfunction "DO_DO") (pintype "output"))
      (node (ref "LED165") (pin "DI") (pinfunction "DI_DI") (pintype "input"))
    )
    (net (code "201") (name "Net-(LED165-PadDO)") (class "Default")
      (node (ref "LED165") (pin "DO") (pinfunction "DO_DO") (pintype "output"))
      (node (ref "LED166") (pin "DI") (pinfunction "DI_DI") (pintype "input"))
    )
    (net (code "202") (name "Net-(LED166-PadDO)") (class "Default")
      (node (ref "LED166") (pin "DO") (pinfunction "DO_DO") (pintype "output"))
      (node (ref "LED167") (pin "DI") (pinfunction "DI_DI") (pintype "input"))
    )
    (net (code "203") (name "Net-(LED167-PadDO)") (class "Default")
      (node (ref "LED167") (pin "DO") (pinfunction "DO_DO") (pintype "output"))
      (node (ref "LED168") (pin "DI") (pinfunction "DI_DI") (pintype "input"))
    )
    (net (code "204") (name "Net-(LED168-PadDO)") (class "Default")
      (node (ref "LED168") (pin "DO") (pinfunction "DO_DO") (pintype "output"))
      (node (ref "LED169") (pin "DI") (pinfunction "DI_DI") (pintype "input"))
    )
    (net (code "205") (name "Net-(LED169-PadDO)") (class "Default")
      (node (ref "LED169") (pin "DO") (pinfunction "DO_DO") (pintype "output"))
      (node (ref "LED170") (pin "DI") (pinfunction "DI_DI") (pintype "input"))
    )
    (net (code "206") (name "Net-(LED170-PadDO)") (class "Default")
      (node (ref "LED170") (pin "DO") (pinfunction "DO_DO") (pintype "output"))
      (node (ref "LED171") (pin "DI") (pinfunction "DI_DI") (pintype "input"))
    )
    (net (code "207") (name "Net-(LED171-PadDO)") (class "Default")
      (node (ref "LED171") (pin "DO") (pinfunction "DO_DO") (pintype "output"))
      (node (ref "LED172") (pin "DI") (pinfunction "DI_DI") (pintype "input"))
    )
    (net (code "208") (name "Net-(LED172-PadDO)") (class "Default")
      (node (ref "LED172") (pin "DO") (pinfunction "DO_DO") (pintype "output"))
      (node (ref "LED173") (pin "DI") (pinfunction "DI_DI") (pintype "input"))
    )
    (net (code "209") (name "Net-(LED173-PadDO)") (class "Default")
      (node (ref "LED173") (pin "DO") (pinfunction "DO_DO") (pintype "output"))
      (node (ref "LED174") (pin "DI") (pinfunction "DI_DI") (pintype "input"))
    )
    (net (code "210") (name "Net-(LED174-PadDO)") (class "Default")
      (node (ref "LED174") (pin "DO") (pinfunction "DO_DO") (pintype "output"))
      (node (ref "LED175") (pin "DI") (pinfunction "DI_DI") (pintype "input"))
    )
    (net (code "211") (name "Net-(LED175-PadDO)") (class "Default")
      (node (ref "LED175") (pin "DO") (pinfunction "DO_DO") (pintype "output"))
      (node (ref "LED176") (pin "DI") (pinfunction "DI_DI") (pintype "input"))
    )
    (net (code "212") (name "Net-(LED176-PadDO)") (class "Default")
      (node (ref "LED176") (pin "DO") (pinfunction "DO_DO") (pintype "output"))
      (node (ref "LED177") (pin "DI") (pinfunction "DI_DI") (pintype "input"))
    )
    (net (code "213") (name "Net-(LED177-PadDO)") (class "Default")
      (node (ref "LED177") (pin "DO") (pinfunction "DO_DO") (pintype "output"))
      (node (ref "LED178") (pin "DI") (pinfunction "DI_DI") (pintype "input"))
    )
    (net (code "214") (name "Net-(LED178-PadDO)") (class "Default")
      (node (ref "LED178") (pin "DO") (pinfunction "DO_DO") (pintype "output"))
      (node (ref "LED179") (pin "DI") (pinfunction "DI_DI") (pintype "input"))
    )
    (net (code "215") (name "Net-(LED179-PadDO)") (class "Default")
      (node (ref "LED179") (pin "DO") (pinfunction "DO_DO") (pintype "output"))
      (node (ref "LED180") (pin "DI") (pinfunction "DI_DI") (pintype "input"))
    )
    (net (code "216") (name "Net-(LED180-PadDO)") (class "Default")
      (node (ref "LED180") (pin "DO") (pinfunction "DO_DO") (pintype "output"))
      (node (ref "LED181") (pin "DI") (pinfunction "DI_DI") (pintype "input"))
    )
    (net (code "217") (name "Net-(LED181-PadDO)") (class "Default")
      (node (ref "LED181") (pin "DO") (pinfunction "DO_DO") (pintype "output"))
      (node (ref "LED182") (pin "DI") (pinfunction "DI_DI") (pintype "input"))
    )
    (net (code "218") (name "Net-(LED182-PadDO)") (class "Default")
      (node (ref "LED182") (pin "DO") (pinfunction "DO_DO") (pintype "output"))
      (node (ref "LED183") (pin "DI") (pinfunction "DI_DI") (pintype "input"))
    )
    (net (code "219") (name "Net-(LED183-PadDO)") (class "Default")
      (node (ref "LED183") (pin "DO") (pinfunction "DO_DO") (pintype "output"))
      (node (ref "LED184") (pin "DI") (pinfunction "DI_DI") (pintype "input"))
    )
    (net (code "220") (name "Net-(LED184-PadDO)") (class "Default")
      (node (ref "LED184") (pin "DO") (pinfunction "DO_DO") (pintype "output"))
      (node (ref "LED185") (pin "DI") (pinfunction "DI_DI") (pintype "input"))
    )
    (net (code "221") (name "Net-(LED185-PadDO)") (class "Default")
      (node (ref "LED185") (pin "DO") (pinfunction "DO_DO") (pintype "output"))
      (node (ref "LED186") (pin "DI") (pinfunction "DI_DI") (pintype "input"))
    )
    (net (code "222") (name "Net-(LED186-PadDO)") (class "Default")
      (node (ref "LED186") (pin "DO") (pinfunction "DO_DO") (pintype "output"))
      (node (ref "LED187") (pin "DI") (pinfunction "DI_DI") (pintype "input"))
    )
    (net (code "223") (name "Net-(LED187-PadDO)") (class "Default")
      (node (ref "LED187") (pin "DO") (pinfunction "DO_DO") (pintype "output"))
      (node (ref "LED188") (pin "DI") (pinfunction "DI_DI") (pintype "input"))
    )
    (net (code "224") (name "Net-(LED188-PadDO)") (class "Default")
      (node (ref "LED188") (pin "DO") (pinfunction "DO_DO") (pintype "output"))
      (node (ref "LED189") (pin "DI") (pinfunction "DI_DI") (pintype "input"))
    )
    (net (code "225") (name "Net-(LED189-PadDO)") (class "Default")
      (node (ref "LED189") (pin "DO") (pinfunction "DO_DO") (pintype "output"))
      (node (ref "LED190") (pin "DI") (pinfunction "DI_DI") (pintype "input"))
    )
    (net (code "226") (name "Net-(LED190-PadDO)") (class "Default")
      (node (ref "LED190") (pin "DO") (pinfunction "DO_DO") (pintype "output"))
      (node (ref "LED191") (pin "DI") (pinfunction "DI_DI") (pintype "input"))
    )
    (net (code "227") (name "Net-(LED191-PadDO)") (class "Default")
      (node (ref "LED191") (pin "DO") (pinfunction "DO_DO") (pintype "output"))
      (node (ref "LED192") (pin "DI") (pinfunction "DI_DI") (pintype "input"))
    )
    (net (code "228") (name "Net-(LED192-PadDO)") (class "Default")
      (node (ref "LED192") (pin "DO") (pinfunction "DO_DO") (pintype "output"))
      (node (ref "LED193") (pin "DI") (pinfunction "DI_DI") (pintype "input"))
    )
    (net (code "229") (name "Net-(LED193-PadDO)") (class "Default")
      (node (ref "LED193") (pin "DO") (pinfunction "DO_DO") (pintype "output"))
      (node (ref "LED194") (pin "DI") (pinfunction "DI_DI") (pintype "input"))
    )
    (net (code "230") (name "Net-(LED194-PadDO)") (class "Default")
      (node (ref "LED194") (pin "DO") (pinfunction "DO_DO") (pintype "output"))
      (node (ref "LED195") (pin "DI") (pinfunction "DI_DI") (pintype "input"))
    )
    (net (code "231") (name "Net-(LED195-PadDO)") (class "Default")
      (node (ref "LED195") (pin "DO") (pinfunction "DO_DO") (pintype "output"))
      (node (ref "LED196") (pin "DI") (pinfunction "DI_DI") (pintype "input"))
    )
    (net (code "232") (name "Net-(LED196-PadDO)") (class "Default")
      (node (ref "LED196") (pin "DO") (pinfunction "DO_DO") (pintype "output"))
      (node (ref "LED197") (pin "DI") (pinfunction "DI_DI") (pintype "input"))
    )
    (net (code "233") (name "Net-(LED197-PadDO)") (class "Default")
      (node (ref "LED197") (pin "DO") (pinfunction "DO_DO") (pintype "output"))
      (node (ref "LED198") (pin "DI") (pinfunction "DI_DI") (pintype "input"))
    )
    (net (code "234") (name "Net-(LED198-PadDO)") (class "Default")
      (node (ref "LED198") (pin "DO") (pinfunction "DO_DO") (pintype "output"))
      (node (ref "LED199") (pin "DI") (pinfunction "DI_DI") (pintype "input"))
    )
    (net (code "235") (name "Net-(LED199-PadDO)") (class "Default")
      (node (ref "LED199") (pin "DO") (pinfunction "DO_DO") (pintype "output"))
      (node (ref "LED200") (pin "DI") (pinfunction "DI_DI") (pintype "input"))
    )
    (net (code "236") (name "Net-(LED200-PadDO)") (class "Default")
      (node (ref "LED200") (pin "DO") (pinfunction "DO_DO") (pintype "output"))
      (node (ref "LED201") (pin "DI") (pinfunction "DI_DI") (pintype "input"))
    )
    (net (code "237") (name "Net-(LED201-PadDO)") (class "Default")
      (node (ref "LED201") (pin "DO") (pinfunction "DO_DO") (pintype "output"))
      (node (ref "LED202") (pin "DI") (pinfunction "DI_DI") (pintype "input"))
    )
    (net (code "238") (name "Net-(LED202-PadDO)") (class "Default")
      (node (ref "LED202") (pin "DO") (pinfunction "DO_DO") (pintype "output"))
      (node (ref "LED203") (pin "DI") (pinfunction "DI_DI") (pintype "input"))
    )
    (net (code "239") (name "Net-(LED203-PadDO)") (class "Default")
      (node (ref "LED203") (pin "DO") (pinfunction "DO_DO") (pintype "output"))
      (node (ref "LED204") (pin "DI") (pinfunction "DI_DI") (pintype "input"))
    )
    (net (code "240") (name "Net-(LED204-PadDO)") (class "Default")
      (node (ref "LED204") (pin "DO") (pinfunction "DO_DO") (pintype "output"))
      (node (ref "LED205") (pin "DI") (pinfunction "DI_DI") (pintype "input"))
    )
    (net (code "241") (name "Net-(LED205-PadDO)") (class "Default")
      (node (ref "LED205") (pin "DO") (pinfunction "DO_DO") (pintype "output"))
      (node (ref "LED206") (pin "DI") (pinfunction "DI_DI") (pintype "input"))
    )
    (net (code "242") (name "Net-(LED206-PadDO)") (class "Default")
      (node (ref "LED206") (pin "DO") (pinfunction "DO_DO") (pintype "output"))
      (node (ref "LED207") (pin "DI") (pinfunction "DI_DI") (pintype "input"))
    )
    (net (code "243") (name "Net-(LED207-PadDO)") (class "Default")
      (node (ref "LED207") (pin "DO") (pinfunction "DO_DO") (pintype "output"))
      (node (ref "LED208") (pin "DI") (pinfunction "DI_DI") (pintype "input"))
    )
    (net (code "244") (name "Net-(LED208-PadDO)") (class "Default")
      (node (ref "LED208") (pin "DO") (pinfunction "DO_DO") (pintype "output"))
      (node (ref "LED209") (pin "DI") (pinfunction "DI_DI") (pintype "input"))
    )
    (net (code "245") (name "Net-(LED209-PadDO)") (class "Default")
      (node (ref "LED209") (pin "DO") (pinfunction "DO_DO") (pintype "output"))
      (node (ref "LED210") (pin "DI") (pinfunction "DI_DI") (pintype "input"))
    )
    (net (code "246") (name "Net-(LED210-PadDO)") (class "Default")
      (node (ref "LED210") (pin "DO") (pinfunction "DO_DO") (pintype "output"))
      (node (ref "LED211") (pin "DI") (pinfunction "DI_DI") (pintype "input"))
    )
    (net (code "247") (name "Net-(LED211-PadDO)") (class "Default")
      (node (ref "LED211") (pin "DO") (pinfunction "DO_DO") (pintype "output"))
      (node (ref "LED212") (pin "DI") (pinfunction "DI_DI") (pintype "input"))
    )
    (net (code "248") (name "Net-(LED212-PadDO)") (class "Default")
      (node (ref "LED212") (pin "DO") (pinfunction "DO_DO") (pintype "output"))
      (node (ref "LED213") (pin "DI") (pinfunction "DI_DI") (pintype "input"))
    )
    (net (code "249") (name "Net-(LED213-PadDO)") (class "Default")
      (node (ref "LED213") (pin "DO") (pinfunction "DO_DO") (pintype "output"))
      (node (ref "LED214") (pin "DI") (pinfunction "DI_DI") (pintype "input"))
    )
    (net (code "250") (name "Net-(LED214-PadDO)") (class "Default")
      (node (ref "LED214") (pin "DO") (pinfunction "DO_DO") (pintype "output"))
      (node (ref "LED215") (pin "DI") (pinfunction "DI_DI") (pintype "input"))
    )
    (net (code "251") (name "Net-(LED215-PadDO)") (class "Default")
      (node (ref "LED215") (pin "DO") (pinfunction "DO_DO") (pintype "output"))
      (node (ref "LED216") (pin "DI") (pinfunction "DI_DI") (pintype "input"))
    )
    (net (code "252") (name "Net-(LED217-PadDO)") (class "Default")
      (node (ref "LED217") (pin "DO") (pinfunction "DO_DO") (pintype "output"))
      (node (ref "LED218") (pin "DI") (pinfunction "DI_DI") (pintype "input"))
    )
    (net (code "253") (name "Net-(LED218-PadDO)") (class "Default")
      (node (ref "LED218") (pin "DO") (pinfunction "DO_DO") (pintype "output"))
      (node (ref "LED219") (pin "DI") (pinfunction "DI_DI") (pintype "input"))
    )
    (net (code "254") (name "Net-(LED219-PadDO)") (class "Default")
      (node (ref "LED219") (pin "DO") (pinfunction "DO_DO") (pintype "output"))
      (node (ref "LED220") (pin "DI") (pinfunction "DI_DI") (pintype "input"))
    )
    (net (code "255") (name "Net-(LED220-PadDO)") (class "Default")
      (node (ref "LED220") (pin "DO") (pinfunction "DO_DO") (pintype "output"))
      (node (ref "LED221") (pin "DI") (pinfunction "DI_DI") (pintype "input"))
    )
    (net (code "256") (name "Net-(LED221-PadDO)") (class "Default")
      (node (ref "LED221") (pin "DO") (pinfunction "DO_DO") (pintype "output"))
      (node (ref "LED222") (pin "DI") (pinfunction "DI_DI") (pintype "input"))
    )
    (net (code "257") (name "Net-(LED222-PadDO)") (class "Default")
      (node (ref "LED222") (pin "DO") (pinfunction "DO_DO") (pintype "output"))
      (node (ref "LED223") (pin "DI") (pinfunction "DI_DI") (pintype "input"))
    )
    (net (code "258") (name "Net-(LED223-PadDO)") (class "Default")
      (node (ref "LED223") (pin "DO") (pinfunction "DO_DO") (pintype "output"))
      (node (ref "LED224") (pin "DI") (pinfunction "DI_DI") (pintype "input"))
    )
    (net (code "259") (name "Net-(LED224-PadDO)") (class "Default")
      (node (ref "LED224") (pin "DO") (pinfunction "DO_DO") (pintype "output"))
      (node (ref "LED225") (pin "DI") (pinfunction "DI_DI") (pintype "input"))
    )
    (net (code "260") (name "Net-(LED225-PadDO)") (class "Default")
      (node (ref "LED225") (pin "DO") (pinfunction "DO_DO") (pintype "output"))
      (node (ref "LED226") (pin "DI") (pinfunction "DI_DI") (pintype "input"))
    )
    (net (code "261") (name "Net-(LED226-PadDO)") (class "Default")
      (node (ref "LED226") (pin "DO") (pinfunction "DO_DO") (pintype "output"))
      (node (ref "LED227") (pin "DI") (pinfunction "DI_DI") (pintype "input"))
    )
    (net (code "262") (name "Net-(LED227-PadDO)") (class "Default")
      (node (ref "LED227") (pin "DO") (pinfunction "DO_DO") (pintype "output"))
      (node (ref "LED228") (pin "DI") (pinfunction "DI_DI") (pintype "input"))
    )
    (net (code "263") (name "Net-(LED228-PadDO)") (class "Default")
      (node (ref "LED228") (pin "DO") (pinfunction "DO_DO") (pintype "output"))
      (node (ref "LED229") (pin "DI") (pinfunction "DI_DI") (pintype "input"))
    )
    (net (code "264") (name "Net-(LED229-PadDO)") (class "Default")
      (node (ref "LED229") (pin "DO") (pinfunction "DO_DO") (pintype "output"))
      (node (ref "LED230") (pin "DI") (pinfunction "DI_DI") (pintype "input"))
    )
    (net (code "265") (name "Net-(LED230-PadDO)") (class "Default")
      (node (ref "LED230") (pin "DO") (pinfunction "DO_DO") (pintype "output"))
      (node (ref "LED231") (pin "DI") (pinfunction "DI_DI") (pintype "input"))
    )
    (net (code "266") (name "Net-(LED231-PadDO)") (class "Default")
      (node (ref "LED231") (pin "DO") (pinfunction "DO_DO") (pintype "output"))
      (node (ref "LED232") (pin "DI") (pinfunction "DI_DI") (pintype "input"))
    )
    (net (code "267") (name "Net-(LED232-PadDO)") (class "Default")
      (node (ref "LED232") (pin "DO") (pinfunction "DO_DO") (pintype "output"))
      (node (ref "LED233") (pin "DI") (pinfunction "DI_DI") (pintype "input"))
    )
    (net (code "268") (name "Net-(LED233-PadDO)") (class "Default")
      (node (ref "LED233") (pin "DO") (pinfunction "DO_DO") (pintype "output"))
      (node (ref "LED234") (pin "DI") (pinfunction "DI_DI") (pintype "input"))
    )
    (net (code "269") (name "Net-(LED234-PadDO)") (class "Default")
      (node (ref "LED234") (pin "DO") (pinfunction "DO_DO") (pintype "output"))
      (node (ref "LED235") (pin "DI") (pinfunction "DI_DI") (pintype "input"))
    )
    (net (code "270") (name "Net-(LED235-PadDO)") (class "Default")
      (node (ref "LED235") (pin "DO") (pinfunction "DO_DO") (pintype "output"))
      (node (ref "LED236") (pin "DI") (pinfunction "DI_DI") (pintype "input"))
    )
    (net (code "271") (name "Net-(LED236-PadDO)") (class "Default")
      (node (ref "LED236") (pin "DO") (pinfunction "DO_DO") (pintype "output"))
      (node (ref "LED237") (pin "DI") (pinfunction "DI_DI") (pintype "input"))
    )
    (net (code "272") (name "Net-(LED237-PadDO)") (class "Default")
      (node (ref "LED237") (pin "DO") (pinfunction "DO_DO") (pintype "output"))
      (node (ref "LED238") (pin "DI") (pinfunction "DI_DI") (pintype "input"))
    )
    (net (code "273") (name "Net-(LED238-PadDO)") (class "Default")
      (node (ref "LED238") (pin "DO") (pinfunction "DO_DO") (pintype "output"))
      (node (ref "LED239") (pin "DI") (pinfunction "DI_DI") (pintype "input"))
    )
    (net (code "274") (name "Net-(LED239-PadDO)") (class "Default")
      (node (ref "LED239") (pin "DO") (pinfunction "DO_DO") (pintype "output"))
      (node (ref "LED240") (pin "DI") (pinfunction "DI_DI") (pintype "input"))
    )
    (net (code "275") (name "Net-(LED240-PadDO)") (class "Default")
      (node (ref "LED240") (pin "DO") (pinfunction "DO_DO") (pintype "output"))
      (node (ref "LED241") (pin "DI") (pinfunction "DI_DI") (pintype "input"))
    )
    (net (code "276") (name "Net-(LED241-PadDO)") (class "Default")
      (node (ref "LED241") (pin "DO") (pinfunction "DO_DO") (pintype "output"))
      (node (ref "LED242") (pin "DI") (pinfunction "DI_DI") (pintype "input"))
    )
    (net (code "277") (name "Net-(LED242-PadDO)") (class "Default")
      (node (ref "LED242") (pin "DO") (pinfunction "DO_DO") (pintype "output"))
      (node (ref "LED243") (pin "DI") (pinfunction "DI_DI") (pintype "input"))
    )
    (net (code "278") (name "Net-(LED243-PadDO)") (class "Default")
      (node (ref "LED243") (pin "DO") (pinfunction "DO_DO") (pintype "output"))
      (node (ref "LED244") (pin "DI") (pinfunction "DI_DI") (pintype "input"))
    )
    (net (code "279") (name "Net-(LED244-PadDO)") (class "Default")
      (node (ref "LED244") (pin "DO") (pinfunction "DO_DO") (pintype "output"))
      (node (ref "LED245") (pin "DI") (pinfunction "DI_DI") (pintype "input"))
    )
    (net (code "280") (name "Net-(LED245-PadDO)") (class "Default")
      (node (ref "LED245") (pin "DO") (pinfunction "DO_DO") (pintype "output"))
      (node (ref "LED246") (pin "DI") (pinfunction "DI_DI") (pintype "input"))
    )
    (net (code "281") (name "Net-(LED246-PadDO)") (class "Default")
      (node (ref "LED246") (pin "DO") (pinfunction "DO_DO") (pintype "output"))
      (node (ref "LED247") (pin "DI") (pinfunction "DI_DI") (pintype "input"))
    )
    (net (code "282") (name "Net-(LED247-PadDO)") (class "Default")
      (node (ref "LED247") (pin "DO") (pinfunction "DO_DO") (pintype "output"))
      (node (ref "LED248") (pin "DI") (pinfunction "DI_DI") (pintype "input"))
    )
    (net (code "283") (name "Net-(LED248-PadDO)") (class "Default")
      (node (ref "LED248") (pin "DO") (pinfunction "DO_DO") (pintype "output"))
      (node (ref "LED249") (pin "DI") (pinfunction "DI_DI") (pintype "input"))
    )
    (net (code "284") (name "Net-(LED249-PadDO)") (class "Default")
      (node (ref "LED249") (pin "DO") (pinfunction "DO_DO") (pintype "output"))
      (node (ref "LED250") (pin "DI") (pinfunction "DI_DI") (pintype "input"))
    )
    (net (code "285") (name "Net-(LED250-PadDO)") (class "Default")
      (node (ref "LED250") (pin "DO") (pinfunction "DO_DO") (pintype "output"))
      (node (ref "LED251") (pin "DI") (pinfunction "DI_DI") (pintype "input"))
    )
    (net (code "286") (name "Net-(LED251-PadDO)") (class "Default")
      (node (ref "LED251") (pin "DO") (pinfunction "DO_DO") (pintype "output"))
      (node (ref "LED252") (pin "DI") (pinfunction "DI_DI") (pintype "input"))
    )
    (net (code "287") (name "Net-(LED252-PadDO)") (class "Default")
      (node (ref "LED252") (pin "DO") (pinfunction "DO_DO") (pintype "output"))
      (node (ref "LED253") (pin "DI") (pinfunction "DI_DI") (pintype "input"))
    )
    (net (code "288") (name "Net-(LED253-PadDO)") (class "Default")
      (node (ref "LED253") (pin "DO") (pinfunction "DO_DO") (pintype "output"))
      (node (ref "LED254") (pin "DI") (pinfunction "DI_DI") (pintype "input"))
    )
    (net (code "289") (name "Net-(LED254-PadDO)") (class "Default")
      (node (ref "LED254") (pin "DO") (pinfunction "DO_DO") (pintype "output"))
      (node (ref "LED255") (pin "DI") (pinfunction "DI_DI") (pintype "input"))
    )
    (net (code "290") (name "Net-(LED255-PadDO)") (class "Default")
      (node (ref "LED255") (pin "DO") (pinfunction "DO_DO") (pintype "output"))
      (node (ref "LED256") (pin "DI") (pinfunction "DI_DI") (pintype "input"))
    )
    (net (code "291") (name "Net-(LED256-PadDO)") (class "Default")
      (node (ref "LED256") (pin "DO") (pinfunction "DO_DO") (pintype "output"))
      (node (ref "LED257") (pin "DI") (pinfunction "DI_DI") (pintype "input"))
    )
    (net (code "292") (name "Net-(LED257-PadDO)") (class "Default")
      (node (ref "LED257") (pin "DO") (pinfunction "DO_DO") (pintype "output"))
      (node (ref "LED258") (pin "DI") (pinfunction "DI_DI") (pintype "input"))
    )
    (net (code "293") (name "Net-(LED258-PadDO)") (class "Default")
      (node (ref "LED258") (pin "DO") (pinfunction "DO_DO") (pintype "output"))
      (node (ref "LED259") (pin "DI") (pinfunction "DI_DI") (pintype "input"))
    )
    (net (code "294") (name "Net-(LED259-PadDO)") (class "Default")
      (node (ref "LED259") (pin "DO") (pinfunction "DO_DO") (pintype "output"))
      (node (ref "LED260") (pin "DI") (pinfunction "DI_DI") (pintype "input"))
    )
    (net (code "295") (name "Net-(LED260-PadDO)") (class "Default")
      (node (ref "LED260") (pin "DO") (pinfunction "DO_DO") (pintype "output"))
      (node (ref "LED261") (pin "DI") (pinfunction "DI_DI") (pintype "input"))
    )
    (net (code "296") (name "Net-(LED261-PadDO)") (class "Default")
      (node (ref "LED261") (pin "DO") (pinfunction "DO_DO") (pintype "output"))
      (node (ref "LED262") (pin "DI") (pinfunction "DI_DI") (pintype "input"))
    )
    (net (code "297") (name "Net-(LED262-PadDO)") (class "Default")
      (node (ref "LED262") (pin "DO") (pinfunction "DO_DO") (pintype "output"))
      (node (ref "LED263") (pin "DI") (pinfunction "DI_DI") (pintype "input"))
    )
    (net (code "298") (name "Net-(LED263-PadDO)") (class "Default")
      (node (ref "LED263") (pin "DO") (pinfunction "DO_DO") (pintype "output"))
      (node (ref "LED264") (pin "DI") (pinfunction "DI_DI") (pintype "input"))
    )
    (net (code "299") (name "Net-(LED264-PadDO)") (class "Default")
      (node (ref "LED264") (pin "DO") (pinfunction "DO_DO") (pintype "output"))
      (node (ref "LED265") (pin "DI") (pinfunction "DI_DI") (pintype "input"))
    )
    (net (code "300") (name "Net-(LED265-PadDO)") (class "Default")
      (node (ref "LED265") (pin "DO") (pinfunction "DO_DO") (pintype "output"))
      (node (ref "LED266") (pin "DI") (pinfunction "DI_DI") (pintype "input"))
    )
    (net (code "301") (name "Net-(LED266-PadDO)") (class "Default")
      (node (ref "LED266") (pin "DO") (pinfunction "DO_DO") (pintype "output"))
      (node (ref "LED267") (pin "DI") (pinfunction "DI_DI") (pintype "input"))
    )
    (net (code "302") (name "Net-(LED267-PadDO)") (class "Default")
      (node (ref "LED267") (pin "DO") (pinfunction "DO_DO") (pintype "output"))
      (node (ref "LED268") (pin "DI") (pinfunction "DI_DI") (pintype "input"))
    )
    (net (code "303") (name "Net-(LED268-PadDO)") (class "Default")
      (node (ref "LED268") (pin "DO") (pinfunction "DO_DO") (pintype "output"))
      (node (ref "LED269") (pin "DI") (pinfunction "DI_DI") (pintype "input"))
    )
    (net (code "304") (name "Net-(LED269-PadDO)") (class "Default")
      (node (ref "LED269") (pin "DO") (pinfunction "DO_DO") (pintype "output"))
      (node (ref "LED270") (pin "DI") (pinfunction "DI_DI") (pintype "input"))
    )
    (net (code "305") (name "Net-(LED270-PadDO)") (class "Default")
      (node (ref "LED270") (pin "DO") (pinfunction "DO_DO") (pintype "output"))
      (node (ref "LED271") (pin "DI") (pinfunction "DI_DI") (pintype "input"))
    )
    (net (code "306") (name "Net-(LED271-PadDO)") (class "Default")
      (node (ref "LED271") (pin "DO") (pinfunction "DO_DO") (pintype "output"))
      (node (ref "LED272") (pin "DI") (pinfunction "DI_DI") (pintype "input"))
    )
    (net (code "307") (name "Net-(LED272-PadDO)") (class "Default")
      (node (ref "LED272") (pin "DO") (pinfunction "DO_DO") (pintype "output"))
      (node (ref "LED273") (pin "DI") (pinfunction "DI_DI") (pintype "input"))
    )
    (net (code "308") (name "Net-(LED273-PadDO)") (class "Default")
      (node (ref "LED273") (pin "DO") (pinfunction "DO_DO") (pintype "output"))
      (node (ref "LED274") (pin "DI") (pinfunction "DI_DI") (pintype "input"))
    )
    (net (code "309") (name "Net-(LED274-PadDO)") (class "Default")
      (node (ref "LED274") (pin "DO") (pinfunction "DO_DO") (pintype "output"))
      (node (ref "LED275") (pin "DI") (pinfunction "DI_DI") (pintype "input"))
    )
    (net (code "310") (name "Net-(LED275-PadDO)") (class "Default")
      (node (ref "LED275") (pin "DO") (pinfunction "DO_DO") (pintype "output"))
      (node (ref "LED276") (pin "DI") (pinfunction "DI_DI") (pintype "input"))
    )
    (net (code "311") (name "Net-(LED276-PadDO)") (class "Default")
      (node (ref "LED276") (pin "DO") (pinfunction "DO_DO") (pintype "output"))
      (node (ref "LED277") (pin "DI") (pinfunction "DI_DI") (pintype "input"))
    )
    (net (code "312") (name "Net-(LED277-PadDO)") (class "Default")
      (node (ref "LED277") (pin "DO") (pinfunction "DO_DO") (pintype "output"))
      (node (ref "LED278") (pin "DI") (pinfunction "DI_DI") (pintype "input"))
    )
    (net (code "313") (name "Net-(LED278-PadDO)") (class "Default")
      (node (ref "LED278") (pin "DO") (pinfunction "DO_DO") (pintype "output"))
      (node (ref "LED279") (pin "DI") (pinfunction "DI_DI") (pintype "input"))
    )
    (net (code "314") (name "Net-(LED279-PadDO)") (class "Default")
      (node (ref "LED279") (pin "DO") (pinfunction "DO_DO") (pintype "output"))
      (node (ref "LED280") (pin "DI") (pinfunction "DI_DI") (pintype "input"))
    )
    (net (code "315") (name "Net-(LED280-PadDO)") (class "Default")
      (node (ref "LED280") (pin "DO") (pinfunction "DO_DO") (pintype "output"))
      (node (ref "LED281") (pin "DI") (pinfunction "DI_DI") (pintype "input"))
    )
    (net (code "316") (name "Net-(LED281-PadDO)") (class "Default")
      (node (ref "LED281") (pin "DO") (pinfunction "DO_DO") (pintype "output"))
      (node (ref "LED282") (pin "DI") (pinfunction "DI_DI") (pintype "input"))
    )
    (net (code "317") (name "Net-(LED282-PadDO)") (class "Default")
      (node (ref "LED282") (pin "DO") (pinfunction "DO_DO") (pintype "output"))
      (node (ref "LED283") (pin "DI") (pinfunction "DI_DI") (pintype "input"))
    )
    (net (code "318") (name "Net-(LED283-PadDO)") (class "Default")
      (node (ref "LED283") (pin "DO") (pinfunction "DO_DO") (pintype "output"))
      (node (ref "LED284") (pin "DI") (pinfunction "DI_DI") (pintype "input"))
    )
    (net (code "319") (name "Net-(LED284-PadDO)") (class "Default")
      (node (ref "LED284") (pin "DO") (pinfunction "DO_DO") (pintype "output"))
      (node (ref "LED285") (pin "DI") (pinfunction "DI_DI") (pintype "input"))
    )
    (net (code "320") (name "Net-(LED285-PadDO)") (class "Default")
      (node (ref "LED285") (pin "DO") (pinfunction "DO_DO") (pintype "output"))
      (node (ref "LED286") (pin "DI") (pinfunction "DI_DI") (pintype "input"))
    )
    (net (code "321") (name "Net-(LED286-PadDO)") (class "Default")
      (node (ref "LED286") (pin "DO") (pinfunction "DO_DO") (pintype "output"))
      (node (ref "LED287") (pin "DI") (pinfunction "DI_DI") (pintype "input"))
    )
    (net (code "322") (name "Net-(LED287-PadDO)") (class "Default")
      (node (ref "LED287") (pin "DO") (pinfunction "DO_DO") (pintype "output"))
      (node (ref "LED288") (pin "DI") (pinfunction "DI_DI") (pintype "input"))
    )
  )
)
